# ACB-R1_0-43-CH09.net
KiCad netlist of a schematic drawn in EAGLE
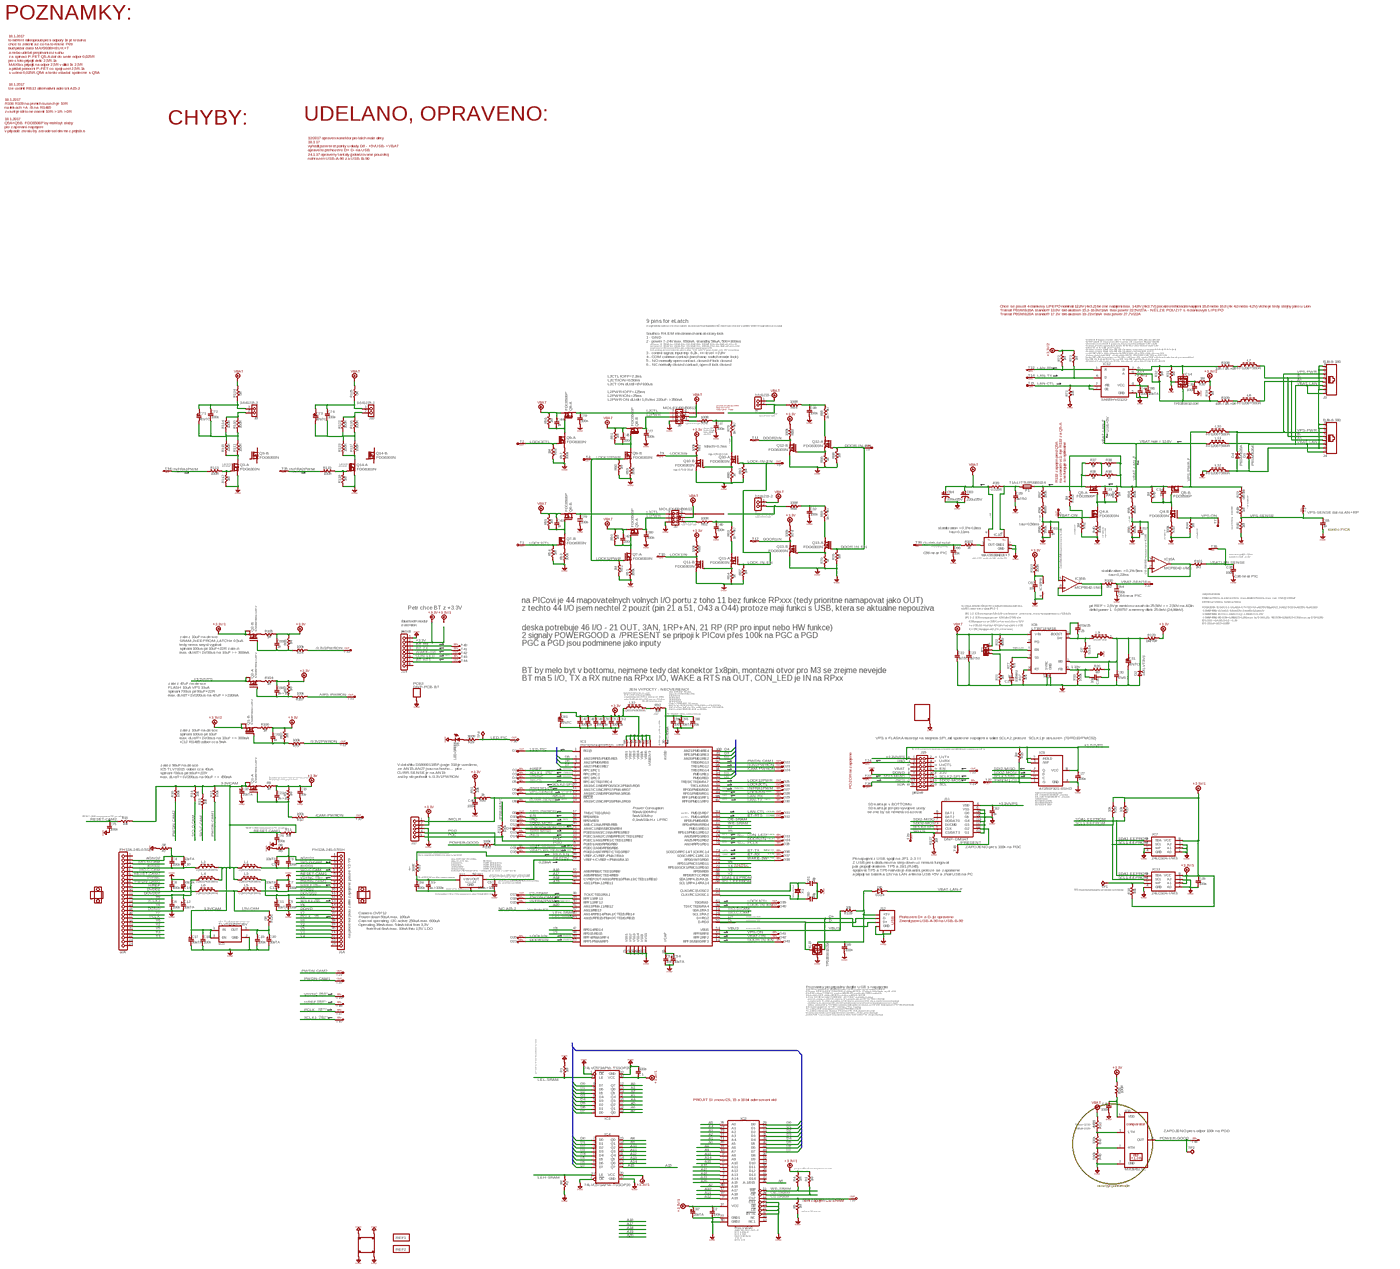
[diagram p0: schematic, sheet 1, overview]
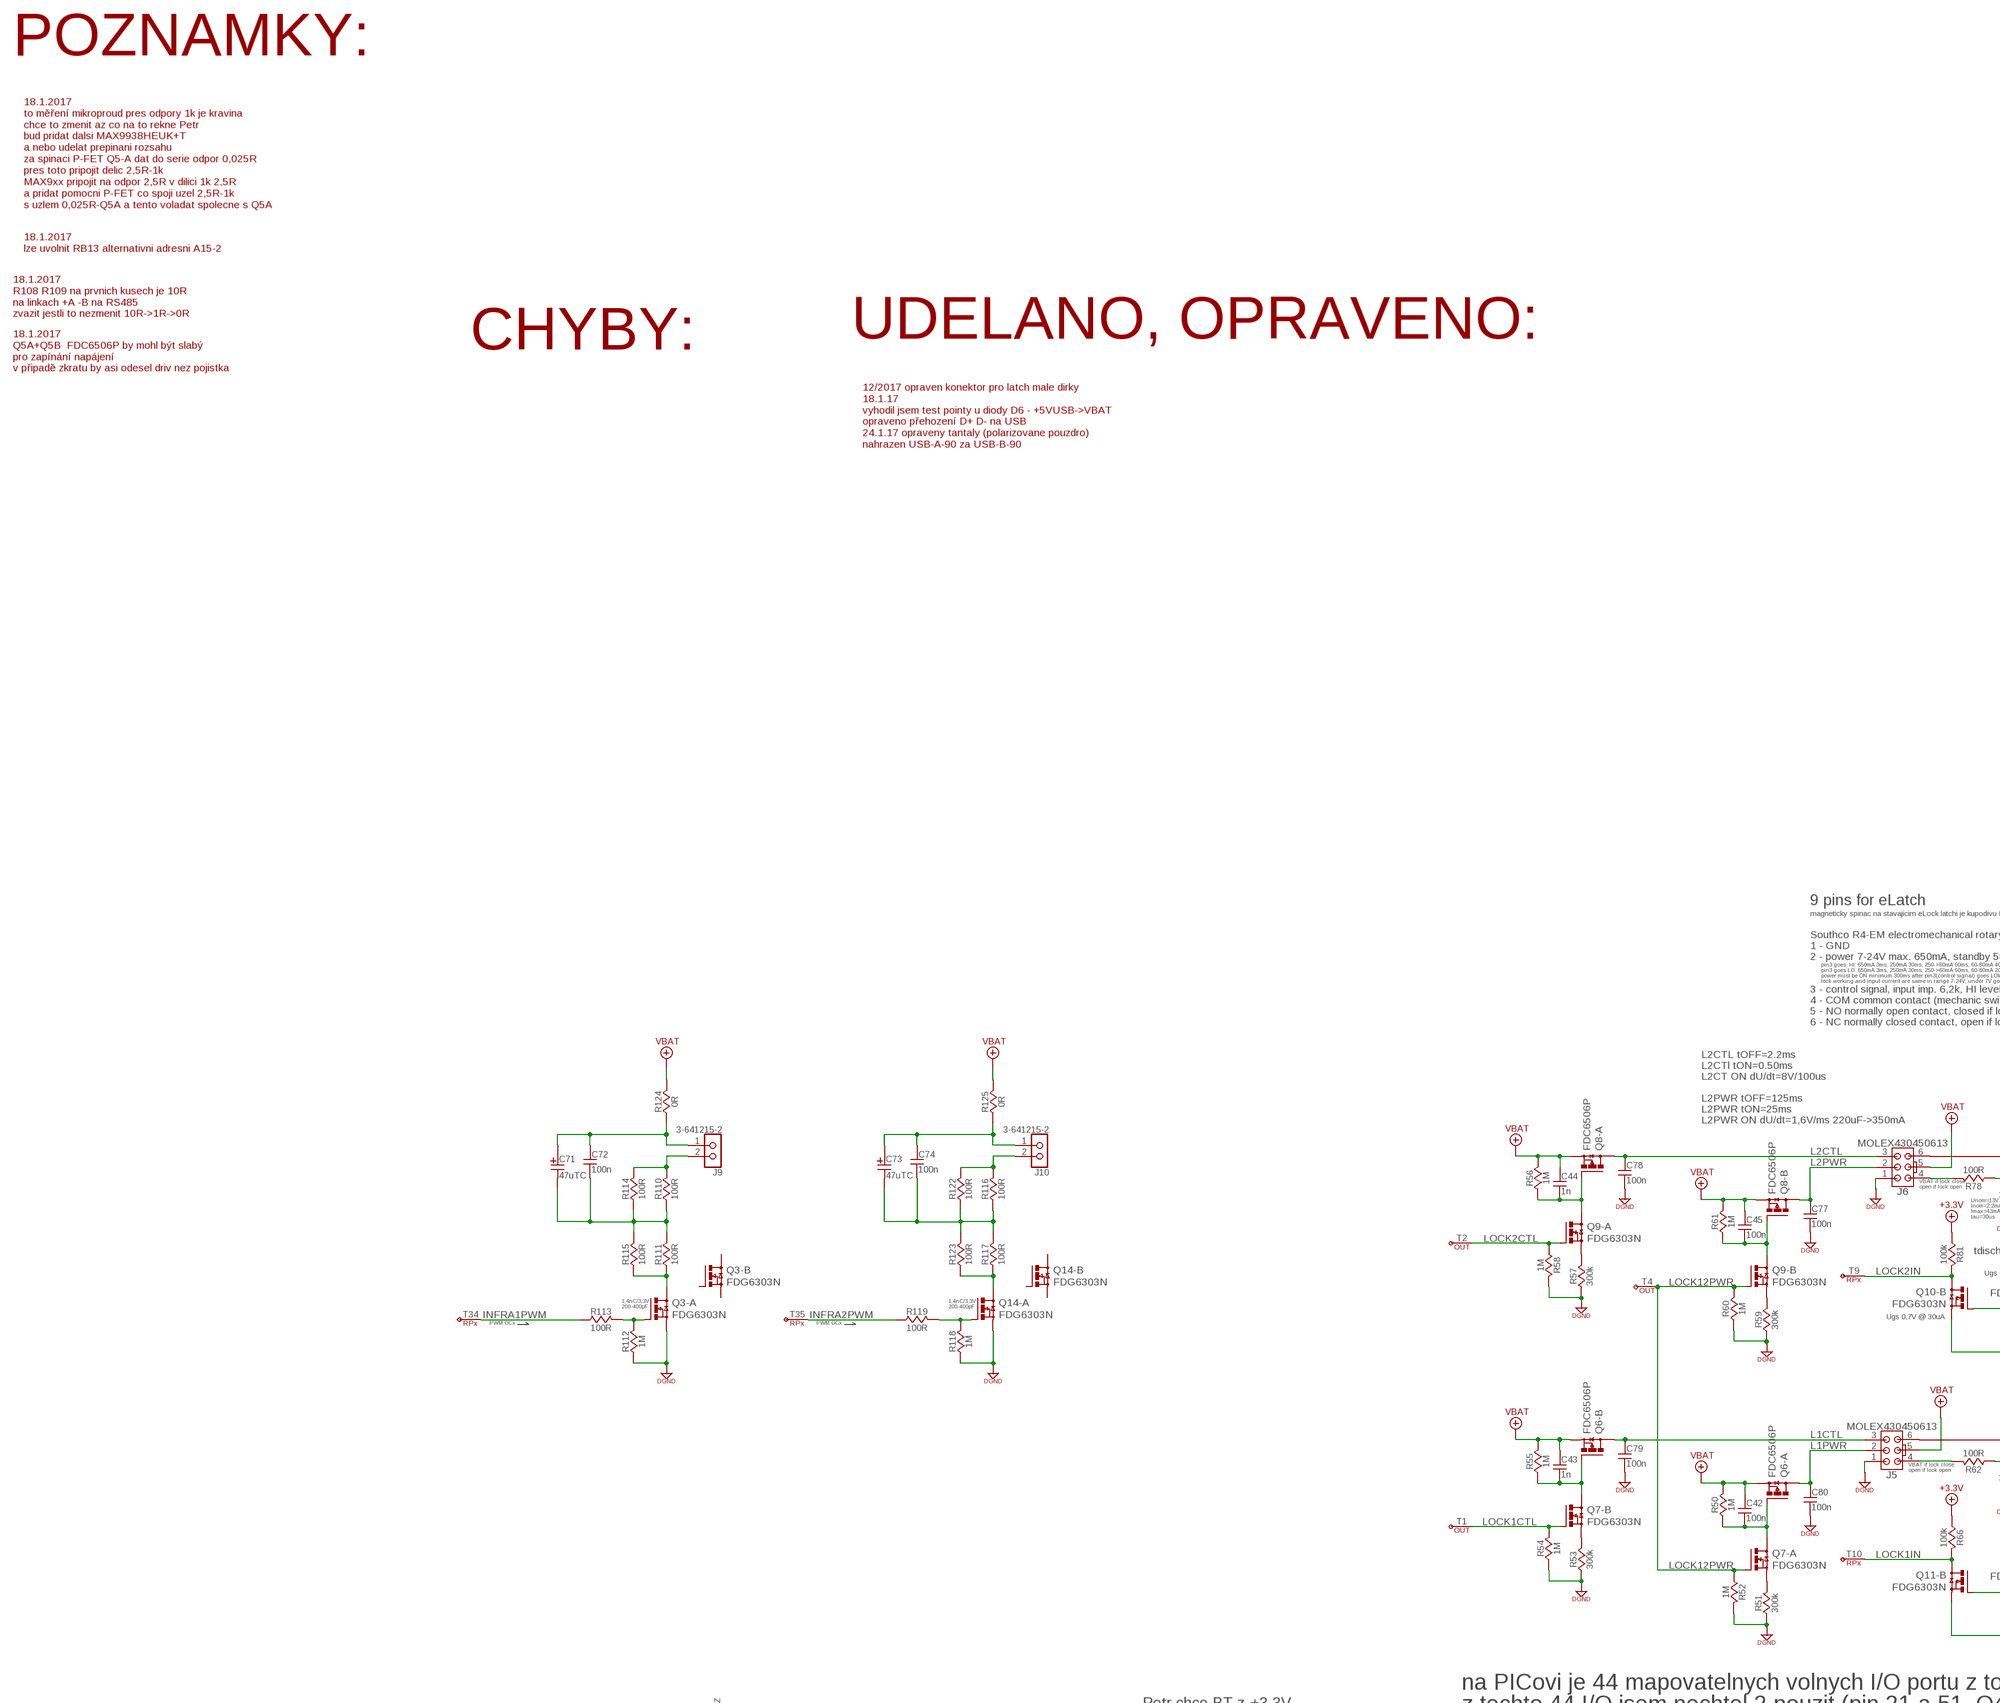
[diagram p1: schematic, sheet 1, part 1 of 4]
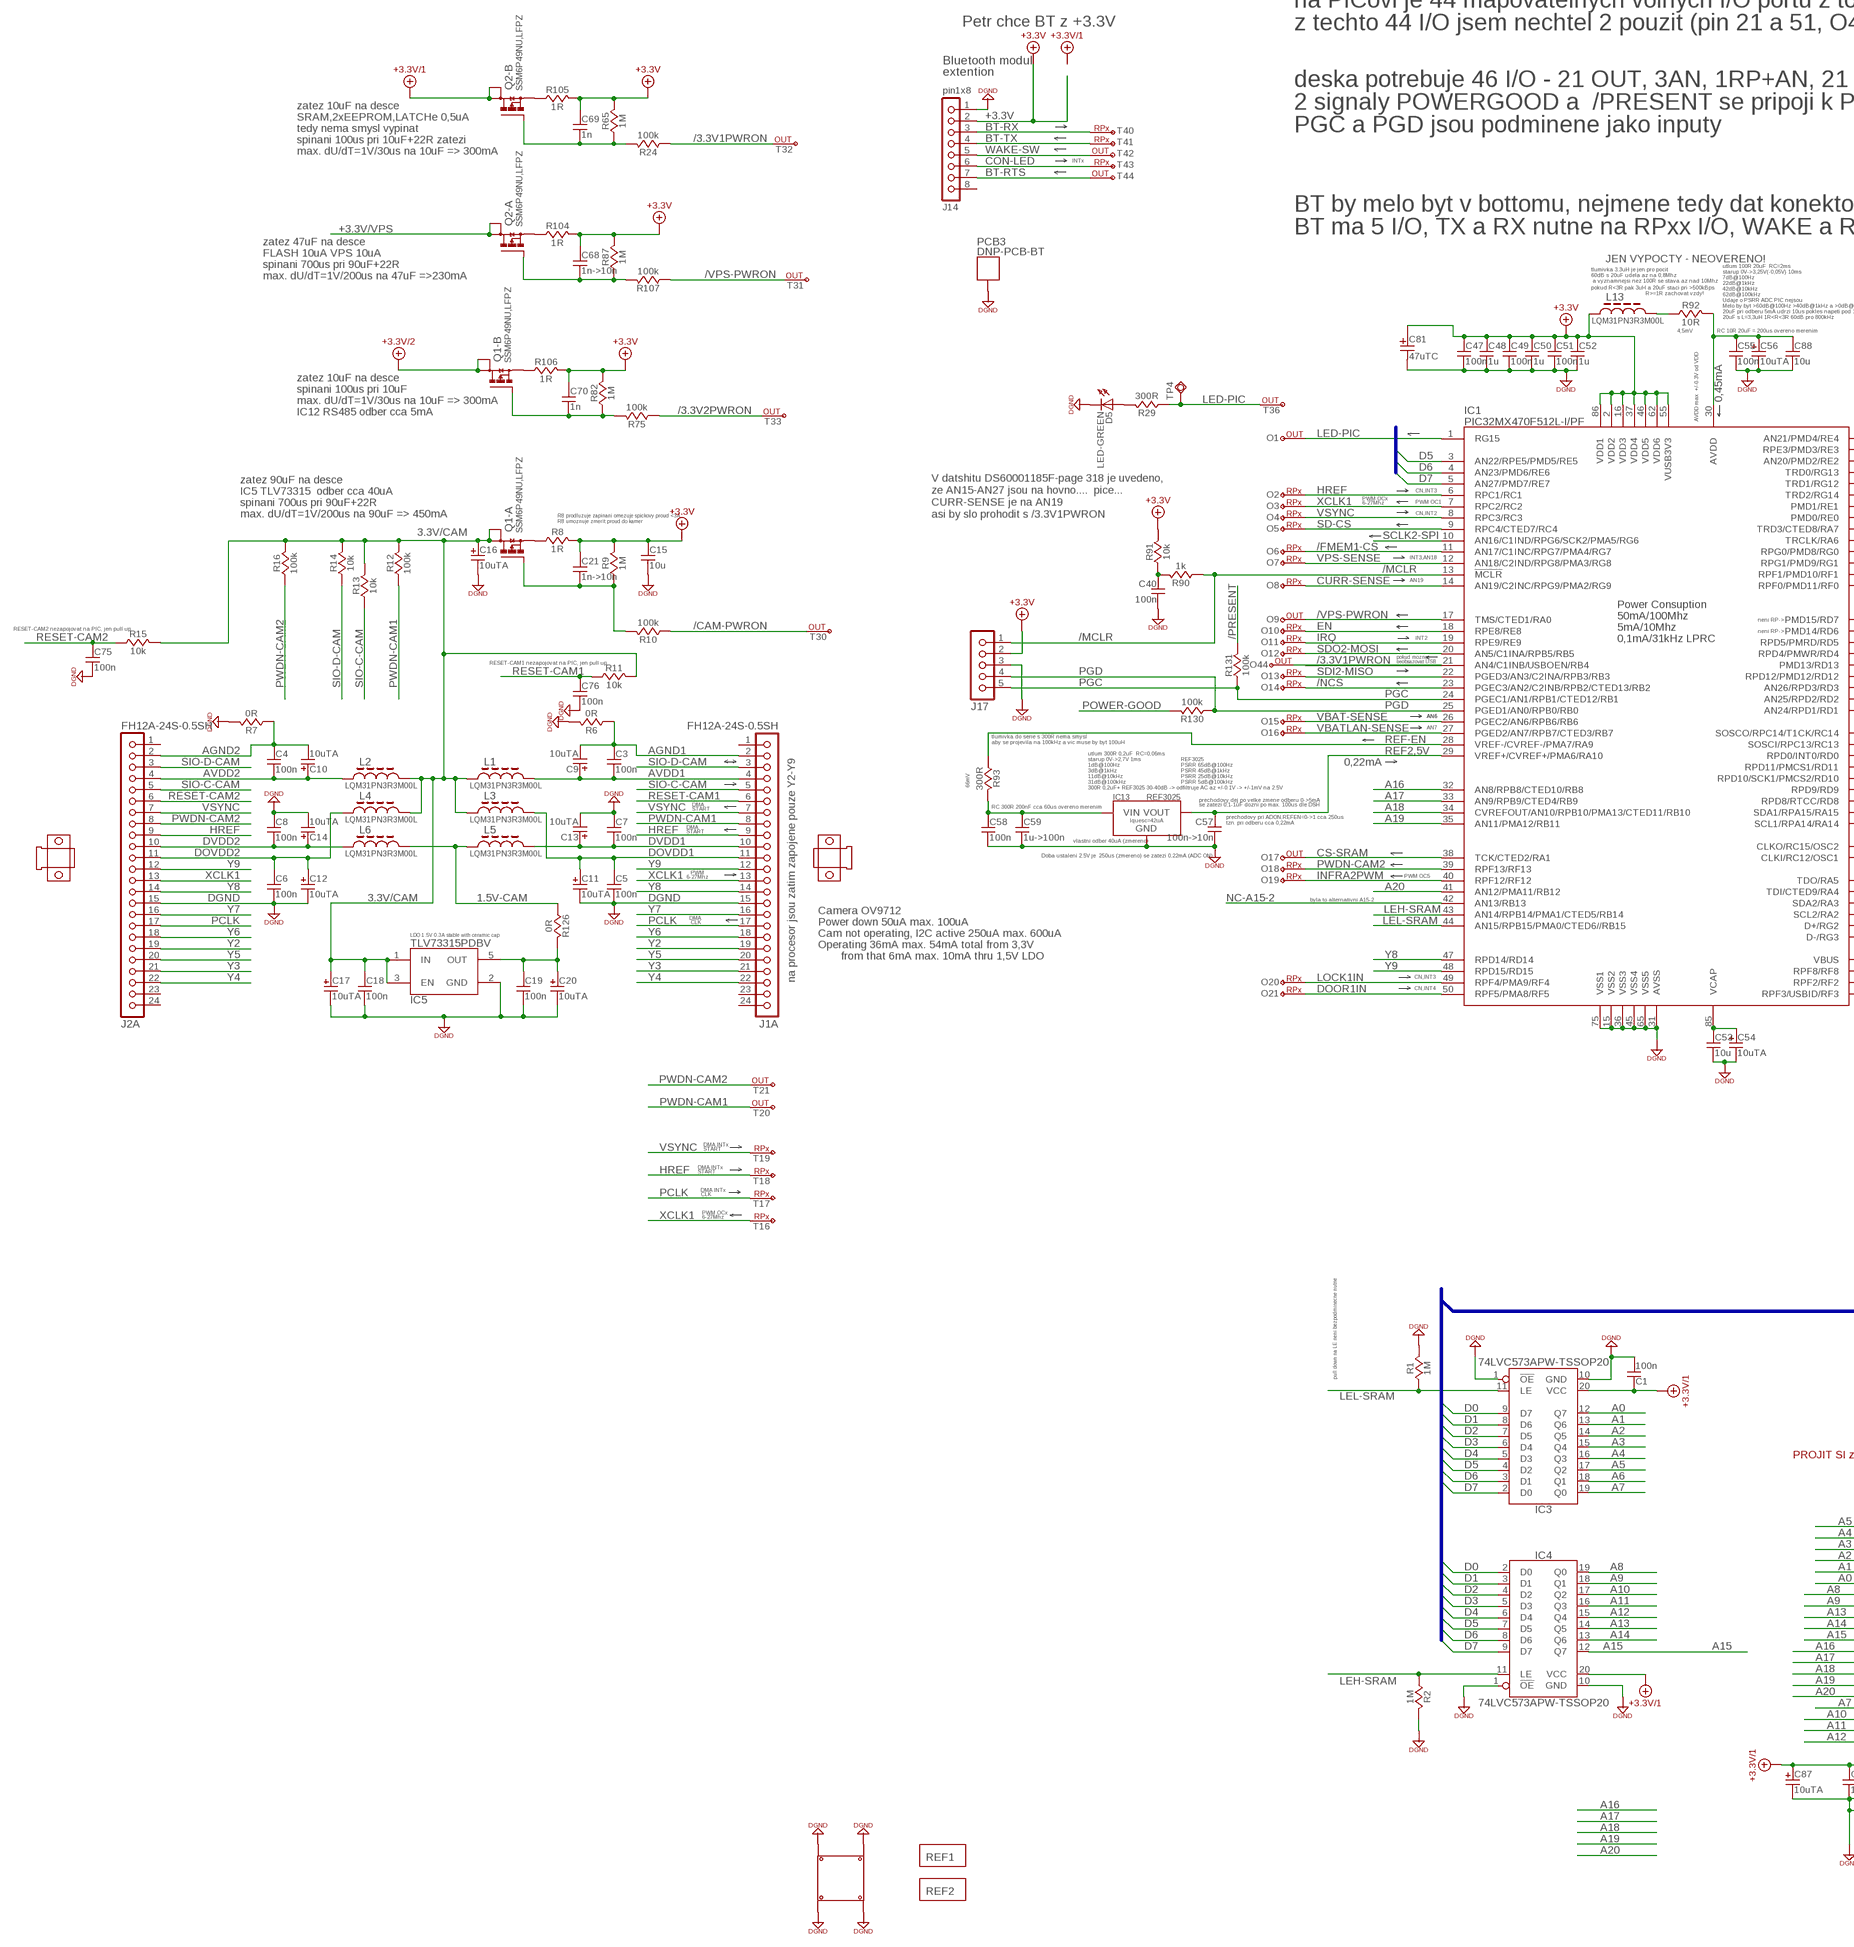
[diagram p2: schematic, sheet 1, part 2 of 4]
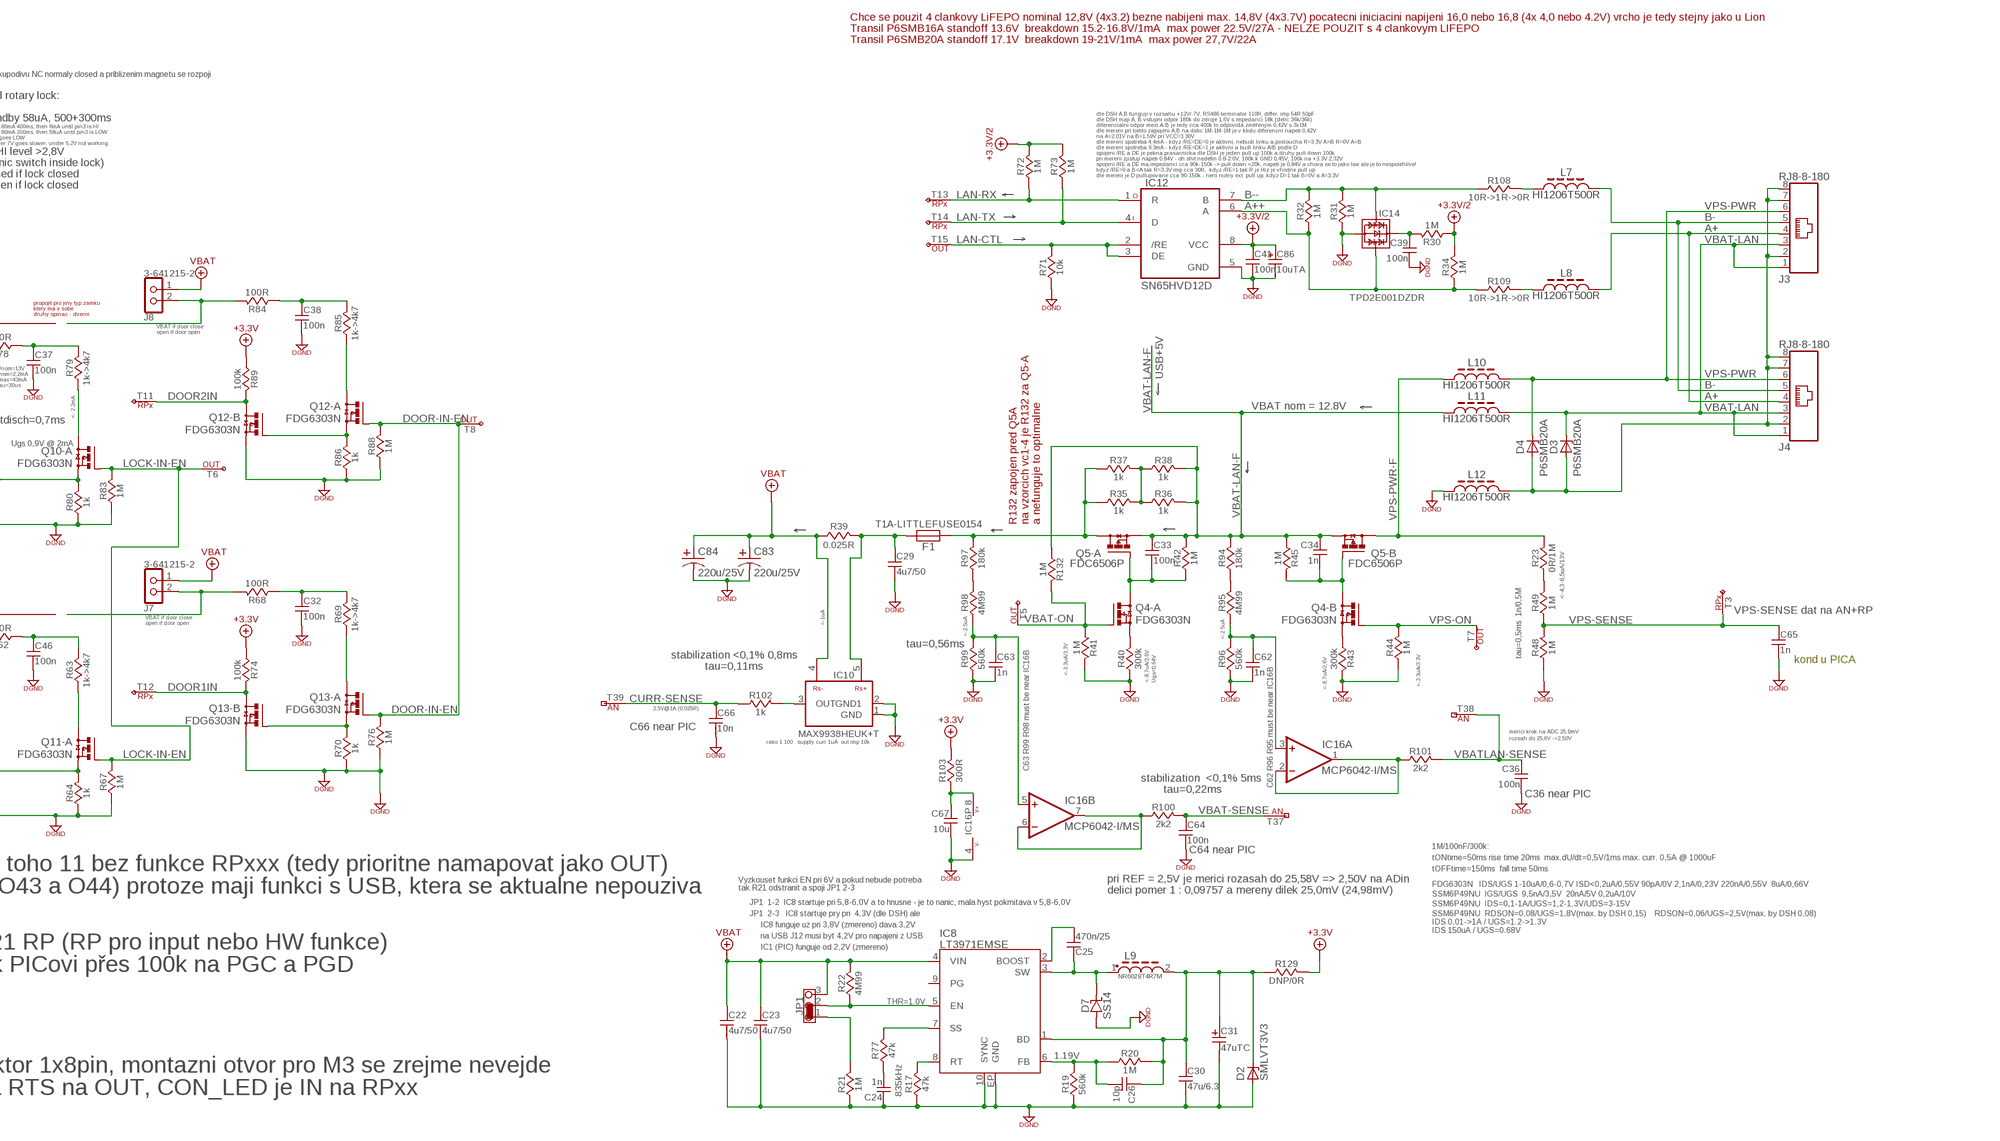
[diagram p3: schematic, sheet 1, part 3 of 4]
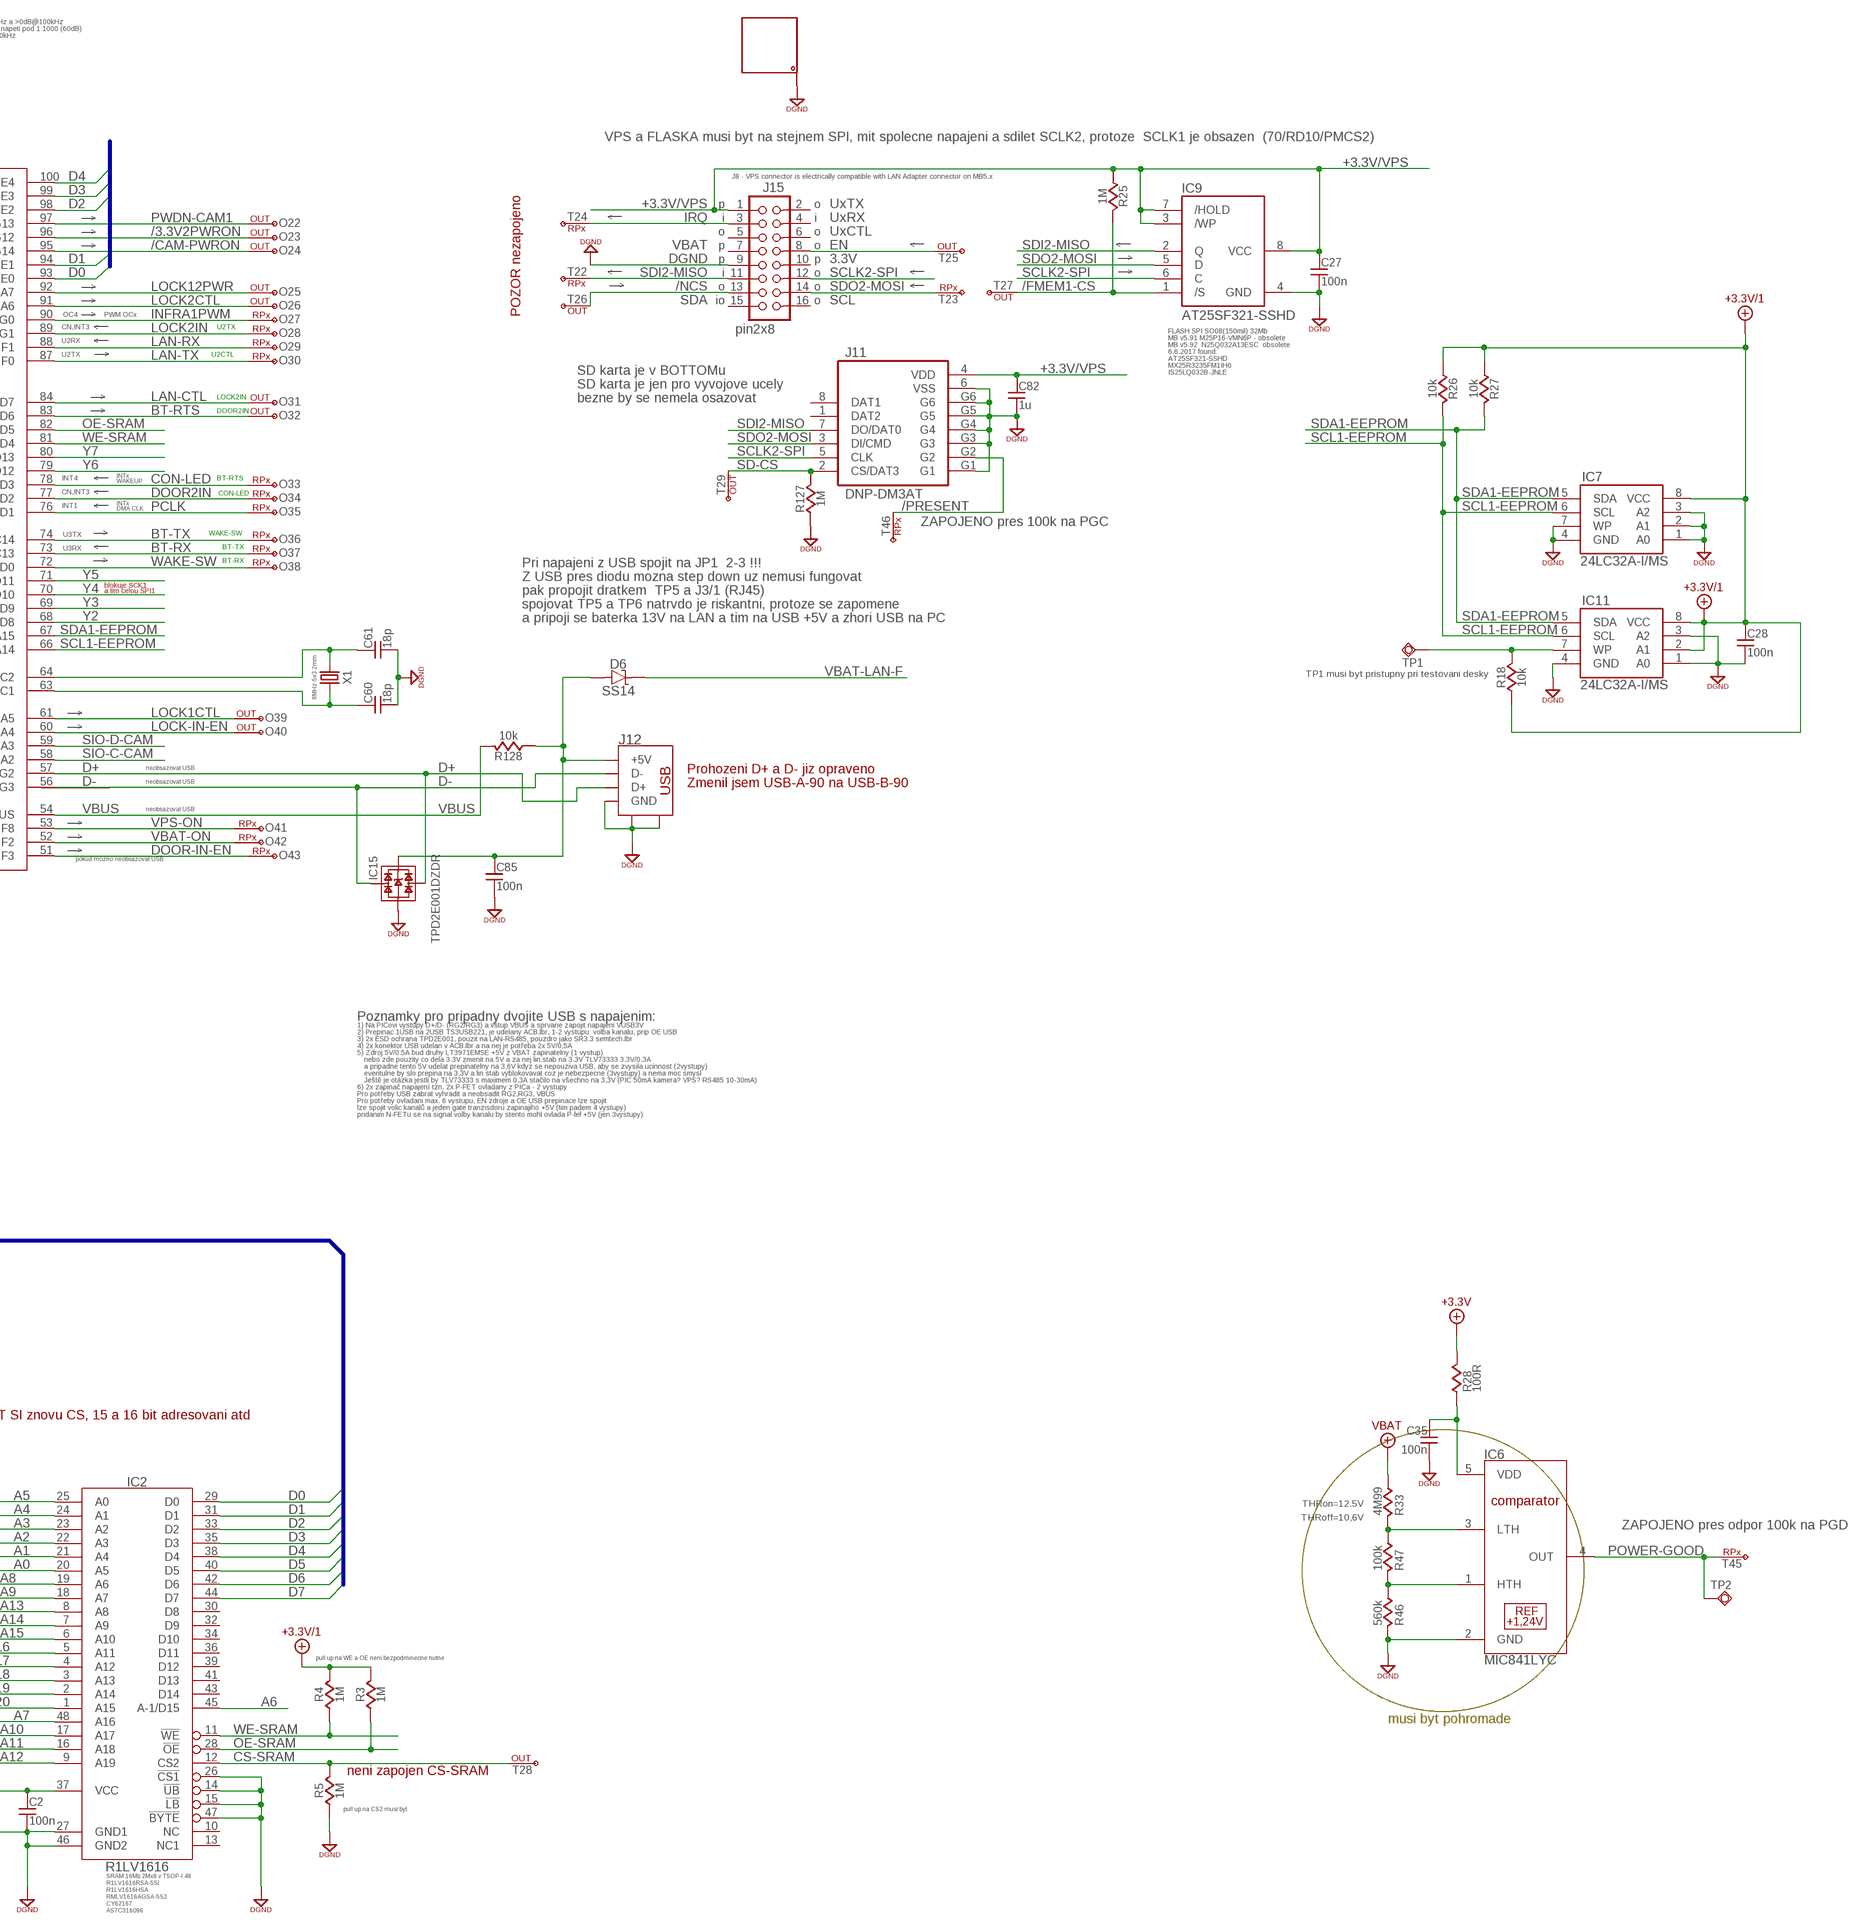
[diagram p4: schematic, sheet 1, part 4 of 4]

(export (version "E")
  (design (tool "Eeschema 10.0.6"))
  (components
    (comp (ref "C1")
      (value "100n")
      (footprint "eagle-import:0603")
      (libsource (lib "eagle-import") (part "C-0603"))
    )
    (comp (ref "C2")
      (value "100n")
      (footprint "eagle-import:0603")
      (libsource (lib "eagle-import") (part "C-0603"))
    )
    (comp (ref "C3")
      (value "100n")
      (footprint "eagle-import:0603")
      (libsource (lib "eagle-import") (part "C-0603"))
    )
    (comp (ref "C4")
      (value "100n")
      (footprint "eagle-import:0603")
      (libsource (lib "eagle-import") (part "C-0603"))
    )
    (comp (ref "C5")
      (value "100n")
      (footprint "eagle-import:0603")
      (libsource (lib "eagle-import") (part "C-0603"))
    )
    (comp (ref "C6")
      (value "100n")
      (footprint "eagle-import:0603")
      (libsource (lib "eagle-import") (part "C-0603"))
    )
    (comp (ref "C7")
      (value "100n")
      (footprint "eagle-import:0603")
      (libsource (lib "eagle-import") (part "C-0603"))
    )
    (comp (ref "C8")
      (value "100n")
      (footprint "eagle-import:0603")
      (libsource (lib "eagle-import") (part "C-0603"))
    )
    (comp (ref "C9")
      (value "10uTA")
      (footprint "eagle-import:1206-POL-C")
      (libsource (lib "eagle-import") (part "CT-1206"))
    )
    (comp (ref "C10")
      (value "10uTA")
      (footprint "eagle-import:1206-POL-C")
      (libsource (lib "eagle-import") (part "CT-1206"))
    )
    (comp (ref "C11")
      (value "10uTA")
      (footprint "eagle-import:1206-POL-C")
      (libsource (lib "eagle-import") (part "CT-1206"))
    )
    (comp (ref "C12")
      (value "10uTA")
      (footprint "eagle-import:1206-POL-C")
      (libsource (lib "eagle-import") (part "CT-1206"))
    )
    (comp (ref "C13")
      (value "10uTA")
      (footprint "eagle-import:1206-POL-C")
      (libsource (lib "eagle-import") (part "CT-1206"))
    )
    (comp (ref "C14")
      (value "10uTA")
      (footprint "eagle-import:1206-POL-C")
      (libsource (lib "eagle-import") (part "CT-1206"))
    )
    (comp (ref "C15")
      (value "10u")
      (footprint "eagle-import:0603")
      (libsource (lib "eagle-import") (part "C-0603"))
    )
    (comp (ref "C16")
      (value "10uTA")
      (footprint "eagle-import:1206-POL-C")
      (libsource (lib "eagle-import") (part "CT-1206"))
    )
    (comp (ref "C17")
      (value "10uTA")
      (footprint "eagle-import:1206-POL-C")
      (libsource (lib "eagle-import") (part "CT-1206"))
    )
    (comp (ref "C18")
      (value "100n")
      (footprint "eagle-import:0603")
      (libsource (lib "eagle-import") (part "C-0603"))
    )
    (comp (ref "C19")
      (value "100n")
      (footprint "eagle-import:0603")
      (libsource (lib "eagle-import") (part "C-0603"))
    )
    (comp (ref "C20")
      (value "10uTA")
      (footprint "eagle-import:1206-POL-C")
      (libsource (lib "eagle-import") (part "CT-1206"))
    )
    (comp (ref "C21")
      (value "1n->10n")
      (footprint "eagle-import:0603")
      (libsource (lib "eagle-import") (part "C-0603"))
    )
    (comp (ref "C22")
      (value "4u7/50")
      (footprint "eagle-import:1206")
      (libsource (lib "eagle-import") (part "C-1206"))
    )
    (comp (ref "C23")
      (value "4u7/50")
      (footprint "eagle-import:1206")
      (libsource (lib "eagle-import") (part "C-1206"))
    )
    (comp (ref "C24")
      (value "1n")
      (footprint "eagle-import:0603")
      (libsource (lib "eagle-import") (part "C-0603"))
    )
    (comp (ref "C25")
      (value "470n/25")
      (footprint "eagle-import:0603")
      (libsource (lib "eagle-import") (part "C-0603"))
    )
    (comp (ref "C26")
      (value "10p")
      (footprint "eagle-import:0603")
      (libsource (lib "eagle-import") (part "C-0603"))
    )
    (comp (ref "C27")
      (value "100n")
      (footprint "eagle-import:0603")
      (libsource (lib "eagle-import") (part "C-0603"))
    )
    (comp (ref "C28")
      (value "100n")
      (footprint "eagle-import:0603")
      (libsource (lib "eagle-import") (part "C-0603"))
    )
    (comp (ref "C29")
      (value "4u7/50")
      (footprint "eagle-import:1206")
      (libsource (lib "eagle-import") (part "C-1206"))
    )
    (comp (ref "C30")
      (value "47u/6.3")
      (footprint "eagle-import:1206")
      (libsource (lib "eagle-import") (part "C-1206"))
    )
    (comp (ref "C31")
      (value "47uTC")
      (footprint "eagle-import:CT-C")
      (libsource (lib "eagle-import") (part "CT-C"))
    )
    (comp (ref "C32")
      (value "100n")
      (footprint "eagle-import:0603")
      (libsource (lib "eagle-import") (part "C-0603"))
    )
    (comp (ref "C33")
      (value "100n")
      (footprint "eagle-import:0603")
      (libsource (lib "eagle-import") (part "C-0603"))
    )
    (comp (ref "C34")
      (value "1n")
      (footprint "eagle-import:0603")
      (libsource (lib "eagle-import") (part "C-0603"))
    )
    (comp (ref "C35")
      (value "100n")
      (footprint "eagle-import:0603")
      (libsource (lib "eagle-import") (part "C-0603"))
    )
    (comp (ref "C36")
      (value "100n")
      (footprint "eagle-import:0603")
      (libsource (lib "eagle-import") (part "C-0603"))
    )
    (comp (ref "C37")
      (value "100n")
      (footprint "eagle-import:0603")
      (libsource (lib "eagle-import") (part "C-0603"))
    )
    (comp (ref "C38")
      (value "100n")
      (footprint "eagle-import:0603")
      (libsource (lib "eagle-import") (part "C-0603"))
    )
    (comp (ref "C39")
      (value "100n")
      (footprint "eagle-import:0603")
      (libsource (lib "eagle-import") (part "C-0603"))
    )
    (comp (ref "C40")
      (value "100n")
      (footprint "eagle-import:0603")
      (libsource (lib "eagle-import") (part "C-0603"))
    )
    (comp (ref "C41")
      (value "100n")
      (footprint "eagle-import:0603")
      (libsource (lib "eagle-import") (part "C-0603"))
    )
    (comp (ref "C42")
      (value "100n")
      (footprint "eagle-import:0603")
      (libsource (lib "eagle-import") (part "C-0603"))
    )
    (comp (ref "C43")
      (value "1n")
      (footprint "eagle-import:0603")
      (libsource (lib "eagle-import") (part "C-0603"))
    )
    (comp (ref "C44")
      (value "1n")
      (footprint "eagle-import:0603")
      (libsource (lib "eagle-import") (part "C-0603"))
    )
    (comp (ref "C45")
      (value "100n")
      (footprint "eagle-import:0603")
      (libsource (lib "eagle-import") (part "C-0603"))
    )
    (comp (ref "C46")
      (value "100n")
      (footprint "eagle-import:0603")
      (libsource (lib "eagle-import") (part "C-0603"))
    )
    (comp (ref "C47")
      (value "100n")
      (footprint "eagle-import:0603")
      (libsource (lib "eagle-import") (part "C-0603"))
    )
    (comp (ref "C48")
      (value "1u")
      (footprint "eagle-import:0603")
      (libsource (lib "eagle-import") (part "C-0603"))
    )
    (comp (ref "C49")
      (value "100n")
      (footprint "eagle-import:0603")
      (libsource (lib "eagle-import") (part "C-0603"))
    )
    (comp (ref "C50")
      (value "1u")
      (footprint "eagle-import:0603")
      (libsource (lib "eagle-import") (part "C-0603"))
    )
    (comp (ref "C51")
      (value "100n")
      (footprint "eagle-import:0603")
      (libsource (lib "eagle-import") (part "C-0603"))
    )
    (comp (ref "C52")
      (value "1u")
      (footprint "eagle-import:0603")
      (libsource (lib "eagle-import") (part "C-0603"))
    )
    (comp (ref "C53")
      (value "10u")
      (footprint "eagle-import:0603")
      (libsource (lib "eagle-import") (part "C-0603"))
    )
    (comp (ref "C54")
      (value "10uTA")
      (footprint "eagle-import:1206-POL-C")
      (libsource (lib "eagle-import") (part "CT-1206"))
    )
    (comp (ref "C55")
      (value "100n")
      (footprint "eagle-import:0603")
      (libsource (lib "eagle-import") (part "C-0603"))
    )
    (comp (ref "C56")
      (value "10uTA")
      (footprint "eagle-import:1206-POL-C")
      (libsource (lib "eagle-import") (part "CT-1206"))
    )
    (comp (ref "C57")
      (value "100n->10n")
      (footprint "eagle-import:0603")
      (libsource (lib "eagle-import") (part "C-0603"))
    )
    (comp (ref "C58")
      (value "100n")
      (footprint "eagle-import:0603")
      (libsource (lib "eagle-import") (part "C-0603"))
    )
    (comp (ref "C59")
      (value "1u->100n")
      (footprint "eagle-import:0603")
      (libsource (lib "eagle-import") (part "C-0603"))
    )
    (comp (ref "C60")
      (value "18p")
      (footprint "eagle-import:0603")
      (libsource (lib "eagle-import") (part "C-0603"))
    )
    (comp (ref "C61")
      (value "18p")
      (footprint "eagle-import:0603")
      (libsource (lib "eagle-import") (part "C-0603"))
    )
    (comp (ref "C62")
      (value "1n")
      (footprint "eagle-import:0603")
      (libsource (lib "eagle-import") (part "C-0603"))
    )
    (comp (ref "C63")
      (value "1n")
      (footprint "eagle-import:0603")
      (libsource (lib "eagle-import") (part "C-0603"))
    )
    (comp (ref "C64")
      (value "100n")
      (footprint "eagle-import:0603")
      (libsource (lib "eagle-import") (part "C-0603"))
    )
    (comp (ref "C65")
      (value "1n")
      (footprint "eagle-import:0603")
      (libsource (lib "eagle-import") (part "C-0603"))
    )
    (comp (ref "C66")
      (value "10n")
      (footprint "eagle-import:0603")
      (libsource (lib "eagle-import") (part "C-0603"))
    )
    (comp (ref "C67")
      (value "10u")
      (footprint "eagle-import:0603")
      (libsource (lib "eagle-import") (part "C-0603"))
    )
    (comp (ref "C68")
      (value "1n->10n")
      (footprint "eagle-import:0603")
      (libsource (lib "eagle-import") (part "C-0603"))
    )
    (comp (ref "C69")
      (value "1n")
      (footprint "eagle-import:0603")
      (libsource (lib "eagle-import") (part "C-0603"))
    )
    (comp (ref "C70")
      (value "1n")
      (footprint "eagle-import:0603")
      (libsource (lib "eagle-import") (part "C-0603"))
    )
    (comp (ref "C71")
      (value "47uTC")
      (footprint "eagle-import:CT-C")
      (libsource (lib "eagle-import") (part "CT-C"))
    )
    (comp (ref "C72")
      (value "100n")
      (footprint "eagle-import:0603")
      (libsource (lib "eagle-import") (part "C-0603"))
    )
    (comp (ref "C73")
      (value "47uTC")
      (footprint "eagle-import:CT-C")
      (libsource (lib "eagle-import") (part "CT-C"))
    )
    (comp (ref "C74")
      (value "100n")
      (footprint "eagle-import:0603")
      (libsource (lib "eagle-import") (part "C-0603"))
    )
    (comp (ref "C75")
      (value "100n")
      (footprint "eagle-import:0603")
      (libsource (lib "eagle-import") (part "C-0603"))
    )
    (comp (ref "C76")
      (value "100n")
      (footprint "eagle-import:0603")
      (libsource (lib "eagle-import") (part "C-0603"))
    )
    (comp (ref "C77")
      (value "100n")
      (footprint "eagle-import:0603")
      (libsource (lib "eagle-import") (part "C-0603"))
    )
    (comp (ref "C78")
      (value "100n")
      (footprint "eagle-import:0603")
      (libsource (lib "eagle-import") (part "C-0603"))
    )
    (comp (ref "C79")
      (value "100n")
      (footprint "eagle-import:0603")
      (libsource (lib "eagle-import") (part "C-0603"))
    )
    (comp (ref "C80")
      (value "100n")
      (footprint "eagle-import:0603")
      (libsource (lib "eagle-import") (part "C-0603"))
    )
    (comp (ref "C81")
      (value "47uTC")
      (footprint "eagle-import:CT-C")
      (libsource (lib "eagle-import") (part "CT-C"))
    )
    (comp (ref "C82")
      (value "1u")
      (footprint "eagle-import:0603")
      (libsource (lib "eagle-import") (part "C-0603"))
    )
    (comp (ref "C83")
      (value "220u/25V")
      (footprint "eagle-import:CAP_8MM_DIA_SMT")
      (libsource (lib "eagle-import") (part "CAP-ELEC-SMD-8MM"))
    )
    (comp (ref "C84")
      (value "220u/25V")
      (footprint "eagle-import:CAP_8MM_DIA_SMT")
      (libsource (lib "eagle-import") (part "CAP-ELEC-SMD-8MM"))
    )
    (comp (ref "C85")
      (value "100n")
      (footprint "eagle-import:0603")
      (libsource (lib "eagle-import") (part "C-0603"))
    )
    (comp (ref "C86")
      (value "10uTA")
      (footprint "eagle-import:1206-POL-C")
      (libsource (lib "eagle-import") (part "CT-1206"))
    )
    (comp (ref "C87")
      (value "10uTA")
      (footprint "eagle-import:1206-POL-C")
      (libsource (lib "eagle-import") (part "CT-1206"))
    )
    (comp (ref "C88")
      (value "10u")
      (footprint "eagle-import:0603")
      (libsource (lib "eagle-import") (part "C-0603"))
    )
    (comp (ref "D2")
      (value "SMLVT3V3")
      (footprint "eagle-import:SMA")
      (libsource (lib "eagle-import") (part "SMLVT3V3"))
    )
    (comp (ref "D3")
      (value "P6SMB20A")
      (footprint "eagle-import:SMB")
      (libsource (lib "eagle-import") (part "P6SMB"))
    )
    (comp (ref "D4")
      (value "P6SMB20A")
      (footprint "eagle-import:SMB")
      (libsource (lib "eagle-import") (part "P6SMB"))
    )
    (comp (ref "D5")
      (value "LED-GREEN")
      (footprint "eagle-import:0805-POL-D")
      (libsource (lib "eagle-import") (part "LED-0805"))
    )
    (comp (ref "D6")
      (value "SS14")
      (footprint "eagle-import:SMA")
      (libsource (lib "eagle-import") (part "DS-SMA"))
    )
    (comp (ref "D7")
      (value "SS14")
      (footprint "eagle-import:SMA")
      (libsource (lib "eagle-import") (part "DS-SMA"))
    )
    (comp (ref "F1")
      (value "T1A-LITTLEFUSE0154")
      (footprint "eagle-import:LITTLEFUSE0154")
      (libsource (lib "eagle-import") (part "POJISTKA-LITTLEFUSE0154"))
    )
    (comp (ref "H1")
      (value "CAM-HOLDER")
      (footprint "eagle-import:CAM-HOLDER")
      (libsource (lib "eagle-import") (part "CAM-HOLDER"))
    )
    (comp (ref "H2")
      (value "CAM-HOLDER")
      (footprint "eagle-import:CAM-HOLDER")
      (libsource (lib "eagle-import") (part "CAM-HOLDER"))
    )
    (comp (ref "IC1")
      (value "PIC32MX470F512L-I/PF")
      (footprint "eagle-import:TQFP100_14X14_0,5MM")
      (libsource (lib "eagle-import") (part "PIC32MX470F512L-I/PF"))
    )
    (comp (ref "IC2")
      (value "R1LV1616")
      (footprint "eagle-import:48-TSOP-I")
      (libsource (lib "eagle-import") (part "R1LV1616HSA"))
    )
    (comp (ref "IC3")
      (value "74LVC573APW-TSSOP20")
      (footprint "eagle-import:TSSOP20")
      (libsource (lib "eagle-import") (part "74LVC573APW-TSSOP20"))
    )
    (comp (ref "IC4")
      (value "74LVC573APW-TSSOP20")
      (footprint "eagle-import:TSSOP20")
      (libsource (lib "eagle-import") (part "74LVC573APW-TSSOP20"))
    )
    (comp (ref "IC5")
      (value "TLV73315PDBV")
      (footprint "eagle-import:SOT23-5")
      (libsource (lib "eagle-import") (part "TLV73315PDBV"))
    )
    (comp (ref "IC6")
      (value "MIC841LYC")
      (footprint "eagle-import:SC-70-5")
      (libsource (lib "eagle-import") (part "MIC841LYC"))
    )
    (comp (ref "IC7")
      (value "24LC32A-I/MS")
      (footprint "eagle-import:MSOP-08")
      (libsource (lib "eagle-import") (part "24-I/MS"))
    )
    (comp (ref "IC8")
      (value "LT3971EMSE")
      (footprint "eagle-import:MSOP10EXP")
      (libsource (lib "eagle-import") (part "LT3971EMSE"))
    )
    (comp (ref "IC9")
      (value "AT25SF321-SSHD")
      (footprint "eagle-import:SO-08")
      (libsource (lib "eagle-import") (part "M25P16-VMN6P"))
    )
    (comp (ref "IC10")
      (value "MAX9938HEUK+T")
      (footprint "eagle-import:SOT23-5")
      (libsource (lib "eagle-import") (part "TSM9938HEUK+T"))
    )
    (comp (ref "IC11")
      (value "24LC32A-I/MS")
      (footprint "eagle-import:MSOP-08")
      (libsource (lib "eagle-import") (part "24-I/MS"))
    )
    (comp (ref "IC12")
      (value "SN65HVD12D")
      (footprint "eagle-import:SO08")
      (libsource (lib "eagle-import") (part "SN65HVD3082ED"))
    )
    (comp (ref "IC13")
      (value "REF3025")
      (footprint "eagle-import:SOT23")
      (libsource (lib "eagle-import") (part "REF3025"))
    )
    (comp (ref "IC14")
      (value "TPD2E001DZDR")
      (footprint "eagle-import:SOT-143")
      (libsource (lib "eagle-import") (part "SR05.TCT"))
    )
    (comp (ref "IC15")
      (value "TPD2E001DZDR")
      (footprint "eagle-import:SOT-143")
      (libsource (lib "eagle-import") (part "SR05.TCT"))
    )
    (comp (ref "IC16")
      (value "MCP6042-I/MS")
      (footprint "eagle-import:MSOP-08")
      (libsource (lib "eagle-import") (part "MCP6042-I/MS"))
    )
    (comp (ref "J1")
      (value "FH12A-24S-0.5SH")
      (footprint "eagle-import:FH12A-24S-05SH")
      (libsource (lib "eagle-import") (part "FH12A-24S-0.5SH"))
    )
    (comp (ref "J2")
      (value "FH12A-24S-0.5SH")
      (footprint "eagle-import:FH12A-24S-05SH")
      (libsource (lib "eagle-import") (part "FH12A-24S-0.5SH"))
    )
    (comp (ref "J3")
      (value "RJ8-8-180")
      (footprint "eagle-import:RJ8-8-180")
      (libsource (lib "eagle-import") (part "RJ8-8-180"))
    )
    (comp (ref "J4")
      (value "RJ8-8-180")
      (footprint "eagle-import:RJ8-8-180")
      (libsource (lib "eagle-import") (part "RJ8-8-180"))
    )
    (comp (ref "J5")
      (value "MOLEX430450613")
      (footprint "eagle-import:MOLEX430450613")
      (libsource (lib "eagle-import") (part "MOLEX430450613"))
    )
    (comp (ref "J6")
      (value "MOLEX430450613")
      (footprint "eagle-import:MOLEX430450613")
      (libsource (lib "eagle-import") (part "MOLEX430450613"))
    )
    (comp (ref "J7")
      (value "3-641215-2")
      (footprint "eagle-import:3-641215-2")
      (libsource (lib "eagle-import") (part "3-641215-2"))
    )
    (comp (ref "J8")
      (value "3-641215-2")
      (footprint "eagle-import:3-641215-2")
      (libsource (lib "eagle-import") (part "3-641215-2"))
    )
    (comp (ref "J9")
      (value "3-641215-2")
      (footprint "eagle-import:3-641215-2")
      (libsource (lib "eagle-import") (part "3-641215-2"))
    )
    (comp (ref "J10")
      (value "3-641215-2")
      (footprint "eagle-import:3-641215-2")
      (libsource (lib "eagle-import") (part "3-641215-2"))
    )
    (comp (ref "J11")
      (value "DNP-DM3AT")
      (footprint "eagle-import:DM3AT")
      (libsource (lib "eagle-import") (part "DM3AT"))
    )
    (comp (ref "J12")
      (value "USB_A_180")
      (footprint "eagle-import:USB_B_180")
      (libsource (lib "eagle-import") (part "USB_B_180"))
    )
    (comp (ref "J14")
      (value "pin1x8")
      (footprint "eagle-import:MA08-1-MALE")
      (libsource (lib "eagle-import") (part "MA08-1-M"))
    )
    (comp (ref "J15")
      (value "pin2x8")
      (footprint "eagle-import:MA08-2")
      (libsource (lib "eagle-import") (part "MA08-2"))
    )
    (comp (ref "J17")
      (value "DNP-open-hole")
      (footprint "eagle-import:MA05-1")
      (libsource (lib "eagle-import") (part "MA05-1"))
    )
    (comp (ref "JP1")
      (value "JP3CLOSE12")
      (footprint "eagle-import:JP3CLOSE12")
      (libsource (lib "eagle-import") (part "JP3CLOSE12"))
    )
    (comp (ref "L1")
      (value "LQM31PN3R3M00L")
      (footprint "eagle-import:1206")
      (libsource (lib "eagle-import") (part "L-1206"))
    )
    (comp (ref "L2")
      (value "LQM31PN3R3M00L")
      (footprint "eagle-import:1206")
      (libsource (lib "eagle-import") (part "L-1206"))
    )
    (comp (ref "L3")
      (value "LQM31PN3R3M00L")
      (footprint "eagle-import:1206")
      (libsource (lib "eagle-import") (part "L-1206"))
    )
    (comp (ref "L4")
      (value "LQM31PN3R3M00L")
      (footprint "eagle-import:1206")
      (libsource (lib "eagle-import") (part "L-1206"))
    )
    (comp (ref "L5")
      (value "LQM31PN3R3M00L")
      (footprint "eagle-import:1206")
      (libsource (lib "eagle-import") (part "L-1206"))
    )
    (comp (ref "L6")
      (value "LQM31PN3R3M00L")
      (footprint "eagle-import:1206")
      (libsource (lib "eagle-import") (part "L-1206"))
    )
    (comp (ref "L7")
      (value "HI1206T500R")
      (footprint "eagle-import:1206")
      (libsource (lib "eagle-import") (part "L-1206"))
    )
    (comp (ref "L8")
      (value "HI1206T500R")
      (footprint "eagle-import:1206")
      (libsource (lib "eagle-import") (part "L-1206"))
    )
    (comp (ref "L9")
      (value "NR6028T4R7M")
      (footprint "eagle-import:NR6028")
      (libsource (lib "eagle-import") (part "NR6028"))
    )
    (comp (ref "L10")
      (value "HI1206T500R")
      (footprint "eagle-import:1206")
      (libsource (lib "eagle-import") (part "L-1206"))
    )
    (comp (ref "L11")
      (value "HI1206T500R")
      (footprint "eagle-import:1206")
      (libsource (lib "eagle-import") (part "L-1206"))
    )
    (comp (ref "L12")
      (value "HI1206T500R")
      (footprint "eagle-import:1206")
      (libsource (lib "eagle-import") (part "L-1206"))
    )
    (comp (ref "L13")
      (value "LQM31PN3R3M00L")
      (footprint "eagle-import:1206")
      (libsource (lib "eagle-import") (part "L-1206"))
    )
    (comp (ref "O1")
      (value "PIC-OUT")
      (footprint "eagle-import:TEMP-PAD")
      (libsource (lib "eagle-import") (part "PIC-OUT"))
    )
    (comp (ref "O2")
      (value "PIC-RPX")
      (footprint "eagle-import:TEMP-PAD")
      (libsource (lib "eagle-import") (part "PIC-RPX"))
    )
    (comp (ref "O3")
      (value "PIC-RPX")
      (footprint "eagle-import:TEMP-PAD")
      (libsource (lib "eagle-import") (part "PIC-RPX"))
    )
    (comp (ref "O4")
      (value "PIC-RPX")
      (footprint "eagle-import:TEMP-PAD")
      (libsource (lib "eagle-import") (part "PIC-RPX"))
    )
    (comp (ref "O5")
      (value "PIC-RPX")
      (footprint "eagle-import:TEMP-PAD")
      (libsource (lib "eagle-import") (part "PIC-RPX"))
    )
    (comp (ref "O6")
      (value "PIC-RPX")
      (footprint "eagle-import:TEMP-PAD")
      (libsource (lib "eagle-import") (part "PIC-RPX"))
    )
    (comp (ref "O7")
      (value "PIC-RPX")
      (footprint "eagle-import:TEMP-PAD")
      (libsource (lib "eagle-import") (part "PIC-RPX"))
    )
    (comp (ref "O8")
      (value "PIC-RPX")
      (footprint "eagle-import:TEMP-PAD")
      (libsource (lib "eagle-import") (part "PIC-RPX"))
    )
    (comp (ref "O9")
      (value "PIC-OUT")
      (footprint "eagle-import:TEMP-PAD")
      (libsource (lib "eagle-import") (part "PIC-OUT"))
    )
    (comp (ref "O10")
      (value "PIC-RPX")
      (footprint "eagle-import:TEMP-PAD")
      (libsource (lib "eagle-import") (part "PIC-RPX"))
    )
    (comp (ref "O11")
      (value "PIC-RPX")
      (footprint "eagle-import:TEMP-PAD")
      (libsource (lib "eagle-import") (part "PIC-RPX"))
    )
    (comp (ref "O12")
      (value "PIC-RPX")
      (footprint "eagle-import:TEMP-PAD")
      (libsource (lib "eagle-import") (part "PIC-RPX"))
    )
    (comp (ref "O13")
      (value "PIC-RPX")
      (footprint "eagle-import:TEMP-PAD")
      (libsource (lib "eagle-import") (part "PIC-RPX"))
    )
    (comp (ref "O14")
      (value "PIC-RPX")
      (footprint "eagle-import:TEMP-PAD")
      (libsource (lib "eagle-import") (part "PIC-RPX"))
    )
    (comp (ref "O15")
      (value "PIC-RPX")
      (footprint "eagle-import:TEMP-PAD")
      (libsource (lib "eagle-import") (part "PIC-RPX"))
    )
    (comp (ref "O16")
      (value "PIC-RPX")
      (footprint "eagle-import:TEMP-PAD")
      (libsource (lib "eagle-import") (part "PIC-RPX"))
    )
    (comp (ref "O17")
      (value "PIC-OUT")
      (footprint "eagle-import:TEMP-PAD")
      (libsource (lib "eagle-import") (part "PIC-OUT"))
    )
    (comp (ref "O18")
      (value "PIC-RPX")
      (footprint "eagle-import:TEMP-PAD")
      (libsource (lib "eagle-import") (part "PIC-RPX"))
    )
    (comp (ref "O19")
      (value "PIC-RPX")
      (footprint "eagle-import:TEMP-PAD")
      (libsource (lib "eagle-import") (part "PIC-RPX"))
    )
    (comp (ref "O20")
      (value "PIC-RPX")
      (footprint "eagle-import:TEMP-PAD")
      (libsource (lib "eagle-import") (part "PIC-RPX"))
    )
    (comp (ref "O21")
      (value "PIC-RPX")
      (footprint "eagle-import:TEMP-PAD")
      (libsource (lib "eagle-import") (part "PIC-RPX"))
    )
    (comp (ref "O22")
      (value "PIC-OUT")
      (footprint "eagle-import:TEMP-PAD")
      (libsource (lib "eagle-import") (part "PIC-OUT"))
    )
    (comp (ref "O23")
      (value "PIC-OUT")
      (footprint "eagle-import:TEMP-PAD")
      (libsource (lib "eagle-import") (part "PIC-OUT"))
    )
    (comp (ref "O24")
      (value "PIC-OUT")
      (footprint "eagle-import:TEMP-PAD")
      (libsource (lib "eagle-import") (part "PIC-OUT"))
    )
    (comp (ref "O25")
      (value "PIC-OUT")
      (footprint "eagle-import:TEMP-PAD")
      (libsource (lib "eagle-import") (part "PIC-OUT"))
    )
    (comp (ref "O26")
      (value "PIC-OUT")
      (footprint "eagle-import:TEMP-PAD")
      (libsource (lib "eagle-import") (part "PIC-OUT"))
    )
    (comp (ref "O27")
      (value "PIC-RPX")
      (footprint "eagle-import:TEMP-PAD")
      (libsource (lib "eagle-import") (part "PIC-RPX"))
    )
    (comp (ref "O28")
      (value "PIC-RPX")
      (footprint "eagle-import:TEMP-PAD")
      (libsource (lib "eagle-import") (part "PIC-RPX"))
    )
    (comp (ref "O29")
      (value "PIC-RPX")
      (footprint "eagle-import:TEMP-PAD")
      (libsource (lib "eagle-import") (part "PIC-RPX"))
    )
    (comp (ref "O30")
      (value "PIC-RPX")
      (footprint "eagle-import:TEMP-PAD")
      (libsource (lib "eagle-import") (part "PIC-RPX"))
    )
    (comp (ref "O31")
      (value "PIC-OUT")
      (footprint "eagle-import:TEMP-PAD")
      (libsource (lib "eagle-import") (part "PIC-OUT"))
    )
    (comp (ref "O32")
      (value "PIC-OUT")
      (footprint "eagle-import:TEMP-PAD")
      (libsource (lib "eagle-import") (part "PIC-OUT"))
    )
    (comp (ref "O33")
      (value "PIC-RPX")
      (footprint "eagle-import:TEMP-PAD")
      (libsource (lib "eagle-import") (part "PIC-RPX"))
    )
    (comp (ref "O34")
      (value "PIC-RPX")
      (footprint "eagle-import:TEMP-PAD")
      (libsource (lib "eagle-import") (part "PIC-RPX"))
    )
    (comp (ref "O35")
      (value "PIC-RPX")
      (footprint "eagle-import:TEMP-PAD")
      (libsource (lib "eagle-import") (part "PIC-RPX"))
    )
    (comp (ref "O36")
      (value "PIC-RPX")
      (footprint "eagle-import:TEMP-PAD")
      (libsource (lib "eagle-import") (part "PIC-RPX"))
    )
    (comp (ref "O37")
      (value "PIC-RPX")
      (footprint "eagle-import:TEMP-PAD")
      (libsource (lib "eagle-import") (part "PIC-RPX"))
    )
    (comp (ref "O38")
      (value "PIC-RPX")
      (footprint "eagle-import:TEMP-PAD")
      (libsource (lib "eagle-import") (part "PIC-RPX"))
    )
    (comp (ref "O39")
      (value "PIC-OUT")
      (footprint "eagle-import:TEMP-PAD")
      (libsource (lib "eagle-import") (part "PIC-OUT"))
    )
    (comp (ref "O40")
      (value "PIC-OUT")
      (footprint "eagle-import:TEMP-PAD")
      (libsource (lib "eagle-import") (part "PIC-OUT"))
    )
    (comp (ref "O41")
      (value "PIC-RPX")
      (footprint "eagle-import:TEMP-PAD")
      (libsource (lib "eagle-import") (part "PIC-RPX"))
    )
    (comp (ref "O42")
      (value "PIC-RPX")
      (footprint "eagle-import:TEMP-PAD")
      (libsource (lib "eagle-import") (part "PIC-RPX"))
    )
    (comp (ref "O43")
      (value "PIC-RPX")
      (footprint "eagle-import:TEMP-PAD")
      (libsource (lib "eagle-import") (part "PIC-RPX"))
    )
    (comp (ref "O44")
      (value "PIC-OUT")
      (footprint "eagle-import:TEMP-PAD")
      (libsource (lib "eagle-import") (part "PIC-OUT"))
    )
    (comp (ref "PCB1")
      (value "PCB-ACB")
      (footprint "eagle-import:PCB-ACB")
      (libsource (lib "eagle-import") (part "PCB-ACB-1"))
    )
    (comp (ref "PCB2")
      (value "DNP-PCB-VPS")
      (footprint "eagle-import:PCB-VPS")
      (libsource (lib "eagle-import") (part "PCB-VPS-1"))
    )
    (comp (ref "PCB3")
      (value "DNP-PCB-BT")
      (footprint "eagle-import:BT_MODULE_BRD")
      (libsource (lib "eagle-import") (part "BT_PCBBRD"))
    )
    (comp (ref "Q1")
      (value "SSM6P49NU,LFPZ")
      (footprint "eagle-import:MICRO_FET")
      (libsource (lib "eagle-import") (part "SSM6P49PZNU,LF"))
    )
    (comp (ref "Q2")
      (value "SSM6P49NU,LFPZ")
      (footprint "eagle-import:MICRO_FET")
      (libsource (lib "eagle-import") (part "SSM6P49PZNU,LF"))
    )
    (comp (ref "Q3")
      (value "FDG6303N")
      (footprint "eagle-import:SC70-6")
      (libsource (lib "eagle-import") (part "FDG6303N"))
    )
    (comp (ref "Q4")
      (value "FDG6303N")
      (footprint "eagle-import:SC70-6")
      (libsource (lib "eagle-import") (part "FDG6303N"))
    )
    (comp (ref "Q5")
      (value "FDC6506P")
      (footprint "eagle-import:SSOT-6")
      (libsource (lib "eagle-import") (part "FDC6506D"))
    )
    (comp (ref "Q6")
      (value "FDC6506P")
      (footprint "eagle-import:SSOT-6")
      (libsource (lib "eagle-import") (part "FDC6506D"))
    )
    (comp (ref "Q7")
      (value "FDG6303N")
      (footprint "eagle-import:SC70-6")
      (libsource (lib "eagle-import") (part "FDG6303N"))
    )
    (comp (ref "Q8")
      (value "FDC6506P")
      (footprint "eagle-import:SSOT-6")
      (libsource (lib "eagle-import") (part "FDC6506D"))
    )
    (comp (ref "Q9")
      (value "FDG6303N")
      (footprint "eagle-import:SC70-6")
      (libsource (lib "eagle-import") (part "FDG6303N"))
    )
    (comp (ref "Q10")
      (value "FDG6303N")
      (footprint "eagle-import:SC70-6")
      (libsource (lib "eagle-import") (part "FDG6303N"))
    )
    (comp (ref "Q11")
      (value "FDG6303N")
      (footprint "eagle-import:SC70-6")
      (libsource (lib "eagle-import") (part "FDG6303N"))
    )
    (comp (ref "Q12")
      (value "FDG6303N")
      (footprint "eagle-import:SC70-6")
      (libsource (lib "eagle-import") (part "FDG6303N"))
    )
    (comp (ref "Q13")
      (value "FDG6303N")
      (footprint "eagle-import:SC70-6")
      (libsource (lib "eagle-import") (part "FDG6303N"))
    )
    (comp (ref "Q14")
      (value "FDG6303N")
      (footprint "eagle-import:SC70-6")
      (libsource (lib "eagle-import") (part "FDG6303N"))
    )
    (comp (ref "R1")
      (value "1M")
      (footprint "eagle-import:0603")
      (libsource (lib "eagle-import") (part "R-0603"))
    )
    (comp (ref "R2")
      (value "1M")
      (footprint "eagle-import:0603")
      (libsource (lib "eagle-import") (part "R-0603"))
    )
    (comp (ref "R3")
      (value "1M")
      (footprint "eagle-import:0603")
      (libsource (lib "eagle-import") (part "R-0603"))
    )
    (comp (ref "R4")
      (value "1M")
      (footprint "eagle-import:0603")
      (libsource (lib "eagle-import") (part "R-0603"))
    )
    (comp (ref "R5")
      (value "1M")
      (footprint "eagle-import:0603")
      (libsource (lib "eagle-import") (part "R-0603"))
    )
    (comp (ref "R6")
      (value "0R")
      (footprint "eagle-import:0603")
      (libsource (lib "eagle-import") (part "R-0603"))
    )
    (comp (ref "R7")
      (value "0R")
      (footprint "eagle-import:0603")
      (libsource (lib "eagle-import") (part "R-0603"))
    )
    (comp (ref "R8")
      (value "1R")
      (footprint "eagle-import:0805")
      (libsource (lib "eagle-import") (part "R-0805"))
    )
    (comp (ref "R9")
      (value "1M")
      (footprint "eagle-import:0603")
      (libsource (lib "eagle-import") (part "R-0603"))
    )
    (comp (ref "R10")
      (value "100k")
      (footprint "eagle-import:0603")
      (libsource (lib "eagle-import") (part "R-0603"))
    )
    (comp (ref "R11")
      (value "10k")
      (footprint "eagle-import:0603")
      (libsource (lib "eagle-import") (part "R-0603"))
    )
    (comp (ref "R12")
      (value "100k")
      (footprint "eagle-import:0603")
      (libsource (lib "eagle-import") (part "R-0603"))
    )
    (comp (ref "R13")
      (value "10k")
      (footprint "eagle-import:0603")
      (libsource (lib "eagle-import") (part "R-0603"))
    )
    (comp (ref "R14")
      (value "10k")
      (footprint "eagle-import:0603")
      (libsource (lib "eagle-import") (part "R-0603"))
    )
    (comp (ref "R15")
      (value "10k")
      (footprint "eagle-import:0603")
      (libsource (lib "eagle-import") (part "R-0603"))
    )
    (comp (ref "R16")
      (value "100k")
      (footprint "eagle-import:0603")
      (libsource (lib "eagle-import") (part "R-0603"))
    )
    (comp (ref "R17")
      (value "47k")
      (footprint "eagle-import:0603")
      (libsource (lib "eagle-import") (part "R-0603"))
    )
    (comp (ref "R18")
      (value "10k")
      (footprint "eagle-import:0603")
      (libsource (lib "eagle-import") (part "R-0603"))
    )
    (comp (ref "R19")
      (value "560k")
      (footprint "eagle-import:0603")
      (libsource (lib "eagle-import") (part "R-0603"))
    )
    (comp (ref "R20")
      (value "1M")
      (footprint "eagle-import:0603")
      (libsource (lib "eagle-import") (part "R-0603"))
    )
    (comp (ref "R21")
      (value "1M")
      (footprint "eagle-import:0603")
      (libsource (lib "eagle-import") (part "R-0603"))
    )
    (comp (ref "R22")
      (value "4M99")
      (footprint "eagle-import:0603")
      (libsource (lib "eagle-import") (part "R-0603"))
    )
    (comp (ref "R23")
      (value "0R/1M")
      (footprint "eagle-import:0603")
      (libsource (lib "eagle-import") (part "R-0603"))
    )
    (comp (ref "R24")
      (value "100k")
      (footprint "eagle-import:0603")
      (libsource (lib "eagle-import") (part "R-0603"))
    )
    (comp (ref "R25")
      (value "1M")
      (footprint "eagle-import:0603")
      (libsource (lib "eagle-import") (part "R-0603"))
    )
    (comp (ref "R26")
      (value "10k")
      (footprint "eagle-import:0603")
      (libsource (lib "eagle-import") (part "R-0603"))
    )
    (comp (ref "R27")
      (value "10k")
      (footprint "eagle-import:0603")
      (libsource (lib "eagle-import") (part "R-0603"))
    )
    (comp (ref "R28")
      (value "100R")
      (footprint "eagle-import:0603")
      (libsource (lib "eagle-import") (part "R-0603"))
    )
    (comp (ref "R29")
      (value "300R")
      (footprint "eagle-import:0603")
      (libsource (lib "eagle-import") (part "R-0603"))
    )
    (comp (ref "R30")
      (value "1M")
      (footprint "eagle-import:0603")
      (libsource (lib "eagle-import") (part "R-0603"))
    )
    (comp (ref "R31")
      (value "1M")
      (footprint "eagle-import:0603")
      (libsource (lib "eagle-import") (part "R-0603"))
    )
    (comp (ref "R32")
      (value "1M")
      (footprint "eagle-import:0603")
      (libsource (lib "eagle-import") (part "R-0603"))
    )
    (comp (ref "R33")
      (value "4M99")
      (footprint "eagle-import:0603")
      (libsource (lib "eagle-import") (part "R-0603"))
    )
    (comp (ref "R34")
      (value "1M")
      (footprint "eagle-import:0603")
      (libsource (lib "eagle-import") (part "R-0603"))
    )
    (comp (ref "R35")
      (value "1k")
      (footprint "eagle-import:0805")
      (libsource (lib "eagle-import") (part "R-0805"))
    )
    (comp (ref "R36")
      (value "1k")
      (footprint "eagle-import:0805")
      (libsource (lib "eagle-import") (part "R-0805"))
    )
    (comp (ref "R37")
      (value "1k")
      (footprint "eagle-import:0805")
      (libsource (lib "eagle-import") (part "R-0805"))
    )
    (comp (ref "R38")
      (value "1k")
      (footprint "eagle-import:0805")
      (libsource (lib "eagle-import") (part "R-0805"))
    )
    (comp (ref "R39")
      (value "0.025R")
      (footprint "eagle-import:0805")
      (libsource (lib "eagle-import") (part "R-0805"))
    )
    (comp (ref "R40")
      (value "300k")
      (footprint "eagle-import:0603")
      (libsource (lib "eagle-import") (part "R-0603"))
    )
    (comp (ref "R41")
      (value "1M")
      (footprint "eagle-import:0603")
      (libsource (lib "eagle-import") (part "R-0603"))
    )
    (comp (ref "R42")
      (value "1M")
      (footprint "eagle-import:0603")
      (libsource (lib "eagle-import") (part "R-0603"))
    )
    (comp (ref "R43")
      (value "300k")
      (footprint "eagle-import:0603")
      (libsource (lib "eagle-import") (part "R-0603"))
    )
    (comp (ref "R44")
      (value "1M")
      (footprint "eagle-import:0603")
      (libsource (lib "eagle-import") (part "R-0603"))
    )
    (comp (ref "R45")
      (value "1M")
      (footprint "eagle-import:0603")
      (libsource (lib "eagle-import") (part "R-0603"))
    )
    (comp (ref "R46")
      (value "560k")
      (footprint "eagle-import:0603")
      (libsource (lib "eagle-import") (part "R-0603"))
    )
    (comp (ref "R47")
      (value "100k")
      (footprint "eagle-import:0603")
      (libsource (lib "eagle-import") (part "R-0603"))
    )
    (comp (ref "R48")
      (value "1M")
      (footprint "eagle-import:0603")
      (libsource (lib "eagle-import") (part "R-0603"))
    )
    (comp (ref "R49")
      (value "1M")
      (footprint "eagle-import:0603")
      (libsource (lib "eagle-import") (part "R-0603"))
    )
    (comp (ref "R50")
      (value "1M")
      (footprint "eagle-import:0603")
      (libsource (lib "eagle-import") (part "R-0603"))
    )
    (comp (ref "R51")
      (value "300k")
      (footprint "eagle-import:0603")
      (libsource (lib "eagle-import") (part "R-0603"))
    )
    (comp (ref "R52")
      (value "1M")
      (footprint "eagle-import:0603")
      (libsource (lib "eagle-import") (part "R-0603"))
    )
    (comp (ref "R53")
      (value "300k")
      (footprint "eagle-import:0603")
      (libsource (lib "eagle-import") (part "R-0603"))
    )
    (comp (ref "R54")
      (value "1M")
      (footprint "eagle-import:0603")
      (libsource (lib "eagle-import") (part "R-0603"))
    )
    (comp (ref "R55")
      (value "1M")
      (footprint "eagle-import:0603")
      (libsource (lib "eagle-import") (part "R-0603"))
    )
    (comp (ref "R56")
      (value "1M")
      (footprint "eagle-import:0603")
      (libsource (lib "eagle-import") (part "R-0603"))
    )
    (comp (ref "R57")
      (value "300k")
      (footprint "eagle-import:0603")
      (libsource (lib "eagle-import") (part "R-0603"))
    )
    (comp (ref "R58")
      (value "1M")
      (footprint "eagle-import:0603")
      (libsource (lib "eagle-import") (part "R-0603"))
    )
    (comp (ref "R59")
      (value "300k")
      (footprint "eagle-import:0603")
      (libsource (lib "eagle-import") (part "R-0603"))
    )
    (comp (ref "R60")
      (value "1M")
      (footprint "eagle-import:0603")
      (libsource (lib "eagle-import") (part "R-0603"))
    )
    (comp (ref "R61")
      (value "1M")
      (footprint "eagle-import:0603")
      (libsource (lib "eagle-import") (part "R-0603"))
    )
    (comp (ref "R62")
      (value "100R")
      (footprint "eagle-import:0603")
      (libsource (lib "eagle-import") (part "R-0603"))
    )
    (comp (ref "R63")
      (value "1k->4k7")
      (footprint "eagle-import:0603")
      (libsource (lib "eagle-import") (part "R-0603"))
    )
    (comp (ref "R64")
      (value "1k")
      (footprint "eagle-import:0603")
      (libsource (lib "eagle-import") (part "R-0603"))
    )
    (comp (ref "R65")
      (value "1M")
      (footprint "eagle-import:0603")
      (libsource (lib "eagle-import") (part "R-0603"))
    )
    (comp (ref "R66")
      (value "100k")
      (footprint "eagle-import:0603")
      (libsource (lib "eagle-import") (part "R-0603"))
    )
    (comp (ref "R67")
      (value "1M")
      (footprint "eagle-import:0603")
      (libsource (lib "eagle-import") (part "R-0603"))
    )
    (comp (ref "R68")
      (value "100R")
      (footprint "eagle-import:0603")
      (libsource (lib "eagle-import") (part "R-0603"))
    )
    (comp (ref "R69")
      (value "1k->4k7")
      (footprint "eagle-import:0603")
      (libsource (lib "eagle-import") (part "R-0603"))
    )
    (comp (ref "R70")
      (value "1k")
      (footprint "eagle-import:0603")
      (libsource (lib "eagle-import") (part "R-0603"))
    )
    (comp (ref "R71")
      (value "10k")
      (footprint "eagle-import:0603")
      (libsource (lib "eagle-import") (part "R-0603"))
    )
    (comp (ref "R72")
      (value "1M")
      (footprint "eagle-import:0603")
      (libsource (lib "eagle-import") (part "R-0603"))
    )
    (comp (ref "R73")
      (value "1M")
      (footprint "eagle-import:0603")
      (libsource (lib "eagle-import") (part "R-0603"))
    )
    (comp (ref "R74")
      (value "100k")
      (footprint "eagle-import:0603")
      (libsource (lib "eagle-import") (part "R-0603"))
    )
    (comp (ref "R75")
      (value "100k")
      (footprint "eagle-import:0603")
      (libsource (lib "eagle-import") (part "R-0603"))
    )
    (comp (ref "R76")
      (value "1M")
      (footprint "eagle-import:0603")
      (libsource (lib "eagle-import") (part "R-0603"))
    )
    (comp (ref "R77")
      (value "47k")
      (footprint "eagle-import:0603")
      (libsource (lib "eagle-import") (part "R-0603"))
    )
    (comp (ref "R78")
      (value "100R")
      (footprint "eagle-import:0603")
      (libsource (lib "eagle-import") (part "R-0603"))
    )
    (comp (ref "R79")
      (value "1k->4k7")
      (footprint "eagle-import:0603")
      (libsource (lib "eagle-import") (part "R-0603"))
    )
    (comp (ref "R80")
      (value "1k")
      (footprint "eagle-import:0603")
      (libsource (lib "eagle-import") (part "R-0603"))
    )
    (comp (ref "R81")
      (value "100k")
      (footprint "eagle-import:0603")
      (libsource (lib "eagle-import") (part "R-0603"))
    )
    (comp (ref "R82")
      (value "1M")
      (footprint "eagle-import:0603")
      (libsource (lib "eagle-import") (part "R-0603"))
    )
    (comp (ref "R83")
      (value "1M")
      (footprint "eagle-import:0603")
      (libsource (lib "eagle-import") (part "R-0603"))
    )
    (comp (ref "R84")
      (value "100R")
      (footprint "eagle-import:0603")
      (libsource (lib "eagle-import") (part "R-0603"))
    )
    (comp (ref "R85")
      (value "1k->4k7")
      (footprint "eagle-import:0603")
      (libsource (lib "eagle-import") (part "R-0603"))
    )
    (comp (ref "R86")
      (value "1k")
      (footprint "eagle-import:0603")
      (libsource (lib "eagle-import") (part "R-0603"))
    )
    (comp (ref "R87")
      (value "1M")
      (footprint "eagle-import:0603")
      (libsource (lib "eagle-import") (part "R-0603"))
    )
    (comp (ref "R88")
      (value "1M")
      (footprint "eagle-import:0603")
      (libsource (lib "eagle-import") (part "R-0603"))
    )
    (comp (ref "R89")
      (value "100k")
      (footprint "eagle-import:0603")
      (libsource (lib "eagle-import") (part "R-0603"))
    )
    (comp (ref "R90")
      (value "1k")
      (footprint "eagle-import:0603")
      (libsource (lib "eagle-import") (part "R-0603"))
    )
    (comp (ref "R91")
      (value "10k")
      (footprint "eagle-import:0603")
      (libsource (lib "eagle-import") (part "R-0603"))
    )
    (comp (ref "R92")
      (value "10R")
      (footprint "eagle-import:0603")
      (libsource (lib "eagle-import") (part "R-0603"))
    )
    (comp (ref "R93")
      (value "300R")
      (footprint "eagle-import:0603")
      (libsource (lib "eagle-import") (part "R-0603"))
    )
    (comp (ref "R94")
      (value "180k")
      (footprint "eagle-import:0603")
      (libsource (lib "eagle-import") (part "R-0603"))
    )
    (comp (ref "R95")
      (value "4M99")
      (footprint "eagle-import:0603")
      (libsource (lib "eagle-import") (part "R-0603"))
    )
    (comp (ref "R96")
      (value "560k")
      (footprint "eagle-import:0603")
      (libsource (lib "eagle-import") (part "R-0603"))
    )
    (comp (ref "R97")
      (value "180k")
      (footprint "eagle-import:0603")
      (libsource (lib "eagle-import") (part "R-0603"))
    )
    (comp (ref "R98")
      (value "4M99")
      (footprint "eagle-import:0603")
      (libsource (lib "eagle-import") (part "R-0603"))
    )
    (comp (ref "R99")
      (value "560k")
      (footprint "eagle-import:0603")
      (libsource (lib "eagle-import") (part "R-0603"))
    )
    (comp (ref "R100")
      (value "2k2")
      (footprint "eagle-import:0603")
      (libsource (lib "eagle-import") (part "R-0603"))
    )
    (comp (ref "R101")
      (value "2k2")
      (footprint "eagle-import:0603")
      (libsource (lib "eagle-import") (part "R-0603"))
    )
    (comp (ref "R102")
      (value "1k")
      (footprint "eagle-import:0603")
      (libsource (lib "eagle-import") (part "R-0603"))
    )
    (comp (ref "R103")
      (value "300R")
      (footprint "eagle-import:0603")
      (libsource (lib "eagle-import") (part "R-0603"))
    )
    (comp (ref "R104")
      (value "1R")
      (footprint "eagle-import:0805")
      (libsource (lib "eagle-import") (part "R-0805"))
    )
    (comp (ref "R105")
      (value "1R")
      (footprint "eagle-import:0805")
      (libsource (lib "eagle-import") (part "R-0805"))
    )
    (comp (ref "R106")
      (value "1R")
      (footprint "eagle-import:0805")
      (libsource (lib "eagle-import") (part "R-0805"))
    )
    (comp (ref "R107")
      (value "100k")
      (footprint "eagle-import:0603")
      (libsource (lib "eagle-import") (part "R-0603"))
    )
    (comp (ref "R108")
      (value "10R->1R->0R")
      (footprint "eagle-import:0603")
      (libsource (lib "eagle-import") (part "R-0603"))
    )
    (comp (ref "R109")
      (value "10R->1R->0R")
      (footprint "eagle-import:0603")
      (libsource (lib "eagle-import") (part "R-0603"))
    )
    (comp (ref "R110")
      (value "100R")
      (footprint "eagle-import:0603")
      (libsource (lib "eagle-import") (part "R-0603"))
    )
    (comp (ref "R111")
      (value "100R")
      (footprint "eagle-import:0603")
      (libsource (lib "eagle-import") (part "R-0603"))
    )
    (comp (ref "R112")
      (value "1M")
      (footprint "eagle-import:0603")
      (libsource (lib "eagle-import") (part "R-0603"))
    )
    (comp (ref "R113")
      (value "100R")
      (footprint "eagle-import:0603")
      (libsource (lib "eagle-import") (part "R-0603"))
    )
    (comp (ref "R114")
      (value "100R")
      (footprint "eagle-import:0603")
      (libsource (lib "eagle-import") (part "R-0603"))
    )
    (comp (ref "R115")
      (value "100R")
      (footprint "eagle-import:0603")
      (libsource (lib "eagle-import") (part "R-0603"))
    )
    (comp (ref "R116")
      (value "100R")
      (footprint "eagle-import:0603")
      (libsource (lib "eagle-import") (part "R-0603"))
    )
    (comp (ref "R117")
      (value "100R")
      (footprint "eagle-import:0603")
      (libsource (lib "eagle-import") (part "R-0603"))
    )
    (comp (ref "R118")
      (value "1M")
      (footprint "eagle-import:0603")
      (libsource (lib "eagle-import") (part "R-0603"))
    )
    (comp (ref "R119")
      (value "100R")
      (footprint "eagle-import:0603")
      (libsource (lib "eagle-import") (part "R-0603"))
    )
    (comp (ref "R122")
      (value "100R")
      (footprint "eagle-import:0603")
      (libsource (lib "eagle-import") (part "R-0603"))
    )
    (comp (ref "R123")
      (value "100R")
      (footprint "eagle-import:0603")
      (libsource (lib "eagle-import") (part "R-0603"))
    )
    (comp (ref "R124")
      (value "0R")
      (footprint "eagle-import:0603")
      (libsource (lib "eagle-import") (part "R-0603"))
    )
    (comp (ref "R125")
      (value "0R")
      (footprint "eagle-import:0603")
      (libsource (lib "eagle-import") (part "R-0603"))
    )
    (comp (ref "R126")
      (value "0R")
      (footprint "eagle-import:0603")
      (libsource (lib "eagle-import") (part "R-0603"))
    )
    (comp (ref "R127")
      (value "1M")
      (footprint "eagle-import:0603")
      (libsource (lib "eagle-import") (part "R-0603"))
    )
    (comp (ref "R128")
      (value "10k")
      (footprint "eagle-import:0603")
      (libsource (lib "eagle-import") (part "R-0603"))
    )
    (comp (ref "R129")
      (value "DNP/0R")
      (footprint "eagle-import:0603")
      (libsource (lib "eagle-import") (part "R-0603"))
    )
    (comp (ref "R130")
      (value "100k")
      (footprint "eagle-import:0603")
      (libsource (lib "eagle-import") (part "R-0603"))
    )
    (comp (ref "R131")
      (value "100k")
      (footprint "eagle-import:0603")
      (libsource (lib "eagle-import") (part "R-0603"))
    )
    (comp (ref "R132")
      (value "1M")
      (footprint "eagle-import:0603")
      (libsource (lib "eagle-import") (part "R-0603"))
    )
    (comp (ref "REF1")
      (value "REF")
      (footprint "eagle-import:REF")
      (libsource (lib "eagle-import") (part "REF"))
    )
    (comp (ref "REF2")
      (value "REF")
      (footprint "eagle-import:REF")
      (libsource (lib "eagle-import") (part "REF"))
    )
    (comp (ref "T1")
      (value "PIC-OUT")
      (footprint "eagle-import:TEMP-PAD")
      (libsource (lib "eagle-import") (part "PIC-OUT"))
    )
    (comp (ref "T2")
      (value "PIC-OUT")
      (footprint "eagle-import:TEMP-PAD")
      (libsource (lib "eagle-import") (part "PIC-OUT"))
    )
    (comp (ref "T3")
      (value "PIC-RPX")
      (footprint "eagle-import:TEMP-PAD")
      (libsource (lib "eagle-import") (part "PIC-RPX"))
    )
    (comp (ref "T4")
      (value "PIC-OUT")
      (footprint "eagle-import:TEMP-PAD")
      (libsource (lib "eagle-import") (part "PIC-OUT"))
    )
    (comp (ref "T5")
      (value "PIC-OUT")
      (footprint "eagle-import:TEMP-PAD")
      (libsource (lib "eagle-import") (part "PIC-OUT"))
    )
    (comp (ref "T6")
      (value "PIC-OUT")
      (footprint "eagle-import:TEMP-PAD")
      (libsource (lib "eagle-import") (part "PIC-OUT"))
    )
    (comp (ref "T7")
      (value "PIC-OUT")
      (footprint "eagle-import:TEMP-PAD")
      (libsource (lib "eagle-import") (part "PIC-OUT"))
    )
    (comp (ref "T8")
      (value "PIC-OUT")
      (footprint "eagle-import:TEMP-PAD")
      (libsource (lib "eagle-import") (part "PIC-OUT"))
    )
    (comp (ref "T9")
      (value "PIC-RPX")
      (footprint "eagle-import:TEMP-PAD")
      (libsource (lib "eagle-import") (part "PIC-RPX"))
    )
    (comp (ref "T10")
      (value "PIC-RPX")
      (footprint "eagle-import:TEMP-PAD")
      (libsource (lib "eagle-import") (part "PIC-RPX"))
    )
    (comp (ref "T11")
      (value "PIC-RPX")
      (footprint "eagle-import:TEMP-PAD")
      (libsource (lib "eagle-import") (part "PIC-RPX"))
    )
    (comp (ref "T12")
      (value "PIC-RPX")
      (footprint "eagle-import:TEMP-PAD")
      (libsource (lib "eagle-import") (part "PIC-RPX"))
    )
    (comp (ref "T13")
      (value "PIC-RPX")
      (footprint "eagle-import:TEMP-PAD")
      (libsource (lib "eagle-import") (part "PIC-RPX"))
    )
    (comp (ref "T14")
      (value "PIC-RPX")
      (footprint "eagle-import:TEMP-PAD")
      (libsource (lib "eagle-import") (part "PIC-RPX"))
    )
    (comp (ref "T15")
      (value "PIC-OUT")
      (footprint "eagle-import:TEMP-PAD")
      (libsource (lib "eagle-import") (part "PIC-OUT"))
    )
    (comp (ref "T16")
      (value "PIC-RPX")
      (footprint "eagle-import:TEMP-PAD")
      (libsource (lib "eagle-import") (part "PIC-RPX"))
    )
    (comp (ref "T17")
      (value "PIC-RPX")
      (footprint "eagle-import:TEMP-PAD")
      (libsource (lib "eagle-import") (part "PIC-RPX"))
    )
    (comp (ref "T18")
      (value "PIC-RPX")
      (footprint "eagle-import:TEMP-PAD")
      (libsource (lib "eagle-import") (part "PIC-RPX"))
    )
    (comp (ref "T19")
      (value "PIC-RPX")
      (footprint "eagle-import:TEMP-PAD")
      (libsource (lib "eagle-import") (part "PIC-RPX"))
    )
    (comp (ref "T20")
      (value "PIC-OUT")
      (footprint "eagle-import:TEMP-PAD")
      (libsource (lib "eagle-import") (part "PIC-OUT"))
    )
    (comp (ref "T21")
      (value "PIC-OUT")
      (footprint "eagle-import:TEMP-PAD")
      (libsource (lib "eagle-import") (part "PIC-OUT"))
    )
    (comp (ref "T22")
      (value "PIC-RPX")
      (footprint "eagle-import:TEMP-PAD")
      (libsource (lib "eagle-import") (part "PIC-RPX"))
    )
    (comp (ref "T23")
      (value "PIC-RPX")
      (footprint "eagle-import:TEMP-PAD")
      (libsource (lib "eagle-import") (part "PIC-RPX"))
    )
    (comp (ref "T24")
      (value "PIC-RPX")
      (footprint "eagle-import:TEMP-PAD")
      (libsource (lib "eagle-import") (part "PIC-RPX"))
    )
    (comp (ref "T25")
      (value "PIC-OUT")
      (footprint "eagle-import:TEMP-PAD")
      (libsource (lib "eagle-import") (part "PIC-OUT"))
    )
    (comp (ref "T26")
      (value "PIC-OUT")
      (footprint "eagle-import:TEMP-PAD")
      (libsource (lib "eagle-import") (part "PIC-OUT"))
    )
    (comp (ref "T27")
      (value "PIC-OUT")
      (footprint "eagle-import:TEMP-PAD")
      (libsource (lib "eagle-import") (part "PIC-OUT"))
    )
    (comp (ref "T28")
      (value "PIC-OUT")
      (footprint "eagle-import:TEMP-PAD")
      (libsource (lib "eagle-import") (part "PIC-OUT"))
    )
    (comp (ref "T29")
      (value "PIC-OUT")
      (footprint "eagle-import:TEMP-PAD")
      (libsource (lib "eagle-import") (part "PIC-OUT"))
    )
    (comp (ref "T30")
      (value "PIC-OUT")
      (footprint "eagle-import:TEMP-PAD")
      (libsource (lib "eagle-import") (part "PIC-OUT"))
    )
    (comp (ref "T31")
      (value "PIC-OUT")
      (footprint "eagle-import:TEMP-PAD")
      (libsource (lib "eagle-import") (part "PIC-OUT"))
    )
    (comp (ref "T32")
      (value "PIC-OUT")
      (footprint "eagle-import:TEMP-PAD")
      (libsource (lib "eagle-import") (part "PIC-OUT"))
    )
    (comp (ref "T33")
      (value "PIC-OUT")
      (footprint "eagle-import:TEMP-PAD")
      (libsource (lib "eagle-import") (part "PIC-OUT"))
    )
    (comp (ref "T34")
      (value "PIC-RPX")
      (footprint "eagle-import:TEMP-PAD")
      (libsource (lib "eagle-import") (part "PIC-RPX"))
    )
    (comp (ref "T35")
      (value "PIC-RPX")
      (footprint "eagle-import:TEMP-PAD")
      (libsource (lib "eagle-import") (part "PIC-RPX"))
    )
    (comp (ref "T36")
      (value "PIC-OUT")
      (footprint "eagle-import:TEMP-PAD")
      (libsource (lib "eagle-import") (part "PIC-OUT"))
    )
    (comp (ref "T37")
      (value "PIN-AN")
      (footprint "eagle-import:TEMP-PAD")
      (libsource (lib "eagle-import") (part "PIN-AN"))
    )
    (comp (ref "T38")
      (value "PIN-AN")
      (footprint "eagle-import:TEMP-PAD")
      (libsource (lib "eagle-import") (part "PIN-AN"))
    )
    (comp (ref "T39")
      (value "PIN-AN")
      (footprint "eagle-import:TEMP-PAD")
      (libsource (lib "eagle-import") (part "PIN-AN"))
    )
    (comp (ref "T40")
      (value "PIC-RPX")
      (footprint "eagle-import:TEMP-PAD")
      (libsource (lib "eagle-import") (part "PIC-RPX"))
    )
    (comp (ref "T41")
      (value "PIC-RPX")
      (footprint "eagle-import:TEMP-PAD")
      (libsource (lib "eagle-import") (part "PIC-RPX"))
    )
    (comp (ref "T42")
      (value "PIC-OUT")
      (footprint "eagle-import:TEMP-PAD")
      (libsource (lib "eagle-import") (part "PIC-OUT"))
    )
    (comp (ref "T43")
      (value "PIC-RPX")
      (footprint "eagle-import:TEMP-PAD")
      (libsource (lib "eagle-import") (part "PIC-RPX"))
    )
    (comp (ref "T44")
      (value "PIC-OUT")
      (footprint "eagle-import:TEMP-PAD")
      (libsource (lib "eagle-import") (part "PIC-OUT"))
    )
    (comp (ref "T45")
      (value "PIC-RPX")
      (footprint "eagle-import:TEMP-PAD")
      (libsource (lib "eagle-import") (part "PIC-RPX"))
    )
    (comp (ref "T46")
      (value "PIC-RPX")
      (footprint "eagle-import:TEMP-PAD")
      (libsource (lib "eagle-import") (part "PIC-RPX"))
    )
    (comp (ref "TP1")
      (value "DNP-TestPoint")
      (footprint "eagle-import:SMD_ROUND_1MM")
      (libsource (lib "eagle-import") (part "ROUND_SMD1MM"))
    )
    (comp (ref "TP2")
      (value "DNP-TestPoint")
      (footprint "eagle-import:TH_ROUND_14MM08MM")
      (libsource (lib "eagle-import") (part "ROUND_SMDTH1.4MM"))
    )
    (comp (ref "TP4")
      (value "DNP-TestPoint")
      (footprint "eagle-import:TH_ROUND_14MM08MM")
      (libsource (lib "eagle-import") (part "ROUND_SMDTH1.4MM"))
    )
    (comp (ref "X1")
      (value "8MHz-5x3.2mm")
      (footprint "eagle-import:7B")
      (libsource (lib "eagle-import") (part "XTAL-7B"))
    )
  )
  (nets
    (net (code "1") (name "+3.3V") (class "Default")
      (node (ref "C15") (pin "1") (pinfunction "1_1") (pintype "passive"))
      (node (ref "C21") (pin "1") (pinfunction "1_1") (pintype "passive"))
      (node (ref "C47") (pin "1") (pinfunction "1_1") (pintype "passive"))
      (node (ref "C48") (pin "1") (pinfunction "1_1") (pintype "passive"))
      (node (ref "C49") (pin "1") (pinfunction "1_1") (pintype "passive"))
      (node (ref "C50") (pin "1") (pinfunction "1_1") (pintype "passive"))
      (node (ref "C51") (pin "1") (pinfunction "1_1") (pintype "passive"))
      (node (ref "C52") (pin "1") (pinfunction "1_1") (pintype "passive"))
      (node (ref "C68") (pin "1") (pinfunction "1_1") (pintype "passive"))
      (node (ref "C69") (pin "1") (pinfunction "1_1") (pintype "passive"))
      (node (ref "C70") (pin "1") (pinfunction "1_1") (pintype "passive"))
      (node (ref "C81") (pin "+") (pinfunction "+_+") (pintype "passive"))
      (node (ref "IC1") (pin "16") (pinfunction "VDD3_16") (pintype "input"))
      (node (ref "IC1") (pin "2") (pinfunction "VDD2_2") (pintype "input"))
      (node (ref "IC1") (pin "37") (pinfunction "VDD4_37") (pintype "input"))
      (node (ref "IC1") (pin "46") (pinfunction "VDD5_46") (pintype "input"))
      (node (ref "IC1") (pin "55") (pinfunction "VUSB3V3_55") (pintype "input"))
      (node (ref "IC1") (pin "62") (pinfunction "VDD6_62") (pintype "input"))
      (node (ref "IC1") (pin "86") (pinfunction "VDD1_86") (pintype "input"))
      (node (ref "J14") (pin "2") (pinfunction "2_2") (pintype "passive"))
      (node (ref "J17") (pin "2") (pinfunction "2_2") (pintype "passive"))
      (node (ref "L13") (pin "1") (pinfunction "1_1") (pintype "passive"))
      (node (ref "R103") (pin "2") (pinfunction "2_2") (pintype "passive"))
      (node (ref "R104") (pin "2") (pinfunction "2_2") (pintype "passive"))
      (node (ref "R105") (pin "2") (pinfunction "2_2") (pintype "passive"))
      (node (ref "R106") (pin "2") (pinfunction "2_2") (pintype "passive"))
      (node (ref "R129") (pin "1") (pinfunction "1_1") (pintype "passive"))
      (node (ref "R28") (pin "2") (pinfunction "2_2") (pintype "passive"))
      (node (ref "R65") (pin "1") (pinfunction "1_1") (pintype "passive"))
      (node (ref "R66") (pin "2") (pinfunction "2_2") (pintype "passive"))
      (node (ref "R74") (pin "2") (pinfunction "2_2") (pintype "passive"))
      (node (ref "R8") (pin "2") (pinfunction "2_2") (pintype "passive"))
      (node (ref "R81") (pin "2") (pinfunction "2_2") (pintype "passive"))
      (node (ref "R82") (pin "1") (pinfunction "1_1") (pintype "passive"))
      (node (ref "R87") (pin "1") (pinfunction "1_1") (pintype "passive"))
      (node (ref "R89") (pin "2") (pinfunction "2_2") (pintype "passive"))
      (node (ref "R9") (pin "2") (pinfunction "2_2") (pintype "passive"))
      (node (ref "R91") (pin "2") (pinfunction "2_2") (pintype "passive"))
    )
    (net (code "2") (name "+3.3V{slash}1") (class "Default")
      (node (ref "C1") (pin "1") (pinfunction "1_1") (pintype "passive"))
      (node (ref "C2") (pin "1") (pinfunction "1_1") (pintype "passive"))
      (node (ref "C28") (pin "1") (pinfunction "1_1") (pintype "passive"))
      (node (ref "C87") (pin "+") (pinfunction "+_+") (pintype "passive"))
      (node (ref "IC11") (pin "2") (pinfunction "A1_2") (pintype "input"))
      (node (ref "IC11") (pin "8") (pinfunction "VCC_8") (pintype "input"))
      (node (ref "IC2") (pin "37") (pinfunction "VCC_37") (pintype "input"))
      (node (ref "IC3") (pin "20") (pinfunction "VCC_20") (pintype "bidirectional"))
      (node (ref "IC4") (pin "20") (pinfunction "VCC_20") (pintype "bidirectional"))
      (node (ref "IC7") (pin "8") (pinfunction "VCC_8") (pintype "input"))
      (node (ref "Q2") (pin "3") (pinfunction "D_3") (pintype "passive"))
      (node (ref "Q2") (pin "P2") (pinfunction "D1_P2") (pintype "passive"))
      (node (ref "R18") (pin "1") (pinfunction "1_1") (pintype "passive"))
      (node (ref "R26") (pin "1") (pinfunction "1_1") (pintype "passive"))
      (node (ref "R27") (pin "1") (pinfunction "1_1") (pintype "passive"))
      (node (ref "R3") (pin "2") (pinfunction "2_2") (pintype "passive"))
      (node (ref "R4") (pin "2") (pinfunction "2_2") (pintype "passive"))
    )
    (net (code "3") (name "+3.3V{slash}2") (class "Default")
      (node (ref "C41") (pin "1") (pinfunction "1_1") (pintype "passive"))
      (node (ref "C86") (pin "+") (pinfunction "+_+") (pintype "passive"))
      (node (ref "IC12") (pin "8") (pinfunction "VCC_8") (pintype "input"))
      (node (ref "Q1") (pin "3") (pinfunction "D_3") (pintype "passive"))
      (node (ref "Q1") (pin "P2") (pinfunction "D1_P2") (pintype "passive"))
      (node (ref "R30") (pin "2") (pinfunction "2_2") (pintype "passive"))
      (node (ref "R34") (pin "1") (pinfunction "1_1") (pintype "passive"))
      (node (ref "R72") (pin "1") (pinfunction "1_1") (pintype "passive"))
      (node (ref "R73") (pin "2") (pinfunction "2_2") (pintype "passive"))
    )
    (net (code "4") (name "/+3.3V{slash}VPS") (class "Default")
      (node (ref "C27") (pin "1") (pinfunction "1_1") (pintype "passive"))
      (node (ref "C82") (pin "1") (pinfunction "1_1") (pintype "passive"))
      (node (ref "IC9") (pin "3") (pinfunction "/WP_3") (pintype "input"))
      (node (ref "IC9") (pin "7") (pinfunction "/HOLD_7") (pintype "input"))
      (node (ref "IC9") (pin "8") (pinfunction "VCC_8") (pintype "input"))
      (node (ref "J11") (pin "4") (pinfunction "VDD_4") (pintype "passive"))
      (node (ref "J15") (pin "1") (pinfunction "1_1") (pintype "passive"))
      (node (ref "Q2") (pin "6") (pinfunction "D_6") (pintype "passive"))
      (node (ref "Q2") (pin "P1") (pinfunction "D1_P1") (pintype "passive"))
      (node (ref "R25") (pin "2") (pinfunction "2_2") (pintype "passive"))
    )
    (net (code "5") (name "/1.5V-CAM") (class "Default")
      (node (ref "L5") (pin "1") (pinfunction "1_1") (pintype "passive"))
      (node (ref "L6") (pin "2") (pinfunction "2_2") (pintype "passive"))
      (node (ref "R126") (pin "1") (pinfunction "1_1") (pintype "passive"))
    )
    (net (code "6") (name "/3.3V{slash}CAM") (class "Default")
      (node (ref "C16") (pin "+") (pinfunction "+_+") (pintype "passive"))
      (node (ref "C17") (pin "+") (pinfunction "+_+") (pintype "passive"))
      (node (ref "C18") (pin "1") (pinfunction "1_1") (pintype "passive"))
      (node (ref "IC5") (pin "1") (pinfunction "IN_1") (pintype "input"))
      (node (ref "IC5") (pin "3") (pinfunction "EN_3") (pintype "input"))
      (node (ref "L1") (pin "1") (pinfunction "1_1") (pintype "passive"))
      (node (ref "L2") (pin "2") (pinfunction "2_2") (pintype "passive"))
      (node (ref "L3") (pin "1") (pinfunction "1_1") (pintype "passive"))
      (node (ref "L4") (pin "2") (pinfunction "2_2") (pintype "passive"))
      (node (ref "Q1") (pin "6") (pinfunction "D_6") (pintype "passive"))
      (node (ref "Q1") (pin "P1") (pinfunction "D1_P1") (pintype "passive"))
      (node (ref "R11") (pin "2") (pinfunction "2_2") (pintype "passive"))
      (node (ref "R12") (pin "2") (pinfunction "2_2") (pintype "passive"))
      (node (ref "R13") (pin "2") (pinfunction "2_2") (pintype "passive"))
      (node (ref "R14") (pin "2") (pinfunction "2_2") (pintype "passive"))
      (node (ref "R15") (pin "2") (pinfunction "2_2") (pintype "passive"))
      (node (ref "R16") (pin "2") (pinfunction "2_2") (pintype "passive"))
    )
    (net (code "7") (name "/A+") (class "Default")
      (node (ref "J3") (pin "4") (pinfunction "4_4") (pintype "passive"))
      (node (ref "J4") (pin "4") (pinfunction "4_4") (pintype "passive"))
      (node (ref "L8") (pin "2") (pinfunction "2_2") (pintype "passive"))
    )
    (net (code "8") (name "/A++") (class "Default")
      (node (ref "IC12") (pin "6") (pinfunction "A_6") (pintype "bidirectional"))
      (node (ref "IC14") (pin "3") (pinfunction "3_3") (pintype "passive"))
      (node (ref "R109") (pin "2") (pinfunction "2_2") (pintype "passive"))
      (node (ref "R32") (pin "2") (pinfunction "2_2") (pintype "passive"))
      (node (ref "R34") (pin "2") (pinfunction "2_2") (pintype "passive"))
    )
    (net (code "9") (name "/A0") (class "Default")
      (node (ref "IC2") (pin "20") (pinfunction "A5_20") (pintype "input"))
      (node (ref "IC3") (pin "12") (pinfunction "Q7_12") (pintype "tri_state"))
    )
    (net (code "10") (name "/A1") (class "Default")
      (node (ref "IC2") (pin "21") (pinfunction "A4_21") (pintype "input"))
      (node (ref "IC3") (pin "13") (pinfunction "Q6_13") (pintype "tri_state"))
    )
    (net (code "11") (name "/A2") (class "Default")
      (node (ref "IC2") (pin "22") (pinfunction "A3_22") (pintype "input"))
      (node (ref "IC3") (pin "14") (pinfunction "Q5_14") (pintype "tri_state"))
    )
    (net (code "12") (name "/A3") (class "Default")
      (node (ref "IC2") (pin "23") (pinfunction "A2_23") (pintype "input"))
      (node (ref "IC3") (pin "15") (pinfunction "Q4_15") (pintype "tri_state"))
    )
    (net (code "13") (name "/A4") (class "Default")
      (node (ref "IC2") (pin "24") (pinfunction "A1_24") (pintype "input"))
      (node (ref "IC3") (pin "16") (pinfunction "Q3_16") (pintype "tri_state"))
    )
    (net (code "14") (name "/A5") (class "Default")
      (node (ref "IC2") (pin "25") (pinfunction "A0_25") (pintype "input"))
      (node (ref "IC3") (pin "17") (pinfunction "Q2_17") (pintype "tri_state"))
    )
    (net (code "15") (name "/A6") (class "Default")
      (node (ref "IC2") (pin "45") (pinfunction "A-1/D15_45") (pintype "tri_state"))
      (node (ref "IC3") (pin "18") (pinfunction "Q1_18") (pintype "tri_state"))
    )
    (net (code "16") (name "/A7") (class "Default")
      (node (ref "IC2") (pin "48") (pinfunction "A16_48") (pintype "input"))
      (node (ref "IC3") (pin "19") (pinfunction "Q0_19") (pintype "tri_state"))
    )
    (net (code "17") (name "/A8") (class "Default")
      (node (ref "IC2") (pin "19") (pinfunction "A6_19") (pintype "input"))
      (node (ref "IC4") (pin "19") (pinfunction "Q0_19") (pintype "tri_state"))
    )
    (net (code "18") (name "/A9") (class "Default")
      (node (ref "IC2") (pin "18") (pinfunction "A7_18") (pintype "input"))
      (node (ref "IC4") (pin "18") (pinfunction "Q1_18") (pintype "tri_state"))
    )
    (net (code "19") (name "/A10") (class "Default")
      (node (ref "IC2") (pin "17") (pinfunction "A17_17") (pintype "input"))
      (node (ref "IC4") (pin "17") (pinfunction "Q2_17") (pintype "tri_state"))
    )
    (net (code "20") (name "/A11") (class "Default")
      (node (ref "IC2") (pin "16") (pinfunction "A18_16") (pintype "input"))
      (node (ref "IC4") (pin "16") (pinfunction "Q3_16") (pintype "tri_state"))
    )
    (net (code "21") (name "/A12") (class "Default")
      (node (ref "IC2") (pin "9") (pinfunction "A19_9") (pintype "input"))
      (node (ref "IC4") (pin "15") (pinfunction "Q4_15") (pintype "tri_state"))
    )
    (net (code "22") (name "/A13") (class "Default")
      (node (ref "IC2") (pin "8") (pinfunction "A8_8") (pintype "input"))
      (node (ref "IC4") (pin "14") (pinfunction "Q5_14") (pintype "tri_state"))
    )
    (net (code "23") (name "/A14") (class "Default")
      (node (ref "IC2") (pin "7") (pinfunction "A9_7") (pintype "input"))
      (node (ref "IC4") (pin "13") (pinfunction "Q6_13") (pintype "tri_state"))
    )
    (net (code "24") (name "/A15") (class "Default")
      (node (ref "IC2") (pin "6") (pinfunction "A10_6") (pintype "input"))
      (node (ref "IC4") (pin "12") (pinfunction "Q7_12") (pintype "tri_state"))
    )
    (net (code "25") (name "/A16") (class "Default")
      (node (ref "IC1") (pin "32") (pinfunction "AN8/RPB8/CTED10/RB8_32") (pintype "bidirectional"))
      (node (ref "IC2") (pin "5") (pinfunction "A11_5") (pintype "input"))
    )
    (net (code "26") (name "/A17") (class "Default")
      (node (ref "IC1") (pin "33") (pinfunction "AN9/RPB9/CTED4/RB9_33") (pintype "bidirectional"))
      (node (ref "IC2") (pin "4") (pinfunction "A12_4") (pintype "input"))
    )
    (net (code "27") (name "/A18") (class "Default")
      (node (ref "IC1") (pin "34") (pinfunction "CVREFOUT/AN10/RPB10/PMA13/CTED11/RB10_34") (pintype "bidirectional"))
      (node (ref "IC2") (pin "3") (pinfunction "A13_3") (pintype "input"))
    )
    (net (code "28") (name "/A19") (class "Default")
      (node (ref "IC1") (pin "35") (pinfunction "AN11/PMA12/RB11_35") (pintype "bidirectional"))
      (node (ref "IC2") (pin "2") (pinfunction "A14_2") (pintype "input"))
    )
    (net (code "29") (name "/A20") (class "Default")
      (node (ref "IC1") (pin "41") (pinfunction "AN12/PMA11/RB12_41") (pintype "bidirectional"))
      (node (ref "IC2") (pin "1") (pinfunction "A15_1") (pintype "input"))
    )
    (net (code "30") (name "/AGND1") (class "Default")
      (node (ref "C3") (pin "1") (pinfunction "1_1") (pintype "passive"))
      (node (ref "C9") (pin "-") (pinfunction "-_-") (pintype "passive"))
      (node (ref "J1") (pin "2") (pinfunction "2_2") (pintype "passive"))
      (node (ref "R6") (pin "1") (pinfunction "1_1") (pintype "passive"))
    )
    (net (code "31") (name "/AGND2") (class "Default")
      (node (ref "C10") (pin "-") (pinfunction "-_-") (pintype "passive"))
      (node (ref "C4") (pin "1") (pinfunction "1_1") (pintype "passive"))
      (node (ref "J2") (pin "2") (pinfunction "2_2") (pintype "passive"))
      (node (ref "R7") (pin "1") (pinfunction "1_1") (pintype "passive"))
    )
    (net (code "32") (name "/AVDD1") (class "Default")
      (node (ref "C3") (pin "2") (pinfunction "2_2") (pintype "passive"))
      (node (ref "C9") (pin "+") (pinfunction "+_+") (pintype "passive"))
      (node (ref "J1") (pin "4") (pinfunction "4_4") (pintype "passive"))
      (node (ref "L1") (pin "2") (pinfunction "2_2") (pintype "passive"))
    )
    (net (code "33") (name "/AVDD2") (class "Default")
      (node (ref "C10") (pin "+") (pinfunction "+_+") (pintype "passive"))
      (node (ref "C4") (pin "2") (pinfunction "2_2") (pintype "passive"))
      (node (ref "J2") (pin "4") (pinfunction "4_4") (pintype "passive"))
      (node (ref "L2") (pin "1") (pinfunction "1_1") (pintype "passive"))
    )
    (net (code "34") (name "/B-") (class "Default")
      (node (ref "J3") (pin "5") (pinfunction "5_5") (pintype "passive"))
      (node (ref "J4") (pin "5") (pinfunction "5_5") (pintype "passive"))
      (node (ref "L7") (pin "2") (pinfunction "2_2") (pintype "passive"))
    )
    (net (code "35") (name "/B--") (class "Default")
      (node (ref "IC12") (pin "7") (pinfunction "B_7") (pintype "bidirectional"))
      (node (ref "IC14") (pin "2") (pinfunction "2_2") (pintype "passive"))
      (node (ref "R108") (pin "2") (pinfunction "2_2") (pintype "passive"))
      (node (ref "R31") (pin "1") (pinfunction "1_1") (pintype "passive"))
      (node (ref "R32") (pin "1") (pinfunction "1_1") (pintype "passive"))
    )
    (net (code "36") (name "/BT-RTS") (class "Default")
      (node (ref "IC1") (pin "83") (pinfunction "PMD14/RD6_83") (pintype "bidirectional"))
      (node (ref "J14") (pin "7") (pinfunction "7_7") (pintype "passive"))
      (node (ref "O32") (pin "P$1") (pinfunction "TP_P$1") (pintype "passive"))
      (node (ref "T44") (pin "P$1") (pinfunction "TP_P$1") (pintype "passive"))
    )
    (net (code "37") (name "/BT-RX") (class "Default")
      (node (ref "IC1") (pin "73") (pinfunction "SOSCI/RPC13/RC13_73") (pintype "bidirectional"))
      (node (ref "J14") (pin "3") (pinfunction "3_3") (pintype "passive"))
      (node (ref "O37") (pin "P$1") (pinfunction "TP_P$1") (pintype "passive"))
      (node (ref "T40") (pin "P$1") (pinfunction "TP_P$1") (pintype "passive"))
    )
    (net (code "38") (name "/BT-TX") (class "Default")
      (node (ref "IC1") (pin "74") (pinfunction "SOSCO/RPC14/T1CK/RC14_74") (pintype "bidirectional"))
      (node (ref "J14") (pin "4") (pinfunction "4_4") (pintype "passive"))
      (node (ref "O36") (pin "P$1") (pinfunction "TP_P$1") (pintype "passive"))
      (node (ref "T41") (pin "P$1") (pinfunction "TP_P$1") (pintype "passive"))
    )
    (net (code "39") (name "/CON-LED") (class "Default")
      (node (ref "IC1") (pin "78") (pinfunction "AN26/RPD3/RD3_78") (pintype "bidirectional"))
      (node (ref "J14") (pin "6") (pinfunction "6_6") (pintype "passive"))
      (node (ref "O33") (pin "P$1") (pinfunction "TP_P$1") (pintype "passive"))
      (node (ref "T43") (pin "P$1") (pinfunction "TP_P$1") (pintype "passive"))
    )
    (net (code "40") (name "/CS-SRAM") (class "Default")
      (node (ref "IC1") (pin "38") (pinfunction "TCK/CTED2/RA1_38") (pintype "bidirectional"))
      (node (ref "IC2") (pin "12") (pinfunction "CS2_12") (pintype "input"))
      (node (ref "O17") (pin "P$1") (pinfunction "TP_P$1") (pintype "passive"))
      (node (ref "R5") (pin "2") (pinfunction "2_2") (pintype "passive"))
      (node (ref "T28") (pin "P$1") (pinfunction "TP_P$1") (pintype "passive"))
    )
    (net (code "41") (name "/CURR-SENSE") (class "Default")
      (node (ref "C66") (pin "1") (pinfunction "1_1") (pintype "passive"))
      (node (ref "IC1") (pin "14") (pinfunction "AN19/C2INC/RPG9/PMA2/RG9_14") (pintype "bidirectional"))
      (node (ref "O8") (pin "P$1") (pinfunction "TP_P$1") (pintype "passive"))
      (node (ref "R102") (pin "2") (pinfunction "2_2") (pintype "passive"))
      (node (ref "T39") (pin "P$1") (pinfunction "TP_P$1") (pintype "passive"))
    )
    (net (code "42") (name "/D+") (class "Default")
      (node (ref "IC1") (pin "57") (pinfunction "D+/RG2_57") (pintype "bidirectional"))
      (node (ref "IC15") (pin "3") (pinfunction "3_3") (pintype "passive"))
      (node (ref "J12") (pin "3_D+") (pinfunction "D+_3_D+") (pintype "bidirectional"))
    )
    (net (code "43") (name "/D-") (class "Default")
      (node (ref "IC1") (pin "56") (pinfunction "D-/RG3_56") (pintype "bidirectional"))
      (node (ref "IC15") (pin "2") (pinfunction "2_2") (pintype "passive"))
      (node (ref "J12") (pin "2_D-") (pinfunction "D-_2_D-") (pintype "bidirectional"))
    )
    (net (code "44") (name "/D0") (class "Default")
      (node (ref "IC1") (pin "93") (pinfunction "PMD0/RE0_93") (pintype "bidirectional"))
      (node (ref "IC2") (pin "29") (pinfunction "D0_29") (pintype "tri_state"))
      (node (ref "IC3") (pin "9") (pinfunction "D7_9") (pintype "input"))
      (node (ref "IC4") (pin "2") (pinfunction "D0_2") (pintype "input"))
    )
    (net (code "45") (name "/D1") (class "Default")
      (node (ref "IC1") (pin "94") (pinfunction "PMD1/RE1_94") (pintype "bidirectional"))
      (node (ref "IC2") (pin "31") (pinfunction "D1_31") (pintype "tri_state"))
      (node (ref "IC3") (pin "8") (pinfunction "D6_8") (pintype "input"))
      (node (ref "IC4") (pin "3") (pinfunction "D1_3") (pintype "input"))
    )
    (net (code "46") (name "/D2") (class "Default")
      (node (ref "IC1") (pin "98") (pinfunction "AN20/PMD2/RE2_98") (pintype "bidirectional"))
      (node (ref "IC2") (pin "33") (pinfunction "D2_33") (pintype "tri_state"))
      (node (ref "IC3") (pin "7") (pinfunction "D5_7") (pintype "input"))
      (node (ref "IC4") (pin "4") (pinfunction "D2_4") (pintype "input"))
    )
    (net (code "47") (name "/D3") (class "Default")
      (node (ref "IC1") (pin "99") (pinfunction "RPE3/PMD3/RE3_99") (pintype "bidirectional"))
      (node (ref "IC2") (pin "35") (pinfunction "D3_35") (pintype "tri_state"))
      (node (ref "IC3") (pin "6") (pinfunction "D4_6") (pintype "input"))
      (node (ref "IC4") (pin "5") (pinfunction "D3_5") (pintype "input"))
    )
    (net (code "48") (name "/D4") (class "Default")
      (node (ref "IC1") (pin "100") (pinfunction "AN21/PMD4/RE4_100") (pintype "bidirectional"))
      (node (ref "IC2") (pin "38") (pinfunction "D4_38") (pintype "tri_state"))
      (node (ref "IC3") (pin "5") (pinfunction "D3_5") (pintype "input"))
      (node (ref "IC4") (pin "6") (pinfunction "D4_6") (pintype "input"))
    )
    (net (code "49") (name "/D5") (class "Default")
      (node (ref "IC1") (pin "3") (pinfunction "AN22/RPE5/PMD5/RE5_3") (pintype "bidirectional"))
      (node (ref "IC2") (pin "40") (pinfunction "D5_40") (pintype "tri_state"))
      (node (ref "IC3") (pin "4") (pinfunction "D2_4") (pintype "input"))
      (node (ref "IC4") (pin "7") (pinfunction "D5_7") (pintype "input"))
    )
    (net (code "50") (name "/D6") (class "Default")
      (node (ref "IC1") (pin "4") (pinfunction "AN23/PMD6/RE6_4") (pintype "bidirectional"))
      (node (ref "IC2") (pin "42") (pinfunction "D6_42") (pintype "tri_state"))
      (node (ref "IC3") (pin "3") (pinfunction "D1_3") (pintype "input"))
      (node (ref "IC4") (pin "8") (pinfunction "D6_8") (pintype "input"))
    )
    (net (code "51") (name "/D7") (class "Default")
      (node (ref "IC1") (pin "5") (pinfunction "AN27/PMD7/RE7_5") (pintype "bidirectional"))
      (node (ref "IC2") (pin "44") (pinfunction "D7_44") (pintype "tri_state"))
      (node (ref "IC3") (pin "2") (pinfunction "D0_2") (pintype "input"))
      (node (ref "IC4") (pin "9") (pinfunction "D7_9") (pintype "input"))
    )
    (net (code "52") (name "/DOOR-IN-EN") (class "Default")
      (node (ref "IC1") (pin "51") (pinfunction "RPF3/USBID/RF3_51") (pintype "bidirectional"))
      (node (ref "O43") (pin "P$1") (pinfunction "TP_P$1") (pintype "passive"))
      (node (ref "Q12") (pin "2") (pinfunction "G_2") (pintype "passive"))
      (node (ref "Q13") (pin "2") (pinfunction "G_2") (pintype "passive"))
      (node (ref "R76") (pin "1") (pinfunction "1_1") (pintype "passive"))
      (node (ref "R88") (pin "1") (pinfunction "1_1") (pintype "passive"))
      (node (ref "T8") (pin "P$1") (pinfunction "TP_P$1") (pintype "passive"))
    )
    (net (code "53") (name "/DOOR1IN") (class "Default")
      (node (ref "IC1") (pin "50") (pinfunction "RPF5/PMA8/RF5_50") (pintype "bidirectional"))
      (node (ref "O21") (pin "P$1") (pinfunction "TP_P$1") (pintype "passive"))
      (node (ref "Q13") (pin "3") (pinfunction "D_3") (pintype "passive"))
      (node (ref "R74") (pin "1") (pinfunction "1_1") (pintype "passive"))
      (node (ref "T12") (pin "P$1") (pinfunction "TP_P$1") (pintype "passive"))
    )
    (net (code "54") (name "/DOOR2IN") (class "Default")
      (node (ref "IC1") (pin "77") (pinfunction "AN25/RPD2/RD2_77") (pintype "bidirectional"))
      (node (ref "O34") (pin "P$1") (pinfunction "TP_P$1") (pintype "passive"))
      (node (ref "Q12") (pin "3") (pinfunction "D_3") (pintype "passive"))
      (node (ref "R89") (pin "1") (pinfunction "1_1") (pintype "passive"))
      (node (ref "T11") (pin "P$1") (pinfunction "TP_P$1") (pintype "passive"))
    )
    (net (code "55") (name "/DOVDD1") (class "Default")
      (node (ref "C11") (pin "+") (pinfunction "+_+") (pintype "passive"))
      (node (ref "C5") (pin "1") (pinfunction "1_1") (pintype "passive"))
      (node (ref "J1") (pin "11") (pinfunction "11_11") (pintype "passive"))
      (node (ref "L3") (pin "2") (pinfunction "2_2") (pintype "passive"))
    )
    (net (code "56") (name "/DOVDD2") (class "Default")
      (node (ref "C12") (pin "+") (pinfunction "+_+") (pintype "passive"))
      (node (ref "C6") (pin "1") (pinfunction "1_1") (pintype "passive"))
      (node (ref "J2") (pin "11") (pinfunction "11_11") (pintype "passive"))
      (node (ref "L4") (pin "1") (pinfunction "1_1") (pintype "passive"))
    )
    (net (code "57") (name "/DVDD1") (class "Default")
      (node (ref "C13") (pin "+") (pinfunction "+_+") (pintype "passive"))
      (node (ref "C7") (pin "2") (pinfunction "2_2") (pintype "passive"))
      (node (ref "J1") (pin "10") (pinfunction "10_10") (pintype "passive"))
      (node (ref "L5") (pin "2") (pinfunction "2_2") (pintype "passive"))
    )
    (net (code "58") (name "/DVDD2") (class "Default")
      (node (ref "C14") (pin "+") (pinfunction "+_+") (pintype "passive"))
      (node (ref "C8") (pin "2") (pinfunction "2_2") (pintype "passive"))
      (node (ref "J2") (pin "10") (pinfunction "10_10") (pintype "passive"))
      (node (ref "L6") (pin "1") (pinfunction "1_1") (pintype "passive"))
    )
    (net (code "59") (name "/EN") (class "Default")
      (node (ref "IC1") (pin "18") (pinfunction "RPE8/RE8_18") (pintype "bidirectional"))
      (node (ref "J15") (pin "8") (pinfunction "8_8") (pintype "passive"))
      (node (ref "O10") (pin "P$1") (pinfunction "TP_P$1") (pintype "passive"))
      (node (ref "T25") (pin "P$1") (pinfunction "TP_P$1") (pintype "passive"))
    )
    (net (code "60") (name "/HREF") (class "Default")
      (node (ref "IC1") (pin "6") (pinfunction "RPC1/RC1_6") (pintype "bidirectional"))
      (node (ref "J1") (pin "9") (pinfunction "9_9") (pintype "passive"))
      (node (ref "J2") (pin "9") (pinfunction "9_9") (pintype "passive"))
      (node (ref "O2") (pin "P$1") (pinfunction "TP_P$1") (pintype "passive"))
      (node (ref "T18") (pin "P$1") (pinfunction "TP_P$1") (pintype "passive"))
    )
    (net (code "61") (name "/INFRA1PWM") (class "Default")
      (node (ref "IC1") (pin "90") (pinfunction "RPG0/PMD8/RG0_90") (pintype "bidirectional"))
      (node (ref "O27") (pin "P$1") (pinfunction "TP_P$1") (pintype "passive"))
      (node (ref "R113") (pin "2") (pinfunction "2_2") (pintype "passive"))
      (node (ref "T34") (pin "P$1") (pinfunction "TP_P$1") (pintype "passive"))
    )
    (net (code "62") (name "/INFRA2PWM") (class "Default")
      (node (ref "IC1") (pin "40") (pinfunction "RPF12/RF12_40") (pintype "bidirectional"))
      (node (ref "O19") (pin "P$1") (pinfunction "TP_P$1") (pintype "passive"))
      (node (ref "R119") (pin "2") (pinfunction "2_2") (pintype "passive"))
      (node (ref "T35") (pin "P$1") (pinfunction "TP_P$1") (pintype "passive"))
    )
    (net (code "63") (name "/IRQ") (class "Default")
      (node (ref "IC1") (pin "19") (pinfunction "RPE9/RE9_19") (pintype "bidirectional"))
      (node (ref "J15") (pin "3") (pinfunction "3_3") (pintype "passive"))
      (node (ref "O11") (pin "P$1") (pinfunction "TP_P$1") (pintype "passive"))
      (node (ref "T24") (pin "P$1") (pinfunction "TP_P$1") (pintype "passive"))
    )
    (net (code "64") (name "/L1CTL") (class "Default")
      (node (ref "C79") (pin "1") (pinfunction "1_1") (pintype "passive"))
      (node (ref "J5") (pin "3") (pinfunction "3_3") (pintype "bidirectional"))
      (node (ref "Q6") (pin "4") (pinfunction "D_4") (pintype "passive"))
    )
    (net (code "65") (name "/L1PWR") (class "Default")
      (node (ref "C80") (pin "1") (pinfunction "1_1") (pintype "passive"))
      (node (ref "J5") (pin "2") (pinfunction "2_2") (pintype "bidirectional"))
      (node (ref "Q6") (pin "6") (pinfunction "D_6") (pintype "passive"))
    )
    (net (code "66") (name "/L2CTL") (class "Default")
      (node (ref "C78") (pin "1") (pinfunction "1_1") (pintype "passive"))
      (node (ref "J6") (pin "3") (pinfunction "3_3") (pintype "bidirectional"))
      (node (ref "Q8") (pin "6") (pinfunction "D_6") (pintype "passive"))
    )
    (net (code "67") (name "/L2PWR") (class "Default")
      (node (ref "C77") (pin "1") (pinfunction "1_1") (pintype "passive"))
      (node (ref "J6") (pin "2") (pinfunction "2_2") (pintype "bidirectional"))
      (node (ref "Q8") (pin "4") (pinfunction "D_4") (pintype "passive"))
    )
    (net (code "68") (name "/LAN-CTL") (class "Default")
      (node (ref "IC1") (pin "84") (pinfunction "PMD15/RD7_84") (pintype "bidirectional"))
      (node (ref "IC12") (pin "2") (pinfunction "/RE_2") (pintype "input"))
      (node (ref "IC12") (pin "3") (pinfunction "DE_3") (pintype "input"))
      (node (ref "O31") (pin "P$1") (pinfunction "TP_P$1") (pintype "passive"))
      (node (ref "R71") (pin "1") (pinfunction "1_1") (pintype "passive"))
      (node (ref "T15") (pin "P$1") (pinfunction "TP_P$1") (pintype "passive"))
    )
    (net (code "69") (name "/LAN-RX") (class "Default")
      (node (ref "IC1") (pin "88") (pinfunction "RPF1/PMD10/RF1_88") (pintype "bidirectional"))
      (node (ref "IC12") (pin "1") (pinfunction "R_1") (pintype "output"))
      (node (ref "O29") (pin "P$1") (pinfunction "TP_P$1") (pintype "passive"))
      (node (ref "R72") (pin "2") (pinfunction "2_2") (pintype "passive"))
      (node (ref "T13") (pin "P$1") (pinfunction "TP_P$1") (pintype "passive"))
    )
    (net (code "70") (name "/LAN-TX") (class "Default")
      (node (ref "IC1") (pin "87") (pinfunction "RPF0/PMD11/RF0_87") (pintype "bidirectional"))
      (node (ref "IC12") (pin "4") (pinfunction "D_4") (pintype "input"))
      (node (ref "O30") (pin "P$1") (pinfunction "TP_P$1") (pintype "passive"))
      (node (ref "R73") (pin "1") (pinfunction "1_1") (pintype "passive"))
      (node (ref "T14") (pin "P$1") (pinfunction "TP_P$1") (pintype "passive"))
    )
    (net (code "71") (name "/LED-PIC") (class "Default")
      (node (ref "IC1") (pin "1") (pinfunction "RG15_1") (pintype "bidirectional"))
      (node (ref "O1") (pin "P$1") (pinfunction "TP_P$1") (pintype "passive"))
      (node (ref "R29") (pin "1") (pinfunction "1_1") (pintype "passive"))
      (node (ref "T36") (pin "P$1") (pinfunction "TP_P$1") (pintype "passive"))
      (node (ref "TP4") (pin "P$1") (pinfunction "TP_P$1") (pintype "passive"))
    )
    (net (code "72") (name "/LEH-SRAM") (class "Default")
      (node (ref "IC1") (pin "43") (pinfunction "AN14/RPB14/PMA1/CTED5/RB14_43") (pintype "bidirectional"))
      (node (ref "IC4") (pin "11") (pinfunction "LE_11") (pintype "input"))
      (node (ref "R2") (pin "2") (pinfunction "2_2") (pintype "passive"))
    )
    (net (code "73") (name "/LEL-SRAM") (class "Default")
      (node (ref "IC1") (pin "44") (pinfunction "AN15/RPB15/PMA0/CTED6//RB15_44") (pintype "bidirectional"))
      (node (ref "IC3") (pin "11") (pinfunction "LE_11") (pintype "input"))
      (node (ref "R1") (pin "2") (pinfunction "2_2") (pintype "passive"))
    )
    (net (code "74") (name "/LOCK-IN-EN") (class "Default")
      (node (ref "IC1") (pin "60") (pinfunction "TDI/CTED9/RA4_60") (pintype "bidirectional"))
      (node (ref "O40") (pin "P$1") (pinfunction "TP_P$1") (pintype "passive"))
      (node (ref "Q10") (pin "2") (pinfunction "G_2") (pintype "passive"))
      (node (ref "Q11") (pin "2") (pinfunction "G_2") (pintype "passive"))
      (node (ref "R67") (pin "1") (pinfunction "1_1") (pintype "passive"))
      (node (ref "R83") (pin "1") (pinfunction "1_1") (pintype "passive"))
      (node (ref "T6") (pin "P$1") (pinfunction "TP_P$1") (pintype "passive"))
    )
    (net (code "75") (name "/LOCK1CTL") (class "Default")
      (node (ref "IC1") (pin "61") (pinfunction "TDO/RA5_61") (pintype "bidirectional"))
      (node (ref "O39") (pin "P$1") (pinfunction "TP_P$1") (pintype "passive"))
      (node (ref "Q7") (pin "5") (pinfunction "G_5") (pintype "passive"))
      (node (ref "R54") (pin "1") (pinfunction "1_1") (pintype "passive"))
      (node (ref "T1") (pin "P$1") (pinfunction "TP_P$1") (pintype "passive"))
    )
    (net (code "76") (name "/LOCK1IN") (class "Default")
      (node (ref "IC1") (pin "49") (pinfunction "RPF4/PMA9/RF4_49") (pintype "bidirectional"))
      (node (ref "O20") (pin "P$1") (pinfunction "TP_P$1") (pintype "passive"))
      (node (ref "Q11") (pin "3") (pinfunction "D_3") (pintype "passive"))
      (node (ref "R66") (pin "1") (pinfunction "1_1") (pintype "passive"))
      (node (ref "T10") (pin "P$1") (pinfunction "TP_P$1") (pintype "passive"))
    )
    (net (code "77") (name "/LOCK2CTL") (class "Default")
      (node (ref "IC1") (pin "91") (pinfunction "TRCLK/RA6_91") (pintype "bidirectional"))
      (node (ref "O26") (pin "P$1") (pinfunction "TP_P$1") (pintype "passive"))
      (node (ref "Q9") (pin "2") (pinfunction "G_2") (pintype "passive"))
      (node (ref "R58") (pin "1") (pinfunction "1_1") (pintype "passive"))
      (node (ref "T2") (pin "P$1") (pinfunction "TP_P$1") (pintype "passive"))
    )
    (net (code "78") (name "/LOCK2IN") (class "Default")
      (node (ref "IC1") (pin "89") (pinfunction "RPG1/PMD9/RG1_89") (pintype "bidirectional"))
      (node (ref "O28") (pin "P$1") (pinfunction "TP_P$1") (pintype "passive"))
      (node (ref "Q10") (pin "3") (pinfunction "D_3") (pintype "passive"))
      (node (ref "R81") (pin "1") (pinfunction "1_1") (pintype "passive"))
      (node (ref "T9") (pin "P$1") (pinfunction "TP_P$1") (pintype "passive"))
    )
    (net (code "79") (name "/LOCK12PWR") (class "Default")
      (node (ref "IC1") (pin "92") (pinfunction "TRD3/CTED8/RA7_92") (pintype "bidirectional"))
      (node (ref "O25") (pin "P$1") (pinfunction "TP_P$1") (pintype "passive"))
      (node (ref "Q7") (pin "2") (pinfunction "G_2") (pintype "passive"))
      (node (ref "Q9") (pin "5") (pinfunction "G_5") (pintype "passive"))
      (node (ref "R52") (pin "1") (pinfunction "1_1") (pintype "passive"))
      (node (ref "R60") (pin "1") (pinfunction "1_1") (pintype "passive"))
      (node (ref "T4") (pin "P$1") (pinfunction "TP_P$1") (pintype "passive"))
    )
    (net (code "80") (name "/NC-A15-2") (class "Default")
      (node (ref "IC1") (pin "42") (pinfunction "AN13/RB13_42") (pintype "bidirectional"))
    )
    (net (code "81") (name "/OE-SRAM") (class "Default")
      (node (ref "IC1") (pin "82") (pinfunction "RPD5/PMRD/RD5_82") (pintype "bidirectional"))
      (node (ref "IC2") (pin "28") (pinfunction "~{OE}_28") (pintype "input"))
      (node (ref "R3") (pin "1") (pinfunction "1_1") (pintype "passive"))
    )
    (net (code "82") (name "/PCLK") (class "Default")
      (node (ref "IC1") (pin "76") (pinfunction "AN24/RPD1/RD1_76") (pintype "bidirectional"))
      (node (ref "J1") (pin "17") (pinfunction "17_17") (pintype "passive"))
      (node (ref "J2") (pin "17") (pinfunction "17_17") (pintype "passive"))
      (node (ref "O35") (pin "P$1") (pinfunction "TP_P$1") (pintype "passive"))
      (node (ref "T17") (pin "P$1") (pinfunction "TP_P$1") (pintype "passive"))
    )
    (net (code "83") (name "/PGC") (class "Default")
      (node (ref "IC1") (pin "24") (pinfunction "PGEC1/AN1/RPB1/CTED12/RB1_24") (pintype "bidirectional"))
      (node (ref "J17") (pin "5") (pinfunction "5_5") (pintype "passive"))
      (node (ref "R131") (pin "1") (pinfunction "1_1") (pintype "passive"))
    )
    (net (code "84") (name "/PGD") (class "Default")
      (node (ref "IC1") (pin "25") (pinfunction "PGED1/AN0/RPB0/RB0_25") (pintype "bidirectional"))
      (node (ref "J17") (pin "4") (pinfunction "4_4") (pintype "passive"))
      (node (ref "R130") (pin "2") (pinfunction "2_2") (pintype "passive"))
    )
    (net (code "85") (name "/POWER-GOOD") (class "Default")
      (node (ref "IC6") (pin "4") (pinfunction "OUT_4") (pintype "output"))
      (node (ref "R130") (pin "1") (pinfunction "1_1") (pintype "passive"))
      (node (ref "T45") (pin "P$1") (pinfunction "TP_P$1") (pintype "passive"))
      (node (ref "TP2") (pin "P$1") (pinfunction "TP_P$1") (pintype "passive"))
    )
    (net (code "86") (name "/PWDN-CAM1") (class "Default")
      (node (ref "IC1") (pin "97") (pinfunction "TRD0/RG13_97") (pintype "bidirectional"))
      (node (ref "J1") (pin "8") (pinfunction "8_8") (pintype "passive"))
      (node (ref "O22") (pin "P$1") (pinfunction "TP_P$1") (pintype "passive"))
      (node (ref "R12") (pin "1") (pinfunction "1_1") (pintype "passive"))
      (node (ref "T20") (pin "P$1") (pinfunction "TP_P$1") (pintype "passive"))
    )
    (net (code "87") (name "/PWDN-CAM2") (class "Default")
      (node (ref "IC1") (pin "39") (pinfunction "RPF13/RF13_39") (pintype "bidirectional"))
      (node (ref "J2") (pin "8") (pinfunction "8_8") (pintype "passive"))
      (node (ref "O18") (pin "P$1") (pinfunction "TP_P$1") (pintype "passive"))
      (node (ref "R16") (pin "1") (pinfunction "1_1") (pintype "passive"))
      (node (ref "T21") (pin "P$1") (pinfunction "TP_P$1") (pintype "passive"))
    )
    (net (code "88") (name "/REF-EN") (class "Default")
      (node (ref "IC1") (pin "28") (pinfunction "VREF-/CVREF-/PMA7/RA9_28") (pintype "bidirectional"))
      (node (ref "R93") (pin "1") (pinfunction "1_1") (pintype "passive"))
    )
    (net (code "89") (name "/REF2,5V") (class "Default")
      (node (ref "C57") (pin "1") (pinfunction "1_1") (pintype "passive"))
      (node (ref "IC1") (pin "29") (pinfunction "VREF+/CVREF+/PMA6/RA10_29") (pintype "bidirectional"))
      (node (ref "IC13") (pin "2") (pinfunction "VOUT_2") (pintype "bidirectional"))
    )
    (net (code "90") (name "/RESET-CAM1") (class "Default")
      (node (ref "C76") (pin "1") (pinfunction "1_1") (pintype "passive"))
      (node (ref "J1") (pin "6") (pinfunction "6_6") (pintype "passive"))
      (node (ref "R11") (pin "1") (pinfunction "1_1") (pintype "passive"))
    )
    (net (code "91") (name "/RESET-CAM2") (class "Default")
      (node (ref "C75") (pin "1") (pinfunction "1_1") (pintype "passive"))
      (node (ref "J2") (pin "6") (pinfunction "6_6") (pintype "passive"))
      (node (ref "R15") (pin "1") (pinfunction "1_1") (pintype "passive"))
    )
    (net (code "92") (name "/SCL1-EEPROM") (class "Default")
      (node (ref "IC1") (pin "66") (pinfunction "SCL1/RPA14/RA14_66") (pintype "bidirectional"))
      (node (ref "IC11") (pin "6") (pinfunction "SCL_6") (pintype "input"))
      (node (ref "IC7") (pin "6") (pinfunction "SCL_6") (pintype "input"))
      (node (ref "R26") (pin "2") (pinfunction "2_2") (pintype "passive"))
    )
    (net (code "93") (name "/SCLK2-SPI") (class "Default")
      (node (ref "IC1") (pin "10") (pinfunction "AN16/C1IND/RPG6/SCK2/PMA5/RG6_10") (pintype "bidirectional"))
      (node (ref "IC9") (pin "6") (pinfunction "C_6") (pintype "input"))
      (node (ref "J11") (pin "5") (pinfunction "CLK_5") (pintype "passive"))
      (node (ref "J15") (pin "12") (pinfunction "12_12") (pintype "passive"))
    )
    (net (code "94") (name "/SD-CS") (class "Default")
      (node (ref "IC1") (pin "9") (pinfunction "RPC4/CTED7/RC4_9") (pintype "bidirectional"))
      (node (ref "J11") (pin "2") (pinfunction "CS/DAT3_2") (pintype "passive"))
      (node (ref "O5") (pin "P$1") (pinfunction "TP_P$1") (pintype "passive"))
      (node (ref "R127") (pin "2") (pinfunction "2_2") (pintype "passive"))
      (node (ref "T29") (pin "P$1") (pinfunction "TP_P$1") (pintype "passive"))
    )
    (net (code "95") (name "/SDA1-EEPROM") (class "Default")
      (node (ref "IC1") (pin "67") (pinfunction "SDA1/RPA15/RA15_67") (pintype "bidirectional"))
      (node (ref "IC11") (pin "5") (pinfunction "SDA_5") (pintype "bidirectional"))
      (node (ref "IC7") (pin "5") (pinfunction "SDA_5") (pintype "bidirectional"))
      (node (ref "R27") (pin "2") (pinfunction "2_2") (pintype "passive"))
    )
    (net (code "96") (name "/SDI2-MISO") (class "Default")
      (node (ref "IC1") (pin "22") (pinfunction "PGED3/AN3/C2INA/RPB3/RB3_22") (pintype "bidirectional"))
      (node (ref "IC9") (pin "2") (pinfunction "Q_2") (pintype "bidirectional"))
      (node (ref "J11") (pin "7") (pinfunction "DO/DAT0_7") (pintype "passive"))
      (node (ref "J15") (pin "11") (pinfunction "11_11") (pintype "passive"))
      (node (ref "O13") (pin "P$1") (pinfunction "TP_P$1") (pintype "passive"))
      (node (ref "T22") (pin "P$1") (pinfunction "TP_P$1") (pintype "passive"))
    )
    (net (code "97") (name "/SDO2-MOSI") (class "Default")
      (node (ref "IC1") (pin "20") (pinfunction "AN5/C1INA/RPB5/RB5_20") (pintype "bidirectional"))
      (node (ref "IC9") (pin "5") (pinfunction "D_5") (pintype "input"))
      (node (ref "J11") (pin "3") (pinfunction "DI/CMD_3") (pintype "passive"))
      (node (ref "J15") (pin "14") (pinfunction "14_14") (pintype "passive"))
      (node (ref "O12") (pin "P$1") (pinfunction "TP_P$1") (pintype "passive"))
      (node (ref "T23") (pin "P$1") (pinfunction "TP_P$1") (pintype "passive"))
    )
    (net (code "98") (name "/SIO-C-CAM") (class "Default")
      (node (ref "IC1") (pin "58") (pinfunction "SCL2/RA2_58") (pintype "bidirectional"))
      (node (ref "J1") (pin "5") (pinfunction "5_5") (pintype "passive"))
      (node (ref "J2") (pin "5") (pinfunction "5_5") (pintype "passive"))
      (node (ref "R13") (pin "1") (pinfunction "1_1") (pintype "passive"))
    )
    (net (code "99") (name "/SIO-D-CAM") (class "Default")
      (node (ref "IC1") (pin "59") (pinfunction "SDA2/RA3_59") (pintype "bidirectional"))
      (node (ref "J1") (pin "3") (pinfunction "3_3") (pintype "passive"))
      (node (ref "J2") (pin "3") (pinfunction "3_3") (pintype "passive"))
      (node (ref "R14") (pin "1") (pinfunction "1_1") (pintype "passive"))
    )
    (net (code "100") (name "/VBAT-LAN") (class "Default")
      (node (ref "D3") (pin "C") (pinfunction "C_C") (pintype "passive"))
      (node (ref "J3") (pin "1") (pinfunction "1_1") (pintype "passive"))
      (node (ref "J3") (pin "3") (pinfunction "3_3") (pintype "passive"))
      (node (ref "J4") (pin "1") (pinfunction "1_1") (pintype "passive"))
      (node (ref "J4") (pin "3") (pinfunction "3_3") (pintype "passive"))
      (node (ref "L11") (pin "2") (pinfunction "2_2") (pintype "passive"))
    )
    (net (code "101") (name "/VBAT-LAN-F") (class "Default")
      (node (ref "C33") (pin "1") (pinfunction "1_1") (pintype "passive"))
      (node (ref "C34") (pin "1") (pinfunction "1_1") (pintype "passive"))
      (node (ref "D6") (pin "K") (pinfunction "K_K") (pintype "passive"))
      (node (ref "L11") (pin "1") (pinfunction "1_1") (pintype "passive"))
      (node (ref "Q5") (pin "2") (pinfunction "S_2") (pintype "passive"))
      (node (ref "Q5") (pin "5") (pinfunction "S_5") (pintype "passive"))
      (node (ref "R132") (pin "1") (pinfunction "1_1") (pintype "passive"))
      (node (ref "R36") (pin "2") (pinfunction "2_2") (pintype "passive"))
      (node (ref "R38") (pin "2") (pinfunction "2_2") (pintype "passive"))
      (node (ref "R42") (pin "1") (pinfunction "1_1") (pintype "passive"))
      (node (ref "R45") (pin "1") (pinfunction "1_1") (pintype "passive"))
      (node (ref "R94") (pin "1") (pinfunction "1_1") (pintype "passive"))
    )
    (net (code "102") (name "/VBAT-ON") (class "Default")
      (node (ref "IC1") (pin "52") (pinfunction "RPF2/RF2_52") (pintype "bidirectional"))
      (node (ref "O42") (pin "P$1") (pinfunction "TP_P$1") (pintype "passive"))
      (node (ref "Q4") (pin "2") (pinfunction "G_2") (pintype "passive"))
      (node (ref "R132") (pin "2") (pinfunction "2_2") (pintype "passive"))
      (node (ref "R41") (pin "1") (pinfunction "1_1") (pintype "passive"))
      (node (ref "T5") (pin "P$1") (pinfunction "TP_P$1") (pintype "passive"))
    )
    (net (code "103") (name "/VBAT-SENSE") (class "Default")
      (node (ref "C64") (pin "1") (pinfunction "1_1") (pintype "passive"))
      (node (ref "IC1") (pin "26") (pinfunction "PGEC2/AN6/RPB6/RB6_26") (pintype "bidirectional"))
      (node (ref "O15") (pin "P$1") (pinfunction "TP_P$1") (pintype "passive"))
      (node (ref "R100") (pin "1") (pinfunction "1_1") (pintype "passive"))
      (node (ref "T37") (pin "P$1") (pinfunction "TP_P$1") (pintype "passive"))
    )
    (net (code "104") (name "/VBATLAN-SENSE") (class "Default")
      (node (ref "C36") (pin "1") (pinfunction "1_1") (pintype "passive"))
      (node (ref "IC1") (pin "27") (pinfunction "PGED2/AN7/RPB7/CTED3/RB7_27") (pintype "bidirectional"))
      (node (ref "O16") (pin "P$1") (pinfunction "TP_P$1") (pintype "passive"))
      (node (ref "R101") (pin "1") (pinfunction "1_1") (pintype "passive"))
      (node (ref "T38") (pin "P$1") (pinfunction "TP_P$1") (pintype "passive"))
    )
    (net (code "105") (name "/VBUS") (class "Default")
      (node (ref "IC1") (pin "54") (pinfunction "VBUS_54") (pintype "input"))
      (node (ref "R128") (pin "2") (pinfunction "2_2") (pintype "passive"))
    )
    (net (code "106") (name "/VPS-ON") (class "Default")
      (node (ref "IC1") (pin "53") (pinfunction "RPF8/RF8_53") (pintype "bidirectional"))
      (node (ref "O41") (pin "P$1") (pinfunction "TP_P$1") (pintype "passive"))
      (node (ref "Q4") (pin "5") (pinfunction "G_5") (pintype "passive"))
      (node (ref "R44") (pin "1") (pinfunction "1_1") (pintype "passive"))
      (node (ref "T7") (pin "P$1") (pinfunction "TP_P$1") (pintype "passive"))
    )
    (net (code "107") (name "/VPS-PWR") (class "Default")
      (node (ref "D4") (pin "C") (pinfunction "C_C") (pintype "passive"))
      (node (ref "J3") (pin "6") (pinfunction "6_6") (pintype "passive"))
      (node (ref "J4") (pin "6") (pinfunction "6_6") (pintype "passive"))
      (node (ref "L10") (pin "2") (pinfunction "2_2") (pintype "passive"))
    )
    (net (code "108") (name "/VPS-PWR-F") (class "Default")
      (node (ref "L10") (pin "1") (pinfunction "1_1") (pintype "passive"))
      (node (ref "Q5") (pin "4") (pinfunction "D_4") (pintype "passive"))
      (node (ref "R23") (pin "2") (pinfunction "2_2") (pintype "passive"))
    )
    (net (code "109") (name "/VPS-SENSE") (class "Default")
      (node (ref "C65") (pin "1") (pinfunction "1_1") (pintype "passive"))
      (node (ref "IC1") (pin "12") (pinfunction "AN18/C2IND/RPG8/PMA3/RG8_12") (pintype "bidirectional"))
      (node (ref "O7") (pin "P$1") (pinfunction "TP_P$1") (pintype "passive"))
      (node (ref "R48") (pin "2") (pinfunction "2_2") (pintype "passive"))
      (node (ref "R49") (pin "1") (pinfunction "1_1") (pintype "passive"))
      (node (ref "T3") (pin "P$1") (pinfunction "TP_P$1") (pintype "passive"))
    )
    (net (code "110") (name "/VSYNC") (class "Default")
      (node (ref "IC1") (pin "8") (pinfunction "RPC3/RC3_8") (pintype "bidirectional"))
      (node (ref "J1") (pin "7") (pinfunction "7_7") (pintype "passive"))
      (node (ref "J2") (pin "7") (pinfunction "7_7") (pintype "passive"))
      (node (ref "O4") (pin "P$1") (pinfunction "TP_P$1") (pintype "passive"))
      (node (ref "T19") (pin "P$1") (pinfunction "TP_P$1") (pintype "passive"))
    )
    (net (code "111") (name "/WAKE-SW") (class "Default")
      (node (ref "IC1") (pin "72") (pinfunction "RPD0/INT0/RD0_72") (pintype "bidirectional"))
      (node (ref "J14") (pin "5") (pinfunction "5_5") (pintype "passive"))
      (node (ref "O38") (pin "P$1") (pinfunction "TP_P$1") (pintype "passive"))
      (node (ref "T42") (pin "P$1") (pinfunction "TP_P$1") (pintype "passive"))
    )
    (net (code "112") (name "/WE-SRAM") (class "Default")
      (node (ref "IC1") (pin "81") (pinfunction "RPD4/PMWR/RD4_81") (pintype "bidirectional"))
      (node (ref "IC2") (pin "11") (pinfunction "~{WE}_11") (pintype "input"))
      (node (ref "R4") (pin "1") (pinfunction "1_1") (pintype "passive"))
    )
    (net (code "113") (name "/XCLK1") (class "Default")
      (node (ref "IC1") (pin "7") (pinfunction "RPC2/RC2_7") (pintype "bidirectional"))
      (node (ref "J1") (pin "13") (pinfunction "13_13") (pintype "passive"))
      (node (ref "J2") (pin "13") (pinfunction "13_13") (pintype "passive"))
      (node (ref "O3") (pin "P$1") (pinfunction "TP_P$1") (pintype "passive"))
      (node (ref "T16") (pin "P$1") (pinfunction "TP_P$1") (pintype "passive"))
    )
    (net (code "114") (name "/Y2") (class "Default")
      (node (ref "IC1") (pin "68") (pinfunction "RPD8/RTCC/RD8_68") (pintype "bidirectional"))
      (node (ref "J1") (pin "19") (pinfunction "19_19") (pintype "passive"))
      (node (ref "J2") (pin "19") (pinfunction "19_19") (pintype "passive"))
    )
    (net (code "115") (name "/Y3") (class "Default")
      (node (ref "IC1") (pin "69") (pinfunction "RPD9/RD9_69") (pintype "bidirectional"))
      (node (ref "J1") (pin "21") (pinfunction "21_21") (pintype "passive"))
      (node (ref "J2") (pin "21") (pinfunction "21_21") (pintype "passive"))
    )
    (net (code "116") (name "/Y4") (class "Default")
      (node (ref "IC1") (pin "70") (pinfunction "RPD10/SCK1/PMCS2/RD10_70") (pintype "bidirectional"))
      (node (ref "J1") (pin "22") (pinfunction "22_22") (pintype "passive"))
      (node (ref "J2") (pin "22") (pinfunction "22_22") (pintype "passive"))
    )
    (net (code "117") (name "/Y5") (class "Default")
      (node (ref "IC1") (pin "71") (pinfunction "RPD11/PMCS1/RD11_71") (pintype "bidirectional"))
      (node (ref "J1") (pin "20") (pinfunction "20_20") (pintype "passive"))
      (node (ref "J2") (pin "20") (pinfunction "20_20") (pintype "passive"))
    )
    (net (code "118") (name "/Y6") (class "Default")
      (node (ref "IC1") (pin "79") (pinfunction "RPD12/PMD12/RD12_79") (pintype "bidirectional"))
      (node (ref "J1") (pin "18") (pinfunction "18_18") (pintype "passive"))
      (node (ref "J2") (pin "18") (pinfunction "18_18") (pintype "passive"))
    )
    (net (code "119") (name "/Y7") (class "Default")
      (node (ref "IC1") (pin "80") (pinfunction "PMD13/RD13_80") (pintype "bidirectional"))
      (node (ref "J1") (pin "16") (pinfunction "16_16") (pintype "passive"))
      (node (ref "J2") (pin "16") (pinfunction "16_16") (pintype "passive"))
    )
    (net (code "120") (name "/Y8") (class "Default")
      (node (ref "IC1") (pin "47") (pinfunction "RPD14/RD14_47") (pintype "bidirectional"))
      (node (ref "J1") (pin "14") (pinfunction "14_14") (pintype "passive"))
      (node (ref "J2") (pin "14") (pinfunction "14_14") (pintype "passive"))
    )
    (net (code "121") (name "/Y9") (class "Default")
      (node (ref "IC1") (pin "48") (pinfunction "RPD15/RD15_48") (pintype "bidirectional"))
      (node (ref "J1") (pin "12") (pinfunction "12_12") (pintype "passive"))
      (node (ref "J2") (pin "12") (pinfunction "12_12") (pintype "passive"))
    )
    (net (code "122") (name "/{slash}3.3V1PWRON") (class "Default")
      (node (ref "IC1") (pin "21") (pinfunction "AN4/C1INB/USBOEN/RB4_21") (pintype "bidirectional"))
      (node (ref "O44") (pin "P$1") (pinfunction "TP_P$1") (pintype "passive"))
      (node (ref "R24") (pin "2") (pinfunction "2_2") (pintype "passive"))
      (node (ref "T32") (pin "P$1") (pinfunction "TP_P$1") (pintype "passive"))
    )
    (net (code "123") (name "/{slash}3.3V2PWRON") (class "Default")
      (node (ref "IC1") (pin "96") (pinfunction "TRD1/RG12_96") (pintype "bidirectional"))
      (node (ref "O23") (pin "P$1") (pinfunction "TP_P$1") (pintype "passive"))
      (node (ref "R75") (pin "2") (pinfunction "2_2") (pintype "passive"))
      (node (ref "T33") (pin "P$1") (pinfunction "TP_P$1") (pintype "passive"))
    )
    (net (code "124") (name "/{slash}CAM-PWRON") (class "Default")
      (node (ref "IC1") (pin "95") (pinfunction "TRD2/RG14_95") (pintype "bidirectional"))
      (node (ref "O24") (pin "P$1") (pinfunction "TP_P$1") (pintype "passive"))
      (node (ref "R10") (pin "1") (pinfunction "1_1") (pintype "passive"))
      (node (ref "T30") (pin "P$1") (pinfunction "TP_P$1") (pintype "passive"))
    )
    (net (code "125") (name "/{slash}FMEM1-CS") (class "Default")
      (node (ref "IC1") (pin "11") (pinfunction "AN17/C1INC/RPG7/PMA4/RG7_11") (pintype "bidirectional"))
      (node (ref "IC9") (pin "1") (pinfunction "/S_1") (pintype "input"))
      (node (ref "O6") (pin "P$1") (pinfunction "TP_P$1") (pintype "passive"))
      (node (ref "R25") (pin "1") (pinfunction "1_1") (pintype "passive"))
      (node (ref "T27") (pin "P$1") (pinfunction "TP_P$1") (pintype "passive"))
    )
    (net (code "126") (name "/{slash}MCLR") (class "Default")
      (node (ref "IC1") (pin "13") (pinfunction "~{MCLR}_13") (pintype "input"))
      (node (ref "J17") (pin "1") (pinfunction "1_1") (pintype "passive"))
      (node (ref "R90") (pin "2") (pinfunction "2_2") (pintype "passive"))
    )
    (net (code "127") (name "/{slash}NCS") (class "Default")
      (node (ref "IC1") (pin "23") (pinfunction "PGEC3/AN2/C2INB/RPB2/CTED13/RB2_23") (pintype "bidirectional"))
      (node (ref "J15") (pin "13") (pinfunction "13_13") (pintype "passive"))
      (node (ref "O14") (pin "P$1") (pinfunction "TP_P$1") (pintype "passive"))
      (node (ref "T26") (pin "P$1") (pinfunction "TP_P$1") (pintype "passive"))
    )
    (net (code "128") (name "/{slash}PRESENT") (class "Default")
      (node (ref "J11") (pin "G2") (pinfunction "G2_G2") (pintype "passive"))
      (node (ref "R131") (pin "2") (pinfunction "2_2") (pintype "passive"))
      (node (ref "T46") (pin "P$1") (pinfunction "TP_P$1") (pintype "passive"))
    )
    (net (code "129") (name "/{slash}VPS-PWRON") (class "Default")
      (node (ref "IC1") (pin "17") (pinfunction "TMS/CTED1/RA0_17") (pintype "bidirectional"))
      (node (ref "O9") (pin "P$1") (pinfunction "TP_P$1") (pintype "passive"))
      (node (ref "R107") (pin "2") (pinfunction "2_2") (pintype "passive"))
      (node (ref "T31") (pin "P$1") (pinfunction "TP_P$1") (pintype "passive"))
    )
    (net (code "130") (name "DGND") (class "Default")
      (node (ref "C1") (pin "2") (pinfunction "2_2") (pintype "passive"))
      (node (ref "C11") (pin "-") (pinfunction "-_-") (pintype "passive"))
      (node (ref "C12") (pin "-") (pinfunction "-_-") (pintype "passive"))
      (node (ref "C13") (pin "-") (pinfunction "-_-") (pintype "passive"))
      (node (ref "C14") (pin "-") (pinfunction "-_-") (pintype "passive"))
      (node (ref "C15") (pin "2") (pinfunction "2_2") (pintype "passive"))
      (node (ref "C16") (pin "-") (pinfunction "-_-") (pintype "passive"))
      (node (ref "C17") (pin "-") (pinfunction "-_-") (pintype "passive"))
      (node (ref "C18") (pin "2") (pinfunction "2_2") (pintype "passive"))
      (node (ref "C19") (pin "2") (pinfunction "2_2") (pintype "passive"))
      (node (ref "C2") (pin "2") (pinfunction "2_2") (pintype "passive"))
      (node (ref "C20") (pin "-") (pinfunction "-_-") (pintype "passive"))
      (node (ref "C22") (pin "2") (pinfunction "2_2") (pintype "passive"))
      (node (ref "C23") (pin "2") (pinfunction "2_2") (pintype "passive"))
      (node (ref "C24") (pin "1") (pinfunction "1_1") (pintype "passive"))
      (node (ref "C27") (pin "2") (pinfunction "2_2") (pintype "passive"))
      (node (ref "C28") (pin "2") (pinfunction "2_2") (pintype "passive"))
      (node (ref "C29") (pin "2") (pinfunction "2_2") (pintype "passive"))
      (node (ref "C30") (pin "2") (pinfunction "2_2") (pintype "passive"))
      (node (ref "C31") (pin "-") (pinfunction "-_-") (pintype "passive"))
      (node (ref "C32") (pin "2") (pinfunction "2_2") (pintype "passive"))
      (node (ref "C35") (pin "2") (pinfunction "2_2") (pintype "passive"))
      (node (ref "C36") (pin "2") (pinfunction "2_2") (pintype "passive"))
      (node (ref "C37") (pin "2") (pinfunction "2_2") (pintype "passive"))
      (node (ref "C38") (pin "2") (pinfunction "2_2") (pintype "passive"))
      (node (ref "C39") (pin "2") (pinfunction "2_2") (pintype "passive"))
      (node (ref "C40") (pin "2") (pinfunction "2_2") (pintype "passive"))
      (node (ref "C41") (pin "2") (pinfunction "2_2") (pintype "passive"))
      (node (ref "C46") (pin "2") (pinfunction "2_2") (pintype "passive"))
      (node (ref "C47") (pin "2") (pinfunction "2_2") (pintype "passive"))
      (node (ref "C48") (pin "2") (pinfunction "2_2") (pintype "passive"))
      (node (ref "C49") (pin "2") (pinfunction "2_2") (pintype "passive"))
      (node (ref "C5") (pin "2") (pinfunction "2_2") (pintype "passive"))
      (node (ref "C50") (pin "2") (pinfunction "2_2") (pintype "passive"))
      (node (ref "C51") (pin "2") (pinfunction "2_2") (pintype "passive"))
      (node (ref "C52") (pin "2") (pinfunction "2_2") (pintype "passive"))
      (node (ref "C53") (pin "2") (pinfunction "2_2") (pintype "passive"))
      (node (ref "C54") (pin "-") (pinfunction "-_-") (pintype "passive"))
      (node (ref "C55") (pin "2") (pinfunction "2_2") (pintype "passive"))
      (node (ref "C56") (pin "-") (pinfunction "-_-") (pintype "passive"))
      (node (ref "C57") (pin "2") (pinfunction "2_2") (pintype "passive"))
      (node (ref "C58") (pin "2") (pinfunction "2_2") (pintype "passive"))
      (node (ref "C59") (pin "2") (pinfunction "2_2") (pintype "passive"))
      (node (ref "C6") (pin "2") (pinfunction "2_2") (pintype "passive"))
      (node (ref "C60") (pin "2") (pinfunction "2_2") (pintype "passive"))
      (node (ref "C61") (pin "2") (pinfunction "2_2") (pintype "passive"))
      (node (ref "C62") (pin "2") (pinfunction "2_2") (pintype "passive"))
      (node (ref "C63") (pin "2") (pinfunction "2_2") (pintype "passive"))
      (node (ref "C64") (pin "2") (pinfunction "2_2") (pintype "passive"))
      (node (ref "C65") (pin "2") (pinfunction "2_2") (pintype "passive"))
      (node (ref "C66") (pin "2") (pinfunction "2_2") (pintype "passive"))
      (node (ref "C67") (pin "2") (pinfunction "2_2") (pintype "passive"))
      (node (ref "C7") (pin "1") (pinfunction "1_1") (pintype "passive"))
      (node (ref "C75") (pin "2") (pinfunction "2_2") (pintype "passive"))
      (node (ref "C76") (pin "2") (pinfunction "2_2") (pintype "passive"))
      (node (ref "C77") (pin "2") (pinfunction "2_2") (pintype "passive"))
      (node (ref "C78") (pin "2") (pinfunction "2_2") (pintype "passive"))
      (node (ref "C79") (pin "2") (pinfunction "2_2") (pintype "passive"))
      (node (ref "C8") (pin "1") (pinfunction "1_1") (pintype "passive"))
      (node (ref "C80") (pin "2") (pinfunction "2_2") (pintype "passive"))
      (node (ref "C81") (pin "-") (pinfunction "-_-") (pintype "passive"))
      (node (ref "C82") (pin "2") (pinfunction "2_2") (pintype "passive"))
      (node (ref "C83") (pin "2") (pinfunction "2_2") (pintype "passive"))
      (node (ref "C84") (pin "2") (pinfunction "2_2") (pintype "passive"))
      (node (ref "C85") (pin "2") (pinfunction "2_2") (pintype "passive"))
      (node (ref "C86") (pin "-") (pinfunction "-_-") (pintype "passive"))
      (node (ref "C87") (pin "-") (pinfunction "-_-") (pintype "passive"))
      (node (ref "C88") (pin "2") (pinfunction "2_2") (pintype "passive"))
      (node (ref "D2") (pin "-") (pinfunction "A_-") (pintype "passive"))
      (node (ref "D5") (pin "K") (pinfunction "K_K") (pintype "passive"))
      (node (ref "D7") (pin "A") (pinfunction "A_A") (pintype "passive"))
      (node (ref "IC1") (pin "15") (pinfunction "VSS2_15") (pintype "input"))
      (node (ref "IC1") (pin "31") (pinfunction "AVSS_31") (pintype "input"))
      (node (ref "IC1") (pin "36") (pinfunction "VSS3_36") (pintype "input"))
      (node (ref "IC1") (pin "45") (pinfunction "VSS4_45") (pintype "input"))
      (node (ref "IC1") (pin "65") (pinfunction "VSS5_65") (pintype "input"))
      (node (ref "IC1") (pin "75") (pinfunction "VSS1_75") (pintype "input"))
      (node (ref "IC10") (pin "1") (pinfunction "GND_1") (pintype "input"))
      (node (ref "IC10") (pin "2") (pinfunction "GND1_2") (pintype "input"))
      (node (ref "IC11") (pin "1") (pinfunction "A0_1") (pintype "input"))
      (node (ref "IC11") (pin "3") (pinfunction "A2_3") (pintype "input"))
      (node (ref "IC11") (pin "4") (pinfunction "GND_4") (pintype "input"))
      (node (ref "IC12") (pin "5") (pinfunction "GND_5") (pintype "input"))
      (node (ref "IC13") (pin "3") (pinfunction "GND_3") (pintype "bidirectional"))
      (node (ref "IC14") (pin "1") (pinfunction "1_1") (pintype "input"))
      (node (ref "IC15") (pin "1") (pinfunction "1_1") (pintype "input"))
      (node (ref "IC16") (pin "4") (pinfunction "V-_4") (pintype "input"))
      (node (ref "IC2") (pin "14") (pinfunction "~{UB}_14") (pintype "input"))
      (node (ref "IC2") (pin "15") (pinfunction "~{LB}_15") (pintype "input"))
      (node (ref "IC2") (pin "26") (pinfunction "~{CS1}_26") (pintype "input"))
      (node (ref "IC2") (pin "27") (pinfunction "GND1_27") (pintype "bidirectional"))
      (node (ref "IC2") (pin "46") (pinfunction "GND2_46") (pintype "bidirectional"))
      (node (ref "IC2") (pin "47") (pinfunction "~{BYTE}_47") (pintype "input"))
      (node (ref "IC3") (pin "1") (pinfunction "~{OE}_1") (pintype "input"))
      (node (ref "IC3") (pin "10") (pinfunction "GND_10") (pintype "bidirectional"))
      (node (ref "IC4") (pin "1") (pinfunction "~{OE}_1") (pintype "input"))
      (node (ref "IC4") (pin "10") (pinfunction "GND_10") (pintype "bidirectional"))
      (node (ref "IC5") (pin "2") (pinfunction "GND_2") (pintype "input"))
      (node (ref "IC6") (pin "2") (pinfunction "GND_2") (pintype "input"))
      (node (ref "IC7") (pin "1") (pinfunction "A0_1") (pintype "input"))
      (node (ref "IC7") (pin "2") (pinfunction "A1_2") (pintype "input"))
      (node (ref "IC7") (pin "3") (pinfunction "A2_3") (pintype "input"))
      (node (ref "IC7") (pin "4") (pinfunction "GND_4") (pintype "input"))
      (node (ref "IC7") (pin "7") (pinfunction "WP_7") (pintype "input"))
      (node (ref "IC8") (pin "10") (pinfunction "SYNC_10") (pintype "bidirectional"))
      (node (ref "IC8") (pin "EP") (pinfunction "GND_EP") (pintype "bidirectional"))
      (node (ref "IC9") (pin "4") (pinfunction "GND_4") (pintype "input"))
      (node (ref "J1") (pin "15") (pinfunction "15_15") (pintype "passive"))
      (node (ref "J11") (pin "6") (pinfunction "VSS_6") (pintype "passive"))
      (node (ref "J11") (pin "G1") (pinfunction "G1_G1") (pintype "passive"))
      (node (ref "J11") (pin "G3") (pinfunction "G3_G3") (pintype "passive"))
      (node (ref "J11") (pin "G4") (pinfunction "G4_G4") (pintype "passive"))
      (node (ref "J11") (pin "G5") (pinfunction "G5_G5") (pintype "passive"))
      (node (ref "J11") (pin "G6") (pinfunction "G6_G6") (pintype "passive"))
      (node (ref "J12") (pin "4_GND") (pinfunction "GND_4_GND") (pintype "bidirectional"))
      (node (ref "J12") (pin "SH1") (pinfunction "GND_SH1_SH1") (pintype "bidirectional"))
      (node (ref "J12") (pin "SH2") (pinfunction "GND_SH2_SH2") (pintype "bidirectional"))
      (node (ref "J14") (pin "1") (pinfunction "1_1") (pintype "passive"))
      (node (ref "J15") (pin "9") (pinfunction "9_9") (pintype "passive"))
      (node (ref "J17") (pin "3") (pinfunction "3_3") (pintype "passive"))
      (node (ref "J2") (pin "15") (pinfunction "15_15") (pintype "passive"))
      (node (ref "J5") (pin "1") (pinfunction "1_1") (pintype "bidirectional"))
      (node (ref "J6") (pin "1") (pinfunction "1_1") (pintype "bidirectional"))
      (node (ref "L12") (pin "1") (pinfunction "1_1") (pintype "passive"))
      (node (ref "PCB1") (pin "PAD_GND_1") (pinfunction "PAD_GND_1_PAD_GND_1") (pintype "bidirectional"))
      (node (ref "PCB1") (pin "PAD_GND_2") (pinfunction "PAD_GND_2_PAD_GND_2") (pintype "bidirectional"))
      (node (ref "PCB1") (pin "PAD_GND_3") (pinfunction "PAD_GND_3_PAD_GND_3") (pintype "bidirectional"))
      (node (ref "PCB1") (pin "PAD_GND_4") (pinfunction "PAD_GND_4_PAD_GND_4") (pintype "bidirectional"))
      (node (ref "PCB2") (pin "VPS_PCB_1") (pinfunction "VPS_PCB_1_VPS_PCB_1") (pintype "bidirectional"))
      (node (ref "PCB3") (pin "1") (pinfunction "P$1_1") (pintype "bidirectional"))
      (node (ref "Q10") (pin "4") (pinfunction "S_4") (pintype "passive"))
      (node (ref "Q11") (pin "4") (pinfunction "S_4") (pintype "passive"))
      (node (ref "Q12") (pin "4") (pinfunction "S_4") (pintype "passive"))
      (node (ref "Q13") (pin "4") (pinfunction "S_4") (pintype "passive"))
      (node (ref "Q14") (pin "1") (pinfunction "S_1") (pintype "passive"))
      (node (ref "Q3") (pin "1") (pinfunction "S_1") (pintype "passive"))
      (node (ref "R1") (pin "1") (pinfunction "1_1") (pintype "passive"))
      (node (ref "R112") (pin "2") (pinfunction "2_2") (pintype "passive"))
      (node (ref "R118") (pin "2") (pinfunction "2_2") (pintype "passive"))
      (node (ref "R127") (pin "1") (pinfunction "1_1") (pintype "passive"))
      (node (ref "R17") (pin "2") (pinfunction "2_2") (pintype "passive"))
      (node (ref "R19") (pin "2") (pinfunction "2_2") (pintype "passive"))
      (node (ref "R2") (pin "1") (pinfunction "1_1") (pintype "passive"))
      (node (ref "R21") (pin "2") (pinfunction "2_2") (pintype "passive"))
      (node (ref "R31") (pin "2") (pinfunction "2_2") (pintype "passive"))
      (node (ref "R40") (pin "1") (pinfunction "1_1") (pintype "passive"))
      (node (ref "R41") (pin "2") (pinfunction "2_2") (pintype "passive"))
      (node (ref "R43") (pin "1") (pinfunction "1_1") (pintype "passive"))
      (node (ref "R44") (pin "2") (pinfunction "2_2") (pintype "passive"))
      (node (ref "R46") (pin "1") (pinfunction "1_1") (pintype "passive"))
      (node (ref "R48") (pin "1") (pinfunction "1_1") (pintype "passive"))
      (node (ref "R5") (pin "1") (pinfunction "1_1") (pintype "passive"))
      (node (ref "R51") (pin "1") (pinfunction "1_1") (pintype "passive"))
      (node (ref "R52") (pin "2") (pinfunction "2_2") (pintype "passive"))
      (node (ref "R53") (pin "2") (pinfunction "2_2") (pintype "passive"))
      (node (ref "R54") (pin "2") (pinfunction "2_2") (pintype "passive"))
      (node (ref "R57") (pin "1") (pinfunction "1_1") (pintype "passive"))
      (node (ref "R58") (pin "2") (pinfunction "2_2") (pintype "passive"))
      (node (ref "R59") (pin "2") (pinfunction "2_2") (pintype "passive"))
      (node (ref "R6") (pin "2") (pinfunction "2_2") (pintype "passive"))
      (node (ref "R60") (pin "2") (pinfunction "2_2") (pintype "passive"))
      (node (ref "R64") (pin "2") (pinfunction "2_2") (pintype "passive"))
      (node (ref "R67") (pin "2") (pinfunction "2_2") (pintype "passive"))
      (node (ref "R7") (pin "2") (pinfunction "2_2") (pintype "passive"))
      (node (ref "R70") (pin "2") (pinfunction "2_2") (pintype "passive"))
      (node (ref "R71") (pin "2") (pinfunction "2_2") (pintype "passive"))
      (node (ref "R76") (pin "2") (pinfunction "2_2") (pintype "passive"))
      (node (ref "R80") (pin "2") (pinfunction "2_2") (pintype "passive"))
      (node (ref "R83") (pin "2") (pinfunction "2_2") (pintype "passive"))
      (node (ref "R86") (pin "2") (pinfunction "2_2") (pintype "passive"))
      (node (ref "R88") (pin "2") (pinfunction "2_2") (pintype "passive"))
      (node (ref "R96") (pin "2") (pinfunction "2_2") (pintype "passive"))
      (node (ref "R99") (pin "2") (pinfunction "2_2") (pintype "passive"))
    )
    (net (code "131") (name "Net-(C24-Pad2)") (class "Default")
      (node (ref "C24") (pin "2") (pinfunction "2_2") (pintype "passive"))
      (node (ref "R77") (pin "2") (pinfunction "2_2") (pintype "passive"))
    )
    (net (code "132") (name "Net-(C32-Pad1)") (class "Default")
      (node (ref "C32") (pin "1") (pinfunction "1_1") (pintype "passive"))
      (node (ref "R68") (pin "2") (pinfunction "2_2") (pintype "passive"))
      (node (ref "R69") (pin "1") (pinfunction "1_1") (pintype "passive"))
    )
    (net (code "133") (name "Net-(C37-Pad1)") (class "Default")
      (node (ref "C37") (pin "1") (pinfunction "1_1") (pintype "passive"))
      (node (ref "R78") (pin "2") (pinfunction "2_2") (pintype "passive"))
      (node (ref "R79") (pin "1") (pinfunction "1_1") (pintype "passive"))
    )
    (net (code "134") (name "Net-(C38-Pad1)") (class "Default")
      (node (ref "C38") (pin "1") (pinfunction "1_1") (pintype "passive"))
      (node (ref "R84") (pin "2") (pinfunction "2_2") (pintype "passive"))
      (node (ref "R85") (pin "1") (pinfunction "1_1") (pintype "passive"))
    )
    (net (code "135") (name "Net-(C39-Pad1)") (class "Default")
      (node (ref "C39") (pin "1") (pinfunction "1_1") (pintype "passive"))
      (node (ref "IC14") (pin "4") (pinfunction "4_4") (pintype "input"))
      (node (ref "R30") (pin "1") (pinfunction "1_1") (pintype "passive"))
    )
    (net (code "136") (name "Net-(C40-Pad1)") (class "Default")
      (node (ref "C40") (pin "1") (pinfunction "1_1") (pintype "passive"))
      (node (ref "R90") (pin "1") (pinfunction "1_1") (pintype "passive"))
      (node (ref "R91") (pin "1") (pinfunction "1_1") (pintype "passive"))
    )
    (net (code "137") (name "Net-(C46-Pad1)") (class "Default")
      (node (ref "C46") (pin "1") (pinfunction "1_1") (pintype "passive"))
      (node (ref "R62") (pin "2") (pinfunction "2_2") (pintype "passive"))
      (node (ref "R63") (pin "1") (pinfunction "1_1") (pintype "passive"))
    )
    (net (code "138") (name "Net-(C71-Pad+)") (class "Default")
      (node (ref "C71") (pin "+") (pinfunction "+_+") (pintype "passive"))
      (node (ref "C72") (pin "1") (pinfunction "1_1") (pintype "passive"))
      (node (ref "J9") (pin "1") (pinfunction "1_1") (pintype "passive"))
      (node (ref "R124") (pin "2") (pinfunction "2_2") (pintype "passive"))
    )
    (net (code "139") (name "Net-(C71-Pad-)") (class "Default")
      (node (ref "C71") (pin "-") (pinfunction "-_-") (pintype "passive"))
      (node (ref "C72") (pin "2") (pinfunction "2_2") (pintype "passive"))
      (node (ref "R110") (pin "2") (pinfunction "2_2") (pintype "passive"))
      (node (ref "R111") (pin "1") (pinfunction "1_1") (pintype "passive"))
      (node (ref "R114") (pin "2") (pinfunction "2_2") (pintype "passive"))
      (node (ref "R115") (pin "1") (pinfunction "1_1") (pintype "passive"))
    )
    (net (code "140") (name "Net-(C73-Pad+)") (class "Default")
      (node (ref "C73") (pin "+") (pinfunction "+_+") (pintype "passive"))
      (node (ref "C74") (pin "1") (pinfunction "1_1") (pintype "passive"))
      (node (ref "J10") (pin "1") (pinfunction "1_1") (pintype "passive"))
      (node (ref "R125") (pin "2") (pinfunction "2_2") (pintype "passive"))
    )
    (net (code "141") (name "Net-(C73-Pad-)") (class "Default")
      (node (ref "C73") (pin "-") (pinfunction "-_-") (pintype "passive"))
      (node (ref "C74") (pin "2") (pinfunction "2_2") (pintype "passive"))
      (node (ref "R116") (pin "2") (pinfunction "2_2") (pintype "passive"))
      (node (ref "R117") (pin "1") (pinfunction "1_1") (pintype "passive"))
      (node (ref "R122") (pin "2") (pinfunction "2_2") (pintype "passive"))
      (node (ref "R123") (pin "1") (pinfunction "1_1") (pintype "passive"))
    )
    (net (code "142") (name "Net-(D2-C)") (class "Default")
      (node (ref "C26") (pin "1") (pinfunction "1_1") (pintype "passive"))
      (node (ref "C30") (pin "1") (pinfunction "1_1") (pintype "passive"))
      (node (ref "C31") (pin "+") (pinfunction "+_+") (pintype "passive"))
      (node (ref "D2") (pin "+") (pinfunction "C_+") (pintype "passive"))
      (node (ref "IC8") (pin "1") (pinfunction "BD_1") (pintype "bidirectional"))
      (node (ref "L9") (pin "2") (pinfunction "2_2") (pintype "passive"))
      (node (ref "R129") (pin "2") (pinfunction "2_2") (pintype "passive"))
      (node (ref "R20") (pin "1") (pinfunction "1_1") (pintype "passive"))
    )
    (net (code "143") (name "Net-(D3-PadA)") (class "Default")
      (node (ref "D3") (pin "A") (pinfunction "A_A") (pintype "passive"))
      (node (ref "D4") (pin "A") (pinfunction "A_A") (pintype "passive"))
      (node (ref "J3") (pin "2") (pinfunction "2_2") (pintype "passive"))
      (node (ref "J3") (pin "7") (pinfunction "7_7") (pintype "passive"))
      (node (ref "J3") (pin "8") (pinfunction "8_8") (pintype "passive"))
      (node (ref "J4") (pin "2") (pinfunction "2_2") (pintype "passive"))
      (node (ref "J4") (pin "7") (pinfunction "7_7") (pintype "passive"))
      (node (ref "J4") (pin "8") (pinfunction "8_8") (pintype "passive"))
      (node (ref "L12") (pin "2") (pinfunction "2_2") (pintype "passive"))
    )
    (net (code "144") (name "Net-(D5-PadA)") (class "Default")
      (node (ref "D5") (pin "A") (pinfunction "A_A") (pintype "passive"))
      (node (ref "R29") (pin "2") (pinfunction "2_2") (pintype "passive"))
    )
    (net (code "145") (name "Net-(IC1-AVDD)") (class "Default")
      (node (ref "C55") (pin "1") (pinfunction "1_1") (pintype "passive"))
      (node (ref "C56") (pin "+") (pinfunction "+_+") (pintype "passive"))
      (node (ref "C88") (pin "1") (pinfunction "1_1") (pintype "passive"))
      (node (ref "IC1") (pin "30") (pinfunction "AVDD_30") (pintype "input"))
      (node (ref "R92") (pin "2") (pinfunction "2_2") (pintype "passive"))
    )
    (net (code "146") (name "Net-(IC1-CLKI{slash}RC12{slash}OSC1)") (class "Default")
      (node (ref "C60") (pin "1") (pinfunction "1_1") (pintype "passive"))
      (node (ref "IC1") (pin "63") (pinfunction "CLKI/RC12/OSC1_63") (pintype "bidirectional"))
      (node (ref "X1") (pin "3") (pinfunction "2_3") (pintype "passive"))
    )
    (net (code "147") (name "Net-(IC1-CLKO{slash}RC15{slash}OSC2)") (class "Default")
      (node (ref "C61") (pin "1") (pinfunction "1_1") (pintype "passive"))
      (node (ref "IC1") (pin "64") (pinfunction "CLKO/RC15/OSC2_64") (pintype "bidirectional"))
      (node (ref "X1") (pin "1") (pinfunction "1_1") (pintype "passive"))
    )
    (net (code "148") (name "Net-(IC1-VCAP)") (class "Default")
      (node (ref "C53") (pin "1") (pinfunction "1_1") (pintype "passive"))
      (node (ref "C54") (pin "+") (pinfunction "+_+") (pintype "passive"))
      (node (ref "IC1") (pin "85") (pinfunction "VCAP_85") (pintype "input"))
    )
    (net (code "149") (name "Net-(IC5-OUT)") (class "Default")
      (node (ref "C19") (pin "1") (pinfunction "1_1") (pintype "passive"))
      (node (ref "C20") (pin "+") (pinfunction "+_+") (pintype "passive"))
      (node (ref "IC5") (pin "5") (pinfunction "OUT_5") (pintype "output"))
      (node (ref "R126") (pin "2") (pinfunction "2_2") (pintype "passive"))
    )
    (net (code "150") (name "Net-(IC6-HTH)") (class "Default")
      (node (ref "IC6") (pin "1") (pinfunction "HTH_1") (pintype "input"))
      (node (ref "R46") (pin "2") (pinfunction "2_2") (pintype "passive"))
      (node (ref "R47") (pin "1") (pinfunction "1_1") (pintype "passive"))
    )
    (net (code "151") (name "Net-(IC6-LTH)") (class "Default")
      (node (ref "IC6") (pin "3") (pinfunction "LTH_3") (pintype "input"))
      (node (ref "R33") (pin "1") (pinfunction "1_1") (pintype "passive"))
      (node (ref "R47") (pin "2") (pinfunction "2_2") (pintype "passive"))
    )
    (net (code "152") (name "Net-(IC6-VDD)") (class "Default")
      (node (ref "C35") (pin "1") (pinfunction "1_1") (pintype "passive"))
      (node (ref "IC6") (pin "5") (pinfunction "VDD_5") (pintype "input"))
      (node (ref "R28") (pin "1") (pinfunction "1_1") (pintype "passive"))
    )
    (net (code "153") (name "Net-(IC8-BOOST)") (class "Default")
      (node (ref "C25") (pin "2") (pinfunction "2_2") (pintype "passive"))
      (node (ref "IC8") (pin "2") (pinfunction "BOOST_2") (pintype "bidirectional"))
    )
    (net (code "154") (name "Net-(IC8-EN)") (class "Default")
      (node (ref "IC8") (pin "5") (pinfunction "EN_5") (pintype "bidirectional"))
      (node (ref "JP1") (pin "2") (pinfunction "2_2") (pintype "bidirectional"))
      (node (ref "R22") (pin "2") (pinfunction "2_2") (pintype "passive"))
    )
    (net (code "155") (name "Net-(IC8-FB)") (class "Default")
      (node (ref "C26") (pin "2") (pinfunction "2_2") (pintype "passive"))
      (node (ref "IC8") (pin "6") (pinfunction "FB_6") (pintype "bidirectional"))
      (node (ref "R19") (pin "1") (pinfunction "1_1") (pintype "passive"))
      (node (ref "R20") (pin "2") (pinfunction "2_2") (pintype "passive"))
    )
    (net (code "156") (name "Net-(IC8-RT)") (class "Default")
      (node (ref "IC8") (pin "8") (pinfunction "RT_8") (pintype "bidirectional"))
      (node (ref "R17") (pin "1") (pinfunction "1_1") (pintype "passive"))
    )
    (net (code "157") (name "Net-(IC8-SS)") (class "Default")
      (node (ref "IC8") (pin "7") (pinfunction "SS_7") (pintype "bidirectional"))
      (node (ref "R77") (pin "1") (pinfunction "1_1") (pintype "passive"))
    )
    (net (code "158") (name "Net-(IC8-SW)") (class "Default")
      (node (ref "C25") (pin "1") (pinfunction "1_1") (pintype "passive"))
      (node (ref "D7") (pin "K") (pinfunction "K_K") (pintype "passive"))
      (node (ref "IC8") (pin "3") (pinfunction "SW_3") (pintype "bidirectional"))
      (node (ref "L9") (pin "1") (pinfunction "1_1") (pintype "passive"))
    )
    (net (code "159") (name "Net-(IC10-OUT)") (class "Default")
      (node (ref "IC10") (pin "3") (pinfunction "OUT_3") (pintype "output"))
      (node (ref "R102") (pin "1") (pinfunction "1_1") (pintype "passive"))
    )
    (net (code "160") (name "Net-(IC10-VIN+)") (class "Default")
      (node (ref "C29") (pin "1") (pinfunction "1_1") (pintype "passive"))
      (node (ref "F1") (pin "1") (pinfunction "1_1") (pintype "passive"))
      (node (ref "IC10") (pin "5") (pinfunction "VIN+_5") (pintype "input"))
      (node (ref "R39") (pin "2") (pinfunction "2_2") (pintype "passive"))
    )
    (net (code "161") (name "Net-(IC11-WP)") (class "Default")
      (node (ref "IC11") (pin "7") (pinfunction "WP_7") (pintype "input"))
      (node (ref "R18") (pin "2") (pinfunction "2_2") (pintype "passive"))
      (node (ref "TP1") (pin "P$1") (pinfunction "TP_P$1") (pintype "passive"))
    )
    (net (code "162") (name "Net-(IC13-VIN)") (class "Default")
      (node (ref "C58") (pin "1") (pinfunction "1_1") (pintype "passive"))
      (node (ref "C59") (pin "1") (pinfunction "1_1") (pintype "passive"))
      (node (ref "IC13") (pin "1") (pinfunction "VIN_1") (pintype "bidirectional"))
      (node (ref "R93") (pin "2") (pinfunction "2_2") (pintype "passive"))
    )
    (net (code "163") (name "Net-(IC16A-+IN)") (class "Default")
      (node (ref "C62") (pin "1") (pinfunction "1_1") (pintype "passive"))
      (node (ref "IC16") (pin "3") (pinfunction "+IN_3") (pintype "input"))
      (node (ref "R95") (pin "2") (pinfunction "2_2") (pintype "passive"))
      (node (ref "R96") (pin "1") (pinfunction "1_1") (pintype "passive"))
    )
    (net (code "164") (name "Net-(IC16A--IN)") (class "Default")
      (node (ref "IC16") (pin "1") (pinfunction "OUT_1") (pintype "output"))
      (node (ref "IC16") (pin "2") (pinfunction "-IN_2") (pintype "input"))
      (node (ref "R101") (pin "2") (pinfunction "2_2") (pintype "passive"))
    )
    (net (code "165") (name "Net-(IC16B-+IN)") (class "Default")
      (node (ref "C63") (pin "1") (pinfunction "1_1") (pintype "passive"))
      (node (ref "IC16") (pin "5") (pinfunction "+IN_5") (pintype "input"))
      (node (ref "R98") (pin "2") (pinfunction "2_2") (pintype "passive"))
      (node (ref "R99") (pin "1") (pinfunction "1_1") (pintype "passive"))
    )
    (net (code "166") (name "Net-(IC16B--IN)") (class "Default")
      (node (ref "IC16") (pin "6") (pinfunction "-IN_6") (pintype "input"))
      (node (ref "IC16") (pin "7") (pinfunction "OUT_7") (pintype "output"))
      (node (ref "R100") (pin "2") (pinfunction "2_2") (pintype "passive"))
    )
    (net (code "167") (name "Net-(IC16C-V+)") (class "Default")
      (node (ref "C67") (pin "1") (pinfunction "1_1") (pintype "passive"))
      (node (ref "IC16") (pin "8") (pinfunction "V+_8") (pintype "input"))
      (node (ref "R103") (pin "1") (pinfunction "1_1") (pintype "passive"))
    )
    (net (code "168") (name "Net-(J5-Pad4)") (class "Default")
      (node (ref "J5") (pin "4") (pinfunction "4_4") (pintype "bidirectional"))
      (node (ref "R62") (pin "1") (pinfunction "1_1") (pintype "passive"))
    )
    (net (code "169") (name "Net-(J6-Pad4)") (class "Default")
      (node (ref "J6") (pin "4") (pinfunction "4_4") (pintype "bidirectional"))
      (node (ref "R78") (pin "1") (pinfunction "1_1") (pintype "passive"))
    )
    (net (code "170") (name "Net-(J7-Pad2)") (class "Default")
      (node (ref "J7") (pin "2") (pinfunction "2_2") (pintype "passive"))
      (node (ref "R68") (pin "1") (pinfunction "1_1") (pintype "passive"))
    )
    (net (code "171") (name "Net-(J8-Pad2)") (class "Default")
      (node (ref "J8") (pin "2") (pinfunction "2_2") (pintype "passive"))
      (node (ref "R84") (pin "1") (pinfunction "1_1") (pintype "passive"))
    )
    (net (code "172") (name "Net-(J9-Pad2)") (class "Default")
      (node (ref "J9") (pin "2") (pinfunction "2_2") (pintype "passive"))
      (node (ref "R110") (pin "1") (pinfunction "1_1") (pintype "passive"))
      (node (ref "R114") (pin "1") (pinfunction "1_1") (pintype "passive"))
    )
    (net (code "173") (name "Net-(J10-Pad2)") (class "Default")
      (node (ref "J10") (pin "2") (pinfunction "2_2") (pintype "passive"))
      (node (ref "R116") (pin "1") (pinfunction "1_1") (pintype "passive"))
      (node (ref "R122") (pin "1") (pinfunction "1_1") (pintype "passive"))
    )
    (net (code "174") (name "Net-(J12-+5V)") (class "Default")
      (node (ref "C85") (pin "1") (pinfunction "1_1") (pintype "passive"))
      (node (ref "D6") (pin "A") (pinfunction "A_A") (pintype "passive"))
      (node (ref "IC15") (pin "4") (pinfunction "4_4") (pintype "input"))
      (node (ref "J12") (pin "1_+5V") (pinfunction "+5V_1_+5V") (pintype "bidirectional"))
      (node (ref "R128") (pin "1") (pinfunction "1_1") (pintype "passive"))
    )
    (net (code "175") (name "Net-(JP1-Pad1)") (class "Default")
      (node (ref "JP1") (pin "1") (pinfunction "1_1") (pintype "bidirectional"))
      (node (ref "R21") (pin "1") (pinfunction "1_1") (pintype "passive"))
    )
    (net (code "176") (name "Net-(L7-Pad1)") (class "Default")
      (node (ref "L7") (pin "1") (pinfunction "1_1") (pintype "passive"))
      (node (ref "R108") (pin "1") (pinfunction "1_1") (pintype "passive"))
    )
    (net (code "177") (name "Net-(L8-Pad1)") (class "Default")
      (node (ref "L8") (pin "1") (pinfunction "1_1") (pintype "passive"))
      (node (ref "R109") (pin "1") (pinfunction "1_1") (pintype "passive"))
    )
    (net (code "178") (name "Net-(L13-Pad2)") (class "Default")
      (node (ref "L13") (pin "2") (pinfunction "2_2") (pintype "passive"))
      (node (ref "R92") (pin "1") (pinfunction "1_1") (pintype "passive"))
    )
    (net (code "179") (name "Net-(Q1A-G)") (class "Default")
      (node (ref "C21") (pin "2") (pinfunction "2_2") (pintype "passive"))
      (node (ref "Q1") (pin "2") (pinfunction "G_2") (pintype "passive"))
      (node (ref "R10") (pin "2") (pinfunction "2_2") (pintype "passive"))
      (node (ref "R9") (pin "1") (pinfunction "1_1") (pintype "passive"))
    )
    (net (code "180") (name "Net-(Q1A-S)") (class "Default")
      (node (ref "Q1") (pin "1") (pinfunction "S_1") (pintype "passive"))
      (node (ref "R8") (pin "1") (pinfunction "1_1") (pintype "passive"))
    )
    (net (code "181") (name "Net-(Q1B-G)") (class "Default")
      (node (ref "C70") (pin "2") (pinfunction "2_2") (pintype "passive"))
      (node (ref "Q1") (pin "5") (pinfunction "G_5") (pintype "passive"))
      (node (ref "R75") (pin "1") (pinfunction "1_1") (pintype "passive"))
      (node (ref "R82") (pin "2") (pinfunction "2_2") (pintype "passive"))
    )
    (net (code "182") (name "Net-(Q1B-S)") (class "Default")
      (node (ref "Q1") (pin "4") (pinfunction "S_4") (pintype "passive"))
      (node (ref "R106") (pin "1") (pinfunction "1_1") (pintype "passive"))
    )
    (net (code "183") (name "Net-(Q2A-G)") (class "Default")
      (node (ref "C68") (pin "2") (pinfunction "2_2") (pintype "passive"))
      (node (ref "Q2") (pin "2") (pinfunction "G_2") (pintype "passive"))
      (node (ref "R107") (pin "1") (pinfunction "1_1") (pintype "passive"))
      (node (ref "R87") (pin "2") (pinfunction "2_2") (pintype "passive"))
    )
    (net (code "184") (name "Net-(Q2A-S)") (class "Default")
      (node (ref "Q2") (pin "1") (pinfunction "S_1") (pintype "passive"))
      (node (ref "R104") (pin "1") (pinfunction "1_1") (pintype "passive"))
    )
    (net (code "185") (name "Net-(Q2B-G)") (class "Default")
      (node (ref "C69") (pin "2") (pinfunction "2_2") (pintype "passive"))
      (node (ref "Q2") (pin "5") (pinfunction "G_5") (pintype "passive"))
      (node (ref "R24") (pin "1") (pinfunction "1_1") (pintype "passive"))
      (node (ref "R65") (pin "2") (pinfunction "2_2") (pintype "passive"))
    )
    (net (code "186") (name "Net-(Q2B-S)") (class "Default")
      (node (ref "Q2") (pin "4") (pinfunction "S_4") (pintype "passive"))
      (node (ref "R105") (pin "1") (pinfunction "1_1") (pintype "passive"))
    )
    (net (code "187") (name "Net-(Q3A-D)") (class "Default")
      (node (ref "Q3") (pin "6") (pinfunction "D_6") (pintype "passive"))
      (node (ref "R111") (pin "2") (pinfunction "2_2") (pintype "passive"))
      (node (ref "R115") (pin "2") (pinfunction "2_2") (pintype "passive"))
    )
    (net (code "188") (name "Net-(Q3A-G)") (class "Default")
      (node (ref "Q3") (pin "2") (pinfunction "G_2") (pintype "passive"))
      (node (ref "R112") (pin "1") (pinfunction "1_1") (pintype "passive"))
      (node (ref "R113") (pin "1") (pinfunction "1_1") (pintype "passive"))
    )
    (net (code "189") (name "Net-(Q4A-D)") (class "Default")
      (node (ref "C33") (pin "2") (pinfunction "2_2") (pintype "passive"))
      (node (ref "Q4") (pin "6") (pinfunction "D_6") (pintype "passive"))
      (node (ref "Q5") (pin "1") (pinfunction "G_1") (pintype "passive"))
      (node (ref "R42") (pin "2") (pinfunction "2_2") (pintype "passive"))
    )
    (net (code "190") (name "Net-(Q4A-S)") (class "Default")
      (node (ref "Q4") (pin "1") (pinfunction "S_1") (pintype "passive"))
      (node (ref "R40") (pin "2") (pinfunction "2_2") (pintype "passive"))
    )
    (net (code "191") (name "Net-(Q4B-D)") (class "Default")
      (node (ref "C34") (pin "2") (pinfunction "2_2") (pintype "passive"))
      (node (ref "Q4") (pin "3") (pinfunction "D_3") (pintype "passive"))
      (node (ref "Q5") (pin "3") (pinfunction "G_3") (pintype "passive"))
      (node (ref "R45") (pin "2") (pinfunction "2_2") (pintype "passive"))
    )
    (net (code "192") (name "Net-(Q4B-S)") (class "Default")
      (node (ref "Q4") (pin "4") (pinfunction "S_4") (pintype "passive"))
      (node (ref "R43") (pin "2") (pinfunction "2_2") (pintype "passive"))
    )
    (net (code "193") (name "Net-(Q5A-D)") (class "Default")
      (node (ref "F1") (pin "2") (pinfunction "2_2") (pintype "passive"))
      (node (ref "Q5") (pin "6") (pinfunction "D_6") (pintype "passive"))
      (node (ref "R35") (pin "1") (pinfunction "1_1") (pintype "passive"))
      (node (ref "R37") (pin "1") (pinfunction "1_1") (pintype "passive"))
      (node (ref "R97") (pin "1") (pinfunction "1_1") (pintype "passive"))
    )
    (net (code "194") (name "Net-(Q6A-G)") (class "Default")
      (node (ref "C42") (pin "2") (pinfunction "2_2") (pintype "passive"))
      (node (ref "Q6") (pin "1") (pinfunction "G_1") (pintype "passive"))
      (node (ref "Q7") (pin "6") (pinfunction "D_6") (pintype "passive"))
      (node (ref "R50") (pin "2") (pinfunction "2_2") (pintype "passive"))
    )
    (net (code "195") (name "Net-(Q6B-G)") (class "Default")
      (node (ref "C43") (pin "2") (pinfunction "2_2") (pintype "passive"))
      (node (ref "Q6") (pin "3") (pinfunction "G_3") (pintype "passive"))
      (node (ref "Q7") (pin "3") (pinfunction "D_3") (pintype "passive"))
      (node (ref "R55") (pin "2") (pinfunction "2_2") (pintype "passive"))
    )
    (net (code "196") (name "Net-(Q7A-S)") (class "Default")
      (node (ref "Q7") (pin "1") (pinfunction "S_1") (pintype "passive"))
      (node (ref "R51") (pin "2") (pinfunction "2_2") (pintype "passive"))
    )
    (net (code "197") (name "Net-(Q7B-S)") (class "Default")
      (node (ref "Q7") (pin "4") (pinfunction "S_4") (pintype "passive"))
      (node (ref "R53") (pin "1") (pinfunction "1_1") (pintype "passive"))
    )
    (net (code "198") (name "Net-(Q8A-G)") (class "Default")
      (node (ref "C44") (pin "2") (pinfunction "2_2") (pintype "passive"))
      (node (ref "Q8") (pin "1") (pinfunction "G_1") (pintype "passive"))
      (node (ref "Q9") (pin "6") (pinfunction "D_6") (pintype "passive"))
      (node (ref "R56") (pin "2") (pinfunction "2_2") (pintype "passive"))
    )
    (net (code "199") (name "Net-(Q8B-G)") (class "Default")
      (node (ref "C45") (pin "2") (pinfunction "2_2") (pintype "passive"))
      (node (ref "Q8") (pin "3") (pinfunction "G_3") (pintype "passive"))
      (node (ref "Q9") (pin "3") (pinfunction "D_3") (pintype "passive"))
      (node (ref "R61") (pin "2") (pinfunction "2_2") (pintype "passive"))
    )
    (net (code "200") (name "Net-(Q9A-S)") (class "Default")
      (node (ref "Q9") (pin "1") (pinfunction "S_1") (pintype "passive"))
      (node (ref "R57") (pin "2") (pinfunction "2_2") (pintype "passive"))
    )
    (net (code "201") (name "Net-(Q9B-S)") (class "Default")
      (node (ref "Q9") (pin "4") (pinfunction "S_4") (pintype "passive"))
      (node (ref "R59") (pin "1") (pinfunction "1_1") (pintype "passive"))
    )
    (net (code "202") (name "Net-(Q10A-D)") (class "Default")
      (node (ref "Q10") (pin "6") (pinfunction "D_6") (pintype "passive"))
      (node (ref "R79") (pin "2") (pinfunction "2_2") (pintype "passive"))
    )
    (net (code "203") (name "Net-(Q10A-S)") (class "Default")
      (node (ref "Q10") (pin "1") (pinfunction "S_1") (pintype "passive"))
      (node (ref "Q10") (pin "5") (pinfunction "G_5") (pintype "passive"))
      (node (ref "R80") (pin "1") (pinfunction "1_1") (pintype "passive"))
    )
    (net (code "204") (name "Net-(Q11A-D)") (class "Default")
      (node (ref "Q11") (pin "6") (pinfunction "D_6") (pintype "passive"))
      (node (ref "R63") (pin "2") (pinfunction "2_2") (pintype "passive"))
    )
    (net (code "205") (name "Net-(Q11A-S)") (class "Default")
      (node (ref "Q11") (pin "1") (pinfunction "S_1") (pintype "passive"))
      (node (ref "Q11") (pin "5") (pinfunction "G_5") (pintype "passive"))
      (node (ref "R64") (pin "1") (pinfunction "1_1") (pintype "passive"))
    )
    (net (code "206") (name "Net-(Q12A-D)") (class "Default")
      (node (ref "Q12") (pin "6") (pinfunction "D_6") (pintype "passive"))
      (node (ref "R85") (pin "2") (pinfunction "2_2") (pintype "passive"))
    )
    (net (code "207") (name "Net-(Q12A-S)") (class "Default")
      (node (ref "Q12") (pin "1") (pinfunction "S_1") (pintype "passive"))
      (node (ref "Q12") (pin "5") (pinfunction "G_5") (pintype "passive"))
      (node (ref "R86") (pin "1") (pinfunction "1_1") (pintype "passive"))
    )
    (net (code "208") (name "Net-(Q13A-D)") (class "Default")
      (node (ref "Q13") (pin "6") (pinfunction "D_6") (pintype "passive"))
      (node (ref "R69") (pin "2") (pinfunction "2_2") (pintype "passive"))
    )
    (net (code "209") (name "Net-(Q13A-S)") (class "Default")
      (node (ref "Q13") (pin "1") (pinfunction "S_1") (pintype "passive"))
      (node (ref "Q13") (pin "5") (pinfunction "G_5") (pintype "passive"))
      (node (ref "R70") (pin "1") (pinfunction "1_1") (pintype "passive"))
    )
    (net (code "210") (name "Net-(Q14A-D)") (class "Default")
      (node (ref "Q14") (pin "6") (pinfunction "D_6") (pintype "passive"))
      (node (ref "R117") (pin "2") (pinfunction "2_2") (pintype "passive"))
      (node (ref "R123") (pin "2") (pinfunction "2_2") (pintype "passive"))
    )
    (net (code "211") (name "Net-(Q14A-G)") (class "Default")
      (node (ref "Q14") (pin "2") (pinfunction "G_2") (pintype "passive"))
      (node (ref "R118") (pin "1") (pinfunction "1_1") (pintype "passive"))
      (node (ref "R119") (pin "1") (pinfunction "1_1") (pintype "passive"))
    )
    (net (code "212") (name "Net-(R23-Pad1)") (class "Default")
      (node (ref "R23") (pin "1") (pinfunction "1_1") (pintype "passive"))
      (node (ref "R49") (pin "2") (pinfunction "2_2") (pintype "passive"))
    )
    (net (code "213") (name "Net-(R35-Pad2)") (class "Default")
      (node (ref "R35") (pin "2") (pinfunction "2_2") (pintype "passive"))
      (node (ref "R36") (pin "1") (pinfunction "1_1") (pintype "passive"))
      (node (ref "R37") (pin "2") (pinfunction "2_2") (pintype "passive"))
      (node (ref "R38") (pin "1") (pinfunction "1_1") (pintype "passive"))
    )
    (net (code "214") (name "Net-(R94-Pad2)") (class "Default")
      (node (ref "R94") (pin "2") (pinfunction "2_2") (pintype "passive"))
      (node (ref "R95") (pin "1") (pinfunction "1_1") (pintype "passive"))
    )
    (net (code "215") (name "Net-(R97-Pad2)") (class "Default")
      (node (ref "R97") (pin "2") (pinfunction "2_2") (pintype "passive"))
      (node (ref "R98") (pin "1") (pinfunction "1_1") (pintype "passive"))
    )
    (net (code "216") (name "VBAT") (class "Default")
      (node (ref "C22") (pin "1") (pinfunction "1_1") (pintype "passive"))
      (node (ref "C23") (pin "1") (pinfunction "1_1") (pintype "passive"))
      (node (ref "C42") (pin "1") (pinfunction "1_1") (pintype "passive"))
      (node (ref "C43") (pin "1") (pinfunction "1_1") (pintype "passive"))
      (node (ref "C44") (pin "1") (pinfunction "1_1") (pintype "passive"))
      (node (ref "C45") (pin "1") (pinfunction "1_1") (pintype "passive"))
      (node (ref "C83") (pin "1") (pinfunction "1_1") (pintype "passive"))
      (node (ref "C84") (pin "1") (pinfunction "1_1") (pintype "passive"))
      (node (ref "IC10") (pin "4") (pinfunction "VIN-_4") (pintype "input"))
      (node (ref "IC8") (pin "4") (pinfunction "VIN_4") (pintype "bidirectional"))
      (node (ref "J5") (pin "5") (pinfunction "5_5") (pintype "bidirectional"))
      (node (ref "J6") (pin "5") (pinfunction "5_5") (pintype "bidirectional"))
      (node (ref "J7") (pin "1") (pinfunction "1_1") (pintype "passive"))
      (node (ref "J8") (pin "1") (pinfunction "1_1") (pintype "passive"))
      (node (ref "JP1") (pin "3") (pinfunction "3_3") (pintype "bidirectional"))
      (node (ref "Q6") (pin "2") (pinfunction "S_2") (pintype "passive"))
      (node (ref "Q6") (pin "5") (pinfunction "S_5") (pintype "passive"))
      (node (ref "Q8") (pin "2") (pinfunction "S_2") (pintype "passive"))
      (node (ref "Q8") (pin "5") (pinfunction "S_5") (pintype "passive"))
      (node (ref "R124") (pin "1") (pinfunction "1_1") (pintype "passive"))
      (node (ref "R125") (pin "1") (pinfunction "1_1") (pintype "passive"))
      (node (ref "R22") (pin "1") (pinfunction "1_1") (pintype "passive"))
      (node (ref "R33") (pin "2") (pinfunction "2_2") (pintype "passive"))
      (node (ref "R39") (pin "1") (pinfunction "1_1") (pintype "passive"))
      (node (ref "R50") (pin "1") (pinfunction "1_1") (pintype "passive"))
      (node (ref "R55") (pin "1") (pinfunction "1_1") (pintype "passive"))
      (node (ref "R56") (pin "1") (pinfunction "1_1") (pintype "passive"))
      (node (ref "R61") (pin "1") (pinfunction "1_1") (pintype "passive"))
    )
    (net (code "217") (name "unconnected-(IC2-D8-Pad30)") (class "Default")
      (node (ref "IC2") (pin "30") (pinfunction "D8_30") (pintype "tri_state"))
    )
    (net (code "218") (name "unconnected-(IC2-D9-Pad32)") (class "Default")
      (node (ref "IC2") (pin "32") (pinfunction "D9_32") (pintype "tri_state"))
    )
    (net (code "219") (name "unconnected-(IC2-D10-Pad34)") (class "Default")
      (node (ref "IC2") (pin "34") (pinfunction "D10_34") (pintype "tri_state"))
    )
    (net (code "220") (name "unconnected-(IC2-D11-Pad36)") (class "Default")
      (node (ref "IC2") (pin "36") (pinfunction "D11_36") (pintype "tri_state"))
    )
    (net (code "221") (name "unconnected-(IC2-D12-Pad39)") (class "Default")
      (node (ref "IC2") (pin "39") (pinfunction "D12_39") (pintype "tri_state"))
    )
    (net (code "222") (name "unconnected-(IC2-D13-Pad41)") (class "Default")
      (node (ref "IC2") (pin "41") (pinfunction "D13_41") (pintype "tri_state"))
    )
    (net (code "223") (name "unconnected-(IC2-D14-Pad43)") (class "Default")
      (node (ref "IC2") (pin "43") (pinfunction "D14_43") (pintype "tri_state"))
    )
    (net (code "224") (name "unconnected-(IC2-NC-Pad10)") (class "Default")
      (node (ref "IC2") (pin "10") (pinfunction "NC_10") (pintype "no_connect"))
    )
    (net (code "225") (name "unconnected-(IC2-NC1-Pad13)") (class "Default")
      (node (ref "IC2") (pin "13") (pinfunction "NC1_13") (pintype "no_connect"))
    )
    (net (code "226") (name "unconnected-(IC8-PG-Pad9)") (class "Default")
      (node (ref "IC8") (pin "9") (pinfunction "PG_9") (pintype "bidirectional"))
    )
    (net (code "227") (name "unconnected-(J1-Pad1)") (class "Default")
      (node (ref "J1") (pin "1") (pinfunction "1_1") (pintype "passive"))
    )
    (net (code "228") (name "unconnected-(J1-Pad23)") (class "Default")
      (node (ref "J1") (pin "23") (pinfunction "23_23") (pintype "passive"))
    )
    (net (code "229") (name "unconnected-(J1-Pad24)") (class "Default")
      (node (ref "J1") (pin "24") (pinfunction "24_24") (pintype "passive"))
    )
    (net (code "230") (name "unconnected-(J2-Pad1)") (class "Default")
      (node (ref "J2") (pin "1") (pinfunction "1_1") (pintype "passive"))
    )
    (net (code "231") (name "unconnected-(J2-Pad23)") (class "Default")
      (node (ref "J2") (pin "23") (pinfunction "23_23") (pintype "passive"))
    )
    (net (code "232") (name "unconnected-(J2-Pad24)") (class "Default")
      (node (ref "J2") (pin "24") (pinfunction "24_24") (pintype "passive"))
    )
    (net (code "233") (name "unconnected-(J5-Pad6)") (class "Default")
      (node (ref "J5") (pin "6") (pinfunction "6_6") (pintype "bidirectional"))
    )
    (net (code "234") (name "unconnected-(J6-Pad6)") (class "Default")
      (node (ref "J6") (pin "6") (pinfunction "6_6") (pintype "bidirectional"))
    )
    (net (code "235") (name "unconnected-(J11-DAT1-Pad8)") (class "Default")
      (node (ref "J11") (pin "8") (pinfunction "DAT1_8") (pintype "passive"))
    )
    (net (code "236") (name "unconnected-(J11-DAT2-Pad1)") (class "Default")
      (node (ref "J11") (pin "1") (pinfunction "DAT2_1") (pintype "passive"))
    )
    (net (code "237") (name "unconnected-(J14-Pad8)") (class "Default")
      (node (ref "J14") (pin "8") (pinfunction "8_8") (pintype "passive"))
    )
    (net (code "238") (name "unconnected-(J15-Pad2)") (class "Default")
      (node (ref "J15") (pin "2") (pinfunction "2_2") (pintype "passive"))
    )
    (net (code "239") (name "unconnected-(J15-Pad4)") (class "Default")
      (node (ref "J15") (pin "4") (pinfunction "4_4") (pintype "passive"))
    )
    (net (code "240") (name "unconnected-(J15-Pad5)") (class "Default")
      (node (ref "J15") (pin "5") (pinfunction "5_5") (pintype "passive"))
    )
    (net (code "241") (name "unconnected-(J15-Pad6)") (class "Default")
      (node (ref "J15") (pin "6") (pinfunction "6_6") (pintype "passive"))
    )
    (net (code "242") (name "unconnected-(J15-Pad7)") (class "Default")
      (node (ref "J15") (pin "7") (pinfunction "7_7") (pintype "passive"))
    )
    (net (code "243") (name "unconnected-(J15-Pad10)") (class "Default")
      (node (ref "J15") (pin "10") (pinfunction "10_10") (pintype "passive"))
    )
    (net (code "244") (name "unconnected-(J15-Pad15)") (class "Default")
      (node (ref "J15") (pin "15") (pinfunction "15_15") (pintype "passive"))
    )
    (net (code "245") (name "unconnected-(J15-Pad16)") (class "Default")
      (node (ref "J15") (pin "16") (pinfunction "16_16") (pintype "passive"))
    )
    (net (code "246") (name "unconnected-(Q3B-D-Pad3)") (class "Default")
      (node (ref "Q3") (pin "3") (pinfunction "D_3") (pintype "passive"))
    )
    (net (code "247") (name "unconnected-(Q3B-G-Pad5)") (class "Default")
      (node (ref "Q3") (pin "5") (pinfunction "G_5") (pintype "passive"))
    )
    (net (code "248") (name "unconnected-(Q3B-S-Pad4)") (class "Default")
      (node (ref "Q3") (pin "4") (pinfunction "S_4") (pintype "passive"))
    )
    (net (code "249") (name "unconnected-(Q14B-D-Pad3)") (class "Default")
      (node (ref "Q14") (pin "3") (pinfunction "D_3") (pintype "passive"))
    )
    (net (code "250") (name "unconnected-(Q14B-G-Pad5)") (class "Default")
      (node (ref "Q14") (pin "5") (pinfunction "G_5") (pintype "passive"))
    )
    (net (code "251") (name "unconnected-(Q14B-S-Pad4)") (class "Default")
      (node (ref "Q14") (pin "4") (pinfunction "S_4") (pintype "passive"))
    )
  )
)
